# AllInOne.net
KiCad netlist of a schematic drawn in EAGLE
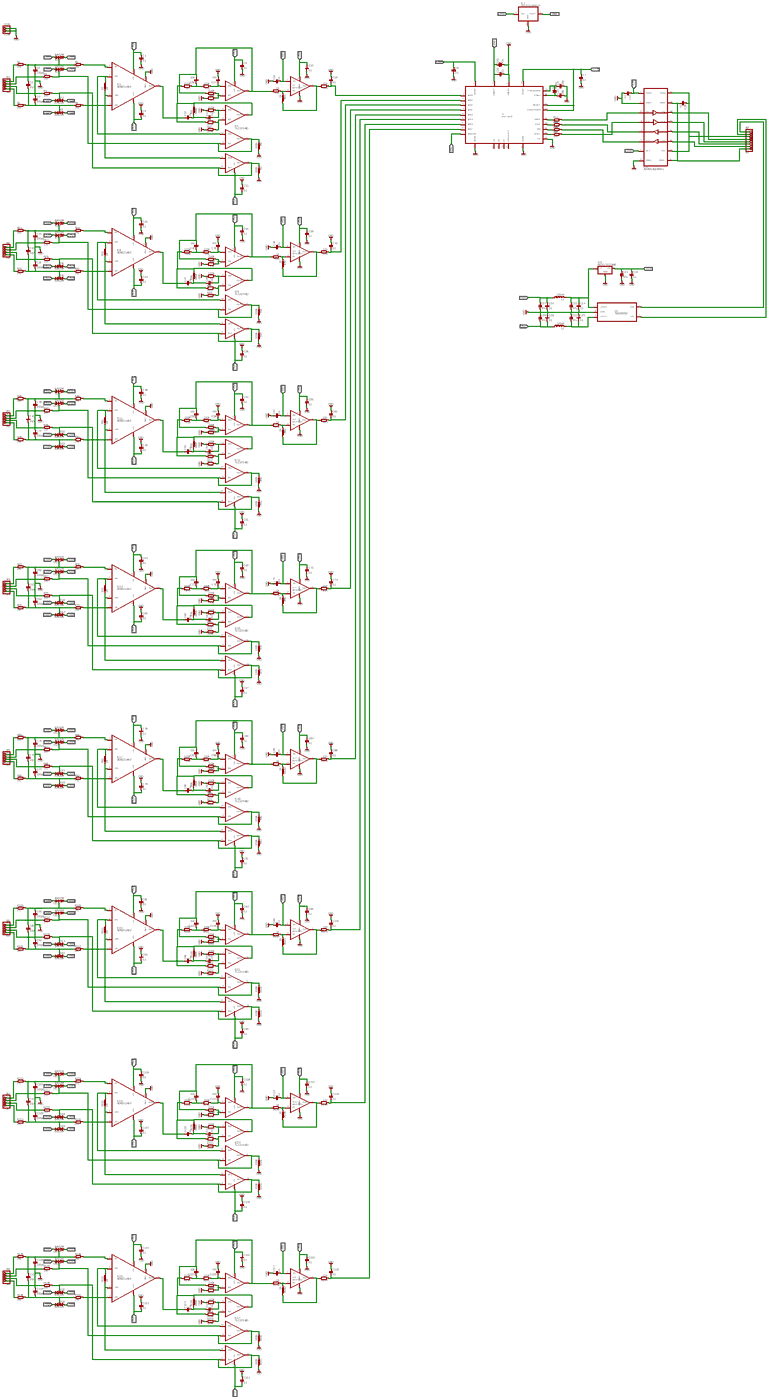
[diagram p0: schematic, sheet 1, overview]
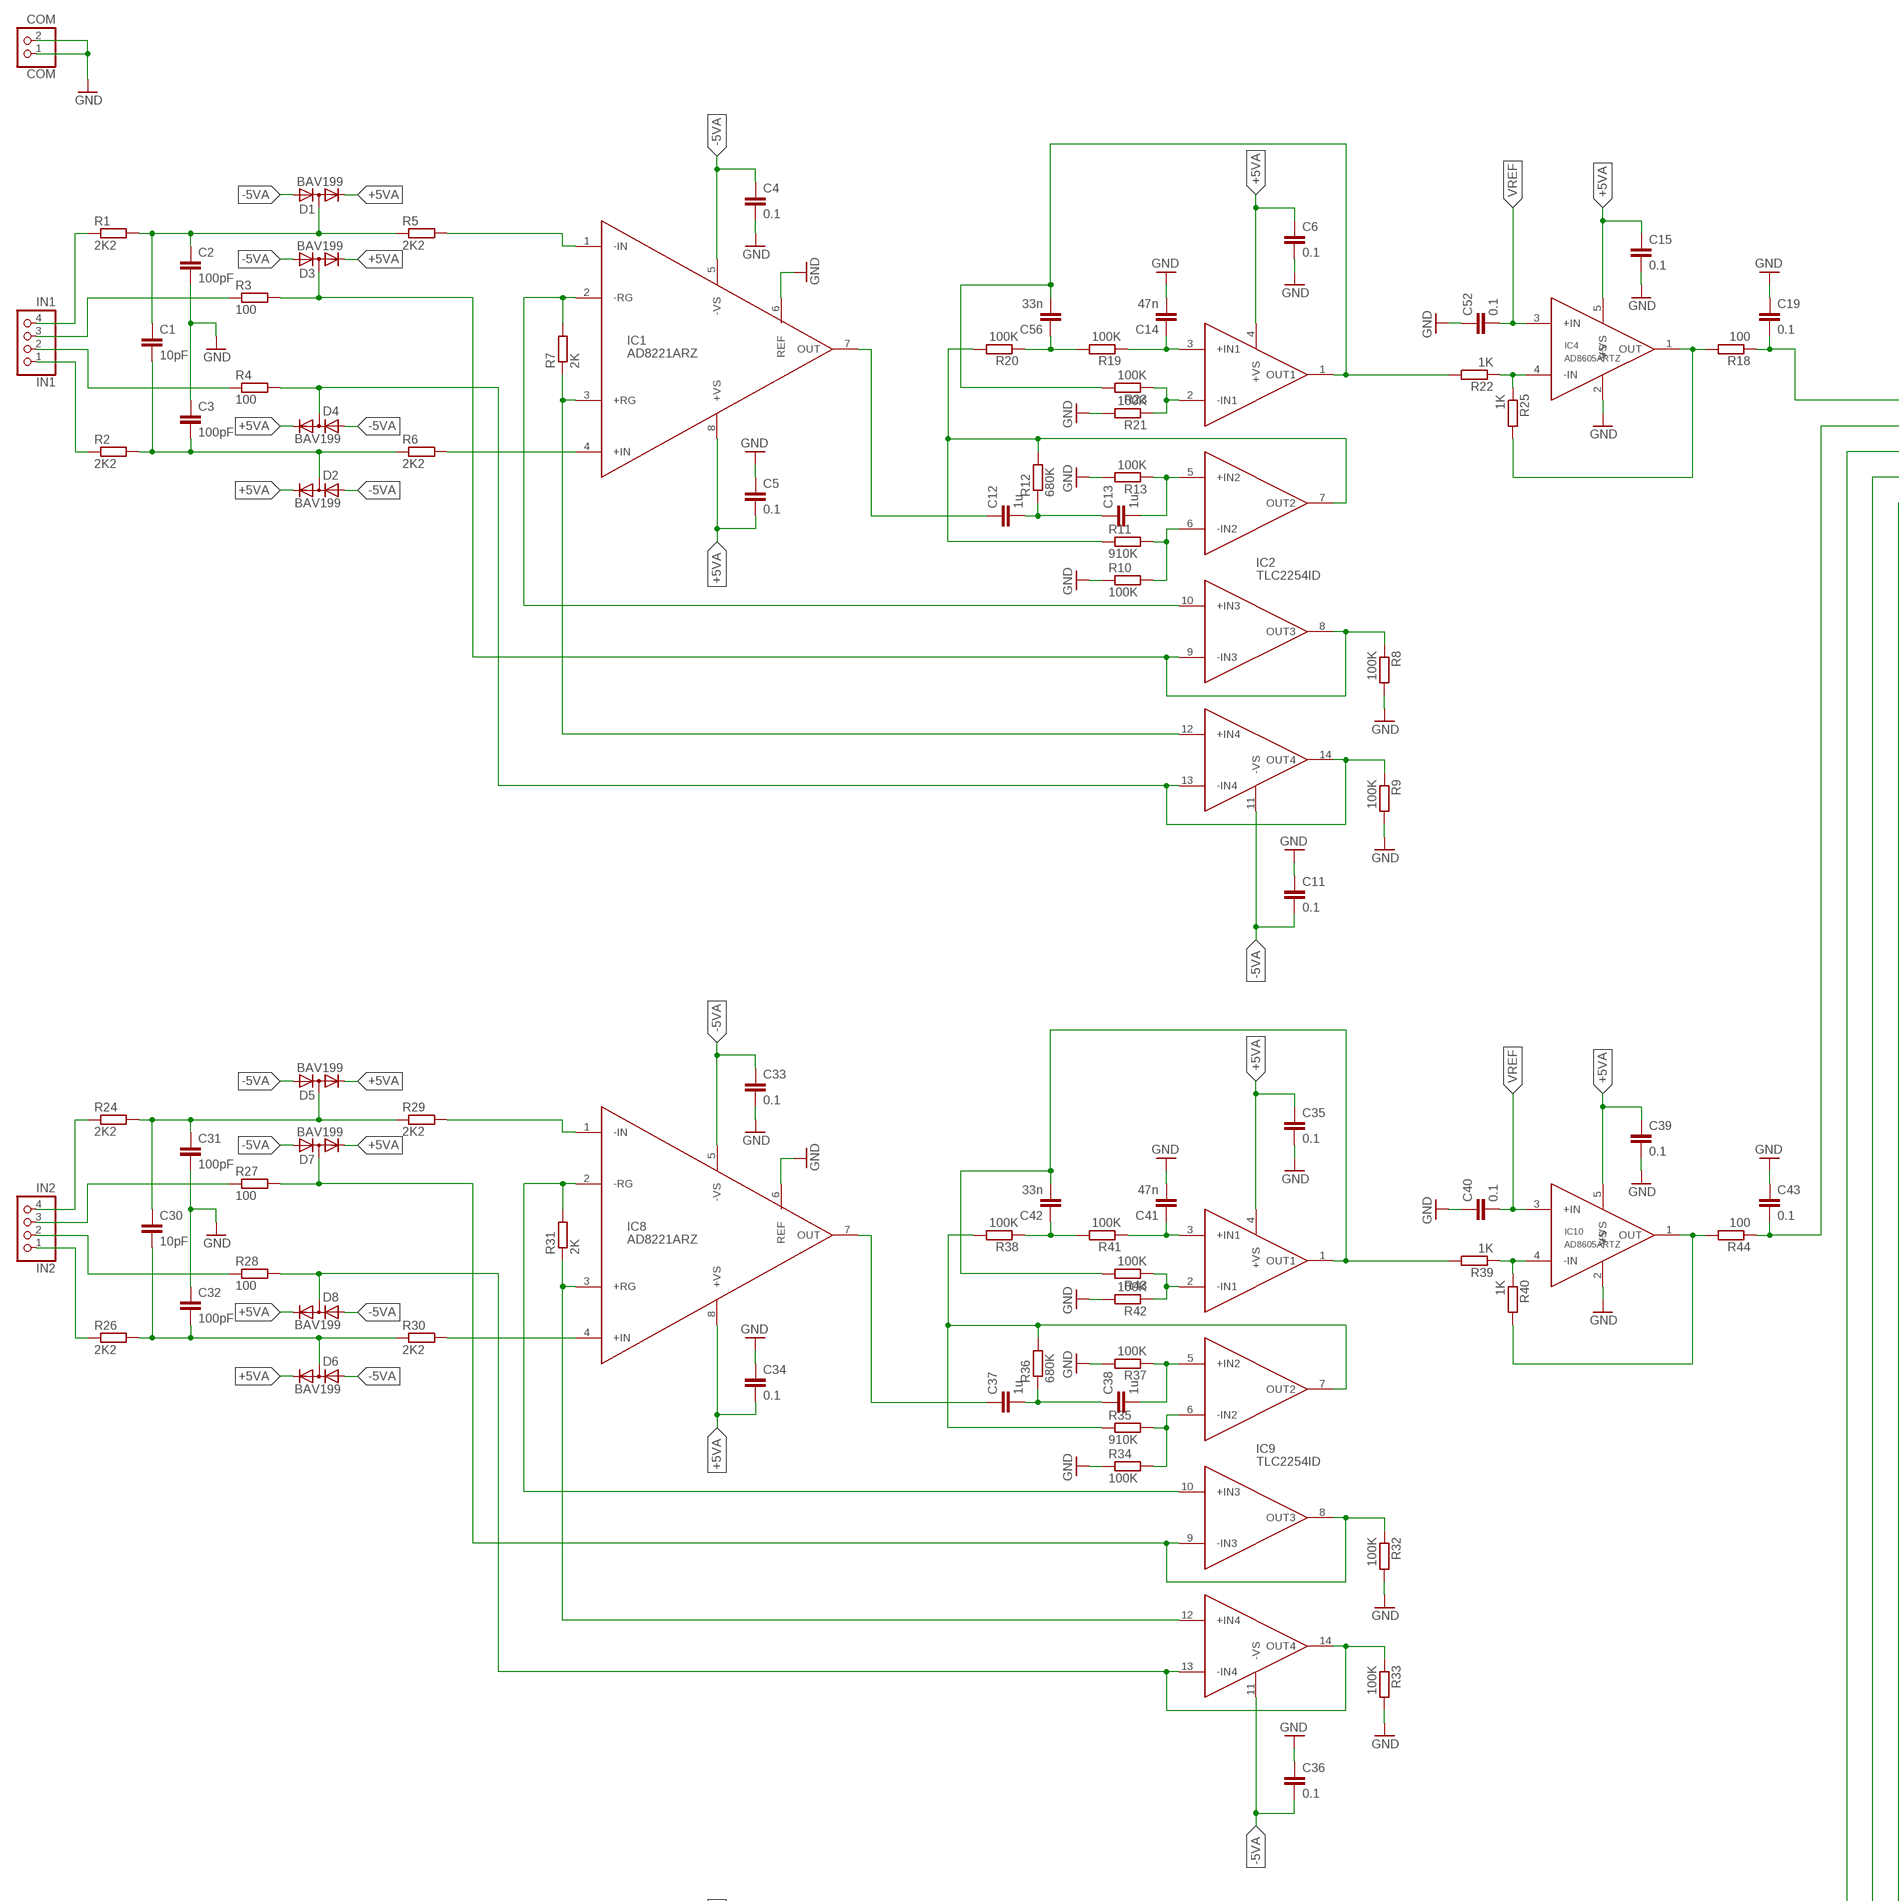
[diagram p1: schematic, sheet 1, part 1 of 5]
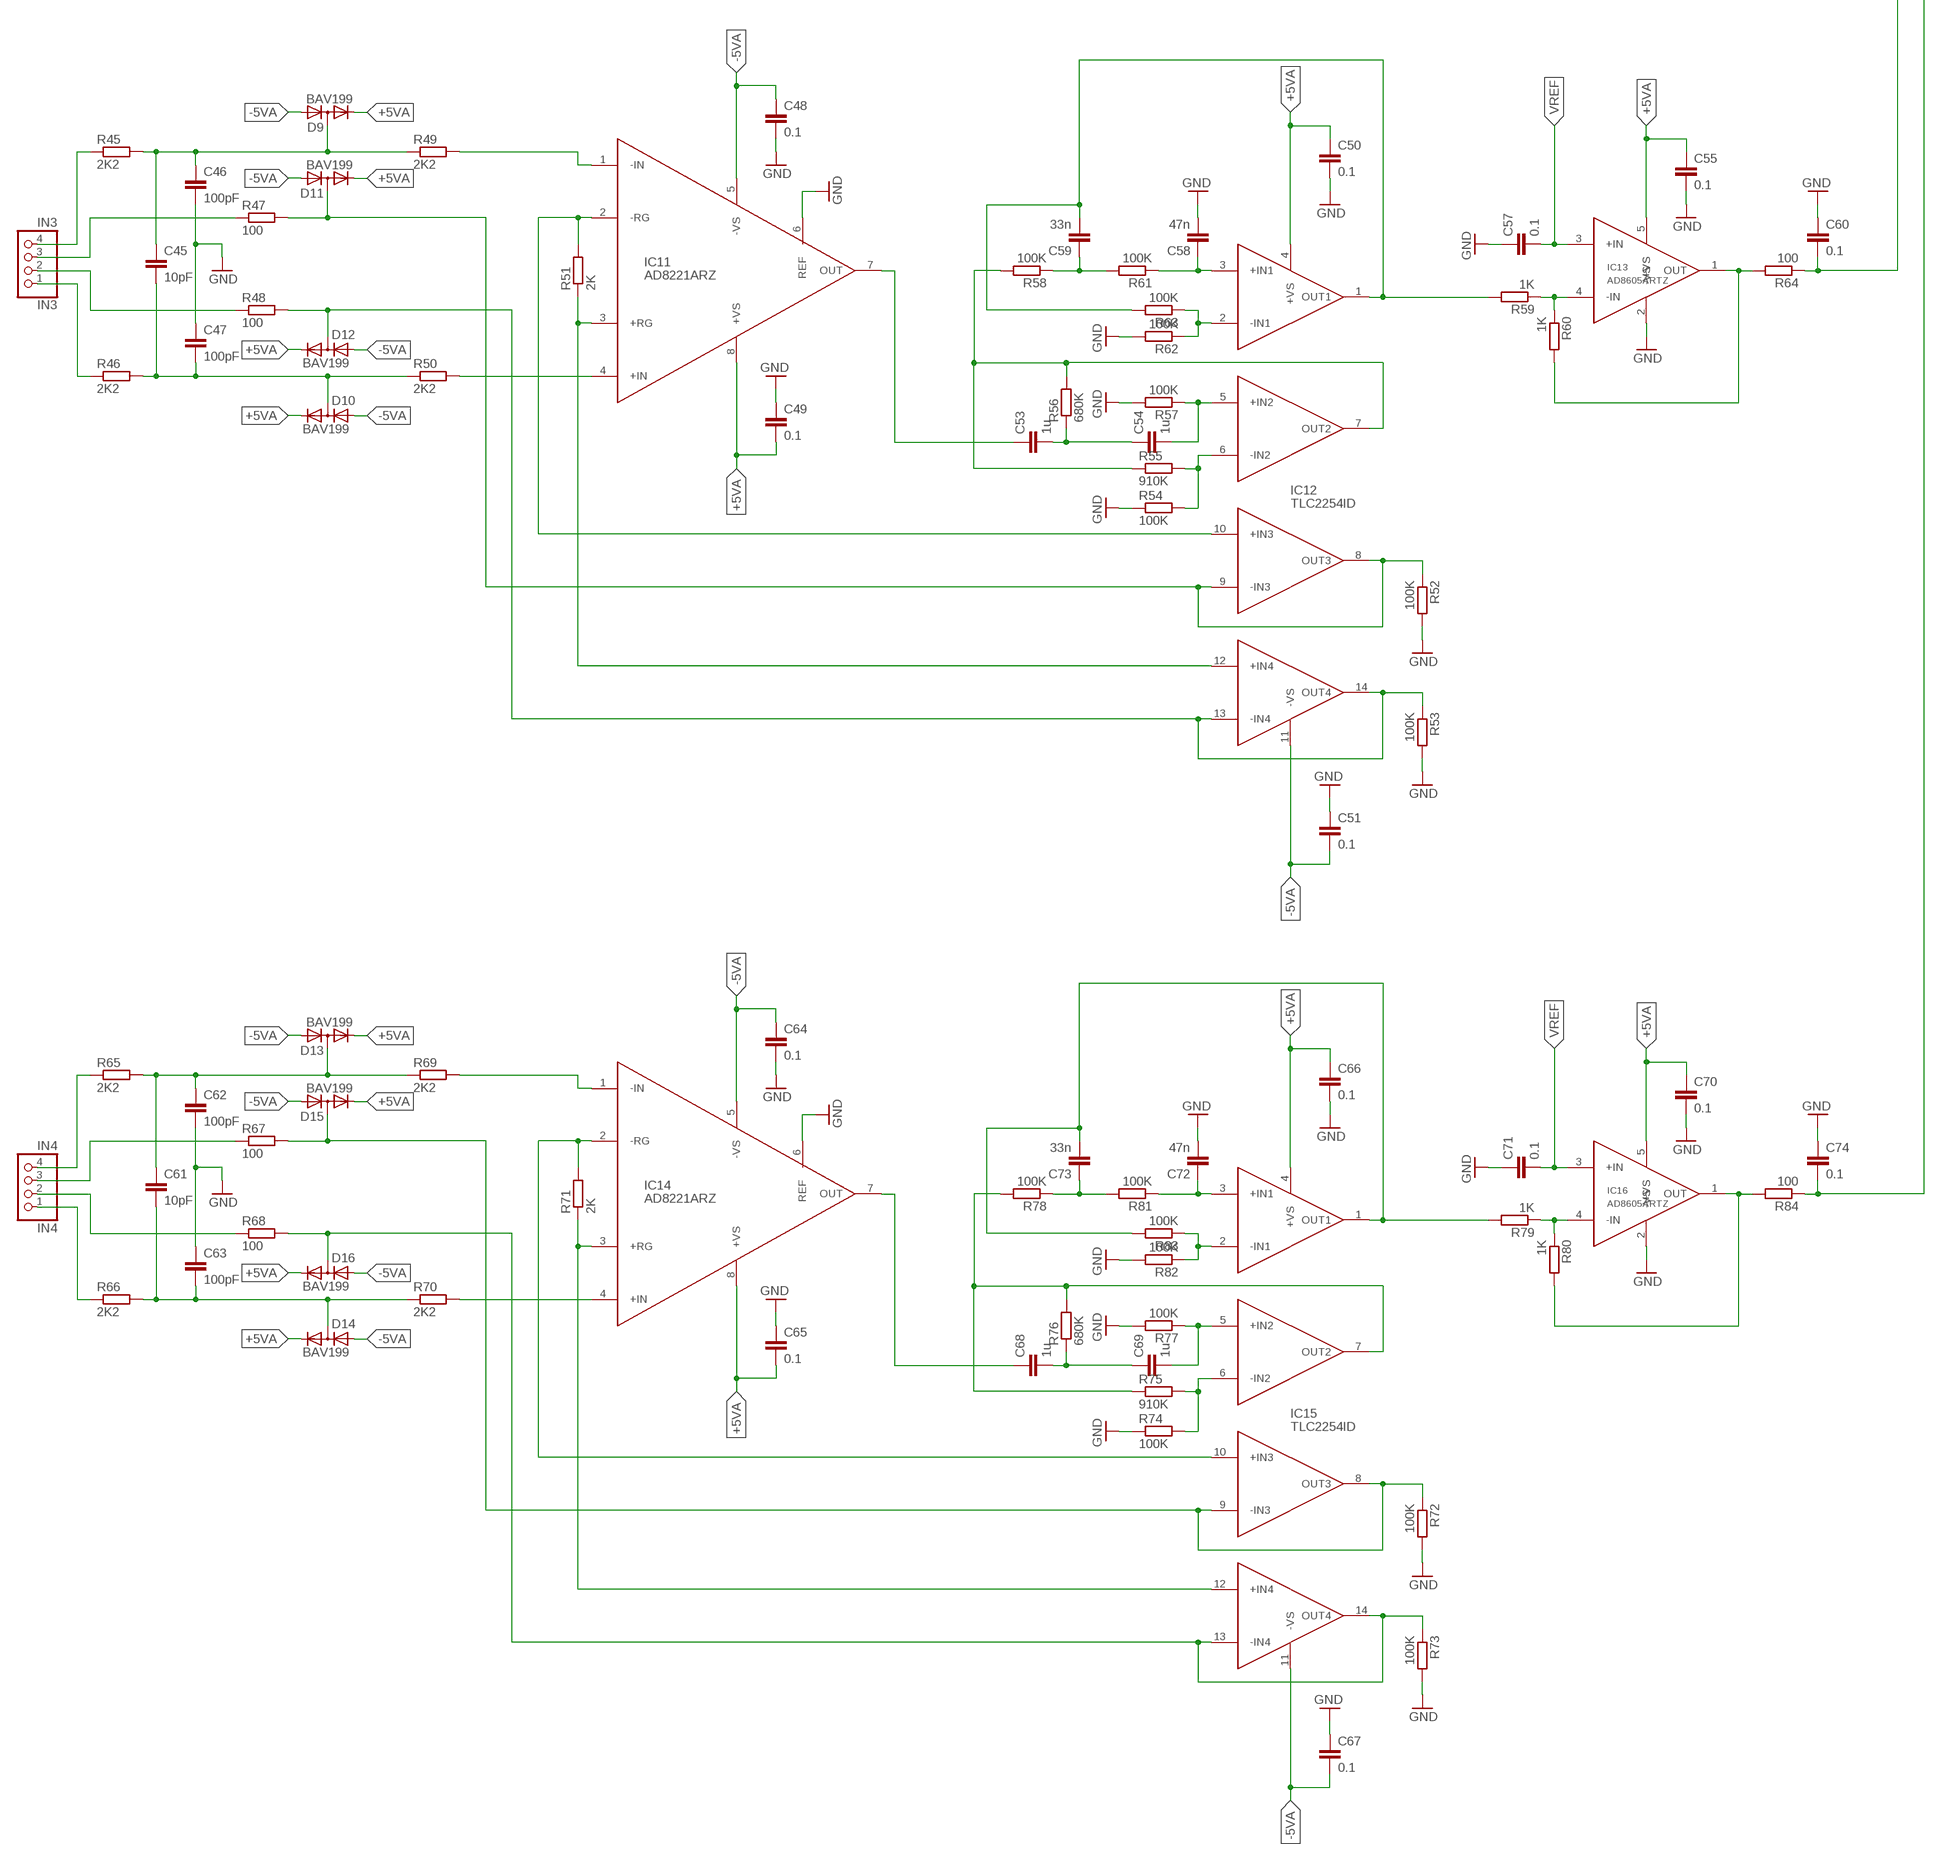
[diagram p2: schematic, sheet 1, part 2 of 5]
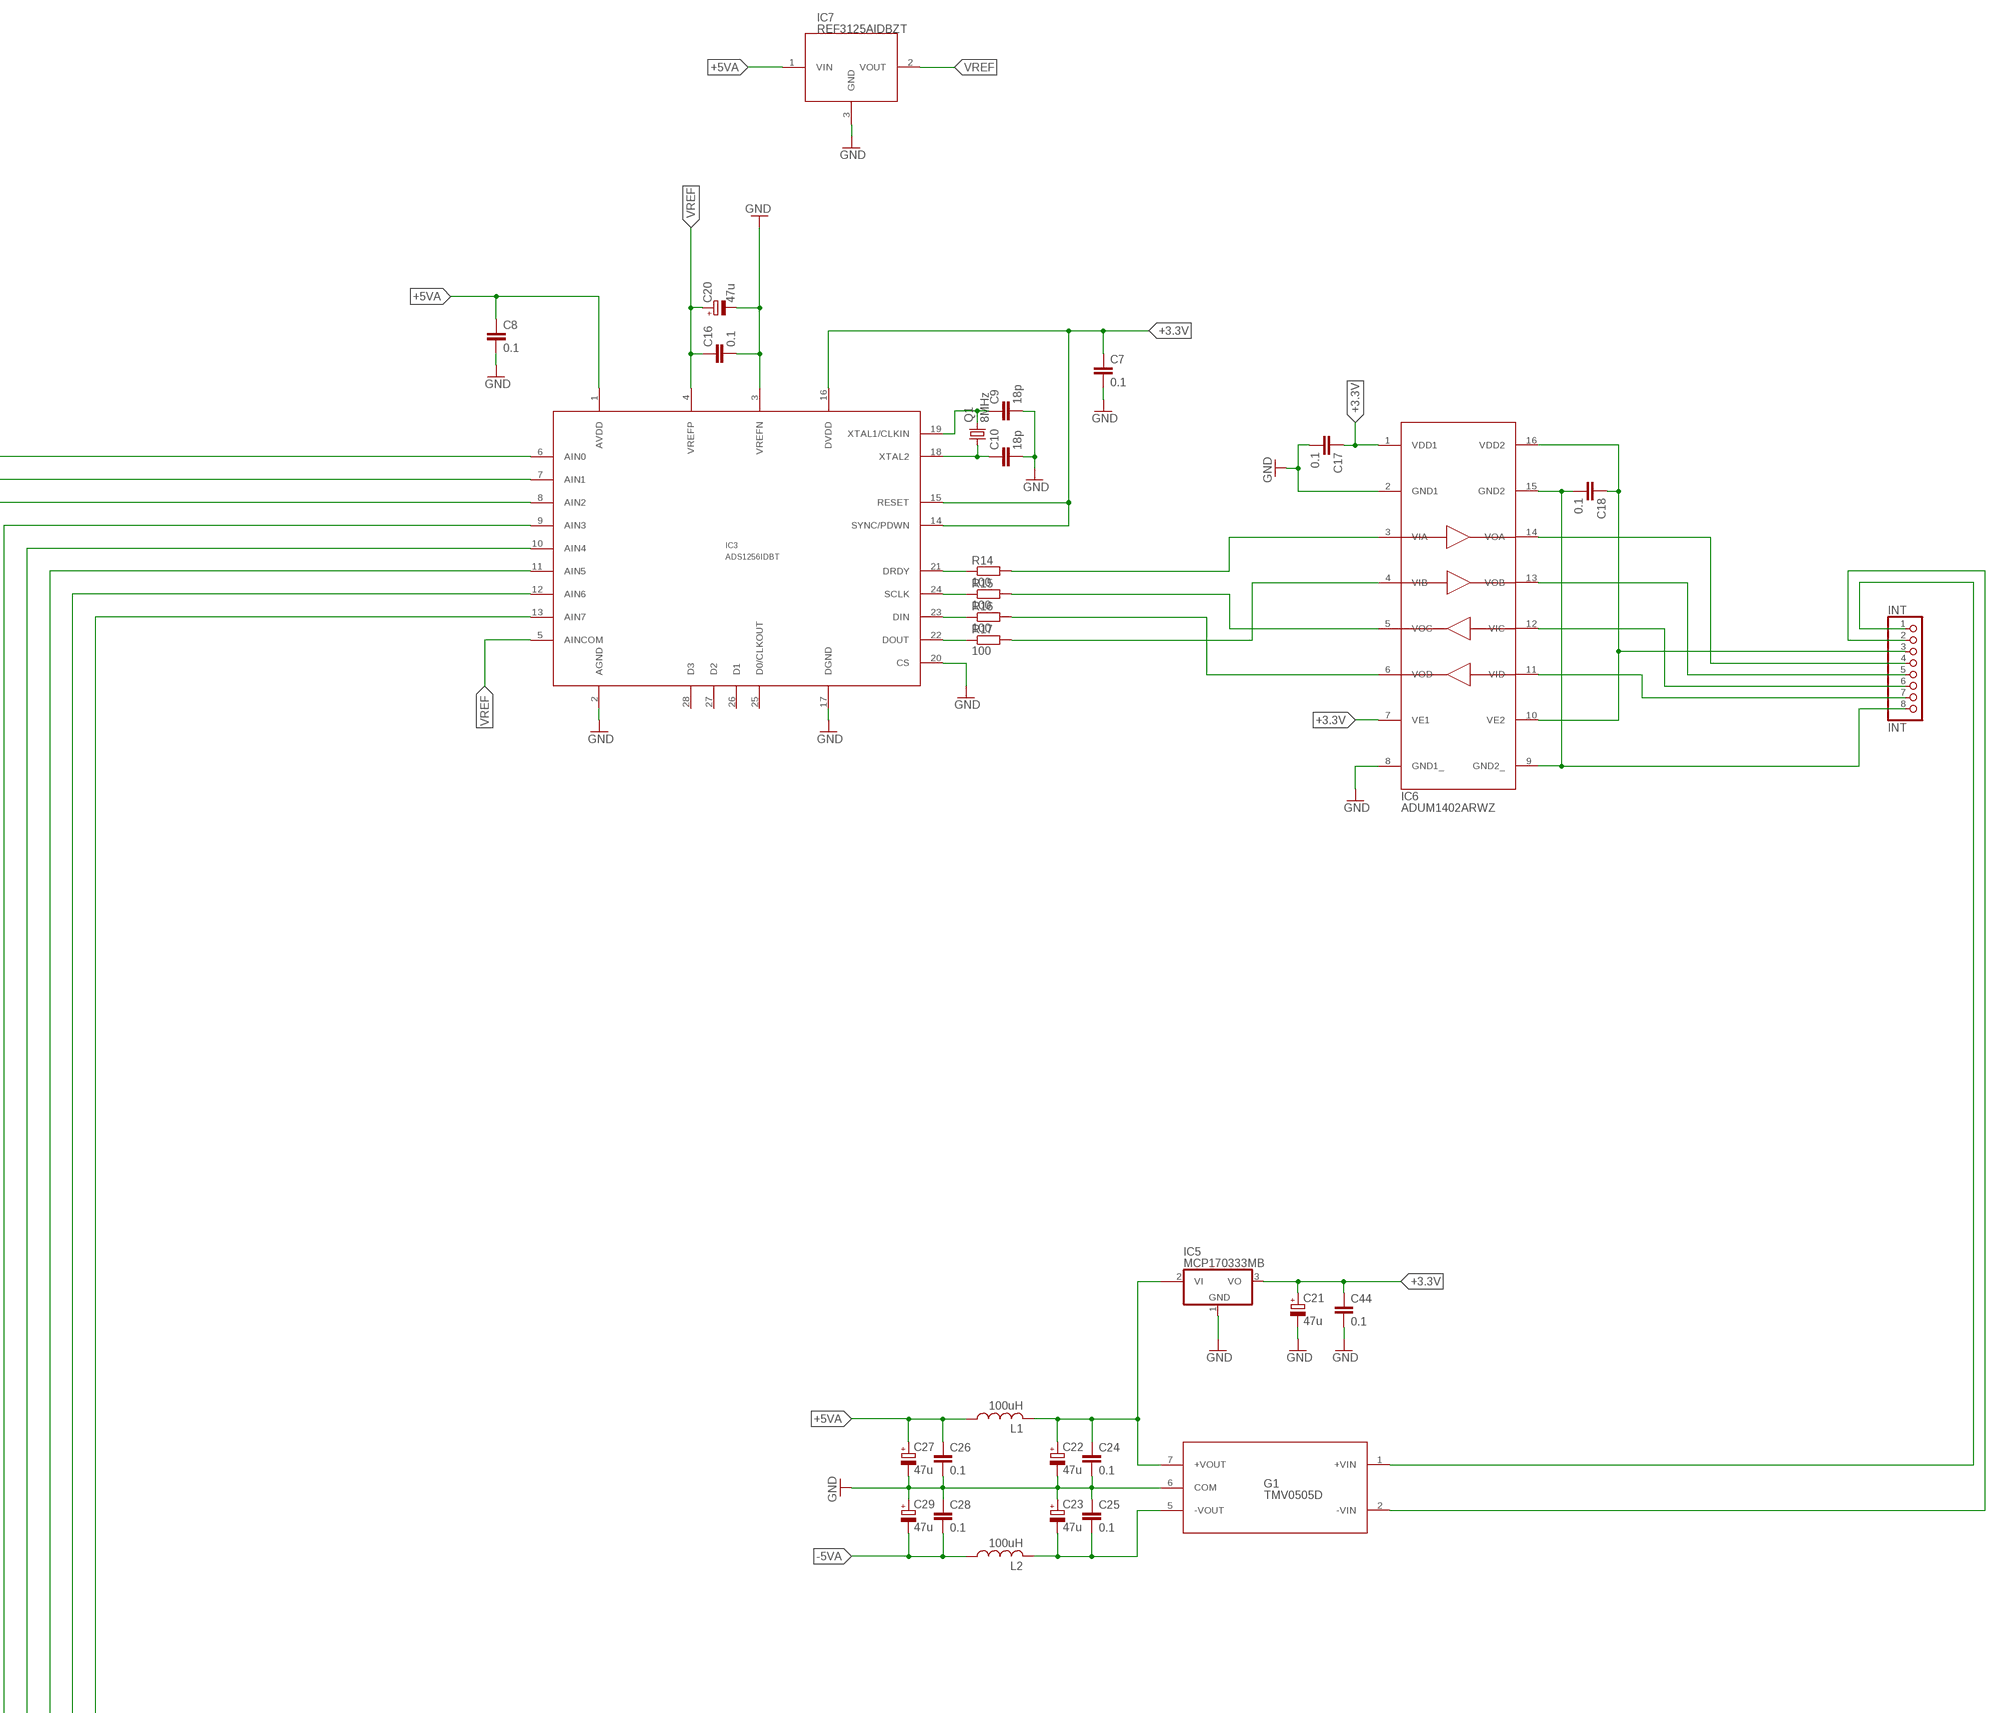
[diagram p3: schematic, sheet 1, part 3 of 5]
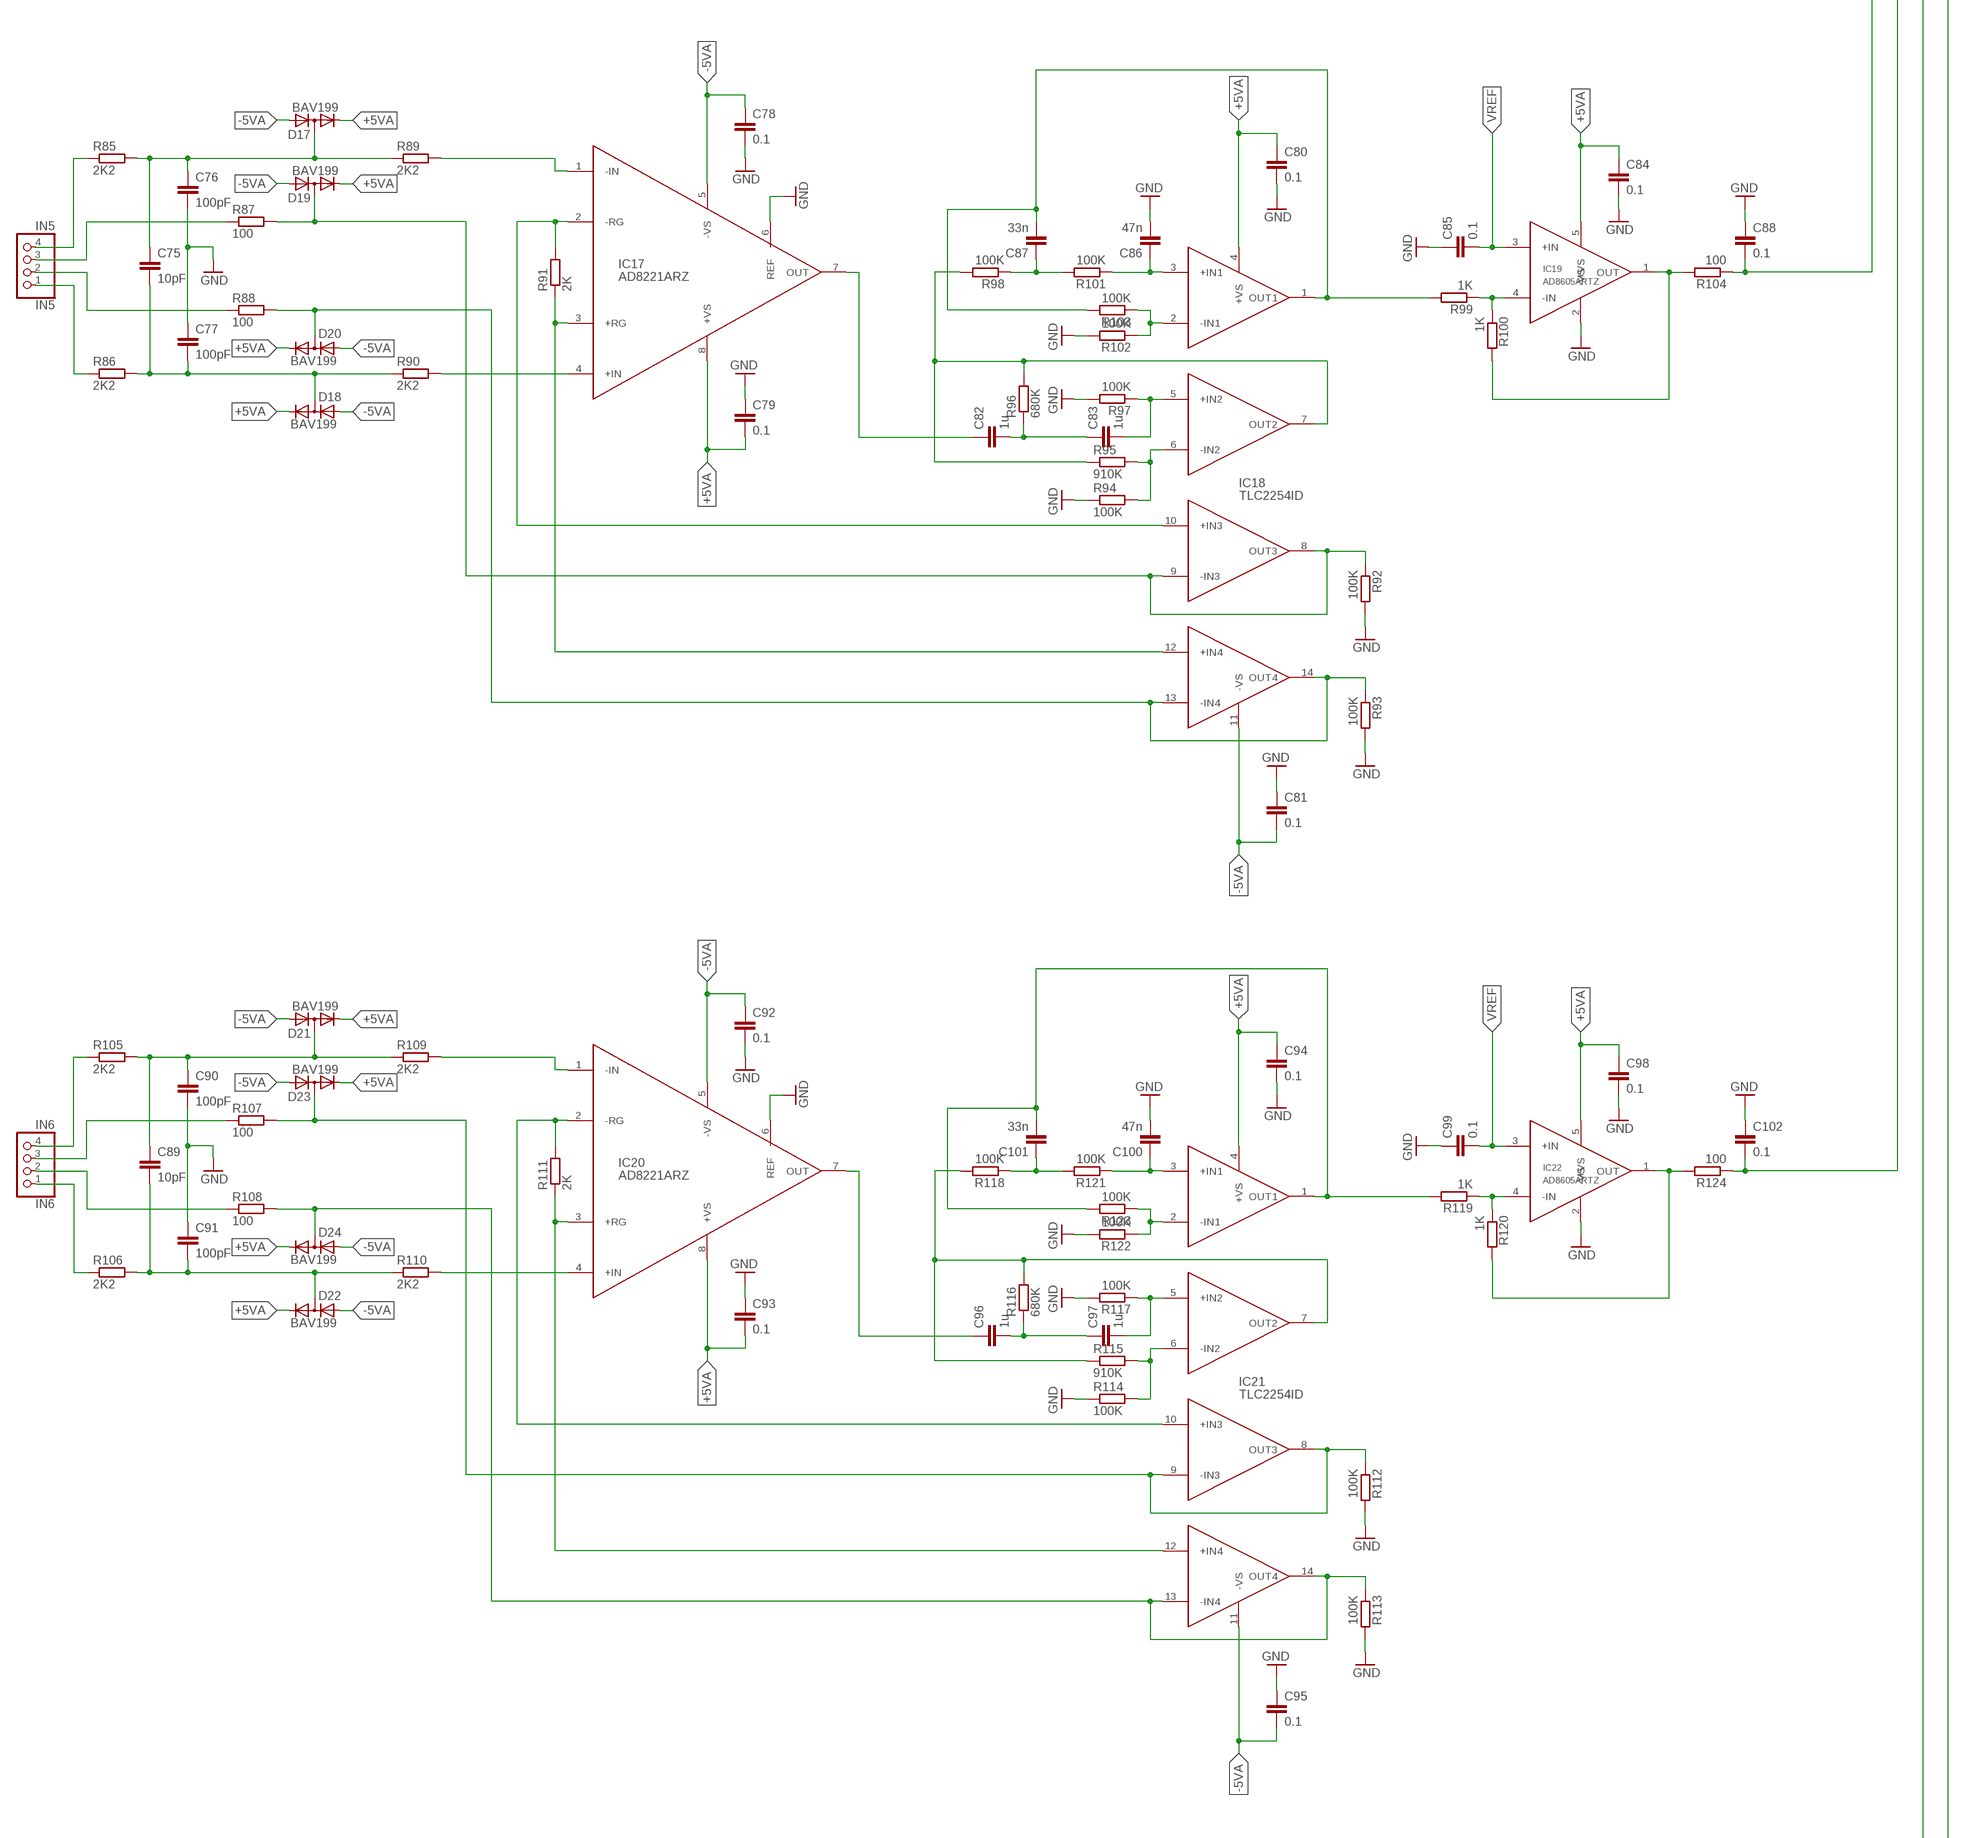
[diagram p4: schematic, sheet 1, part 4 of 5]
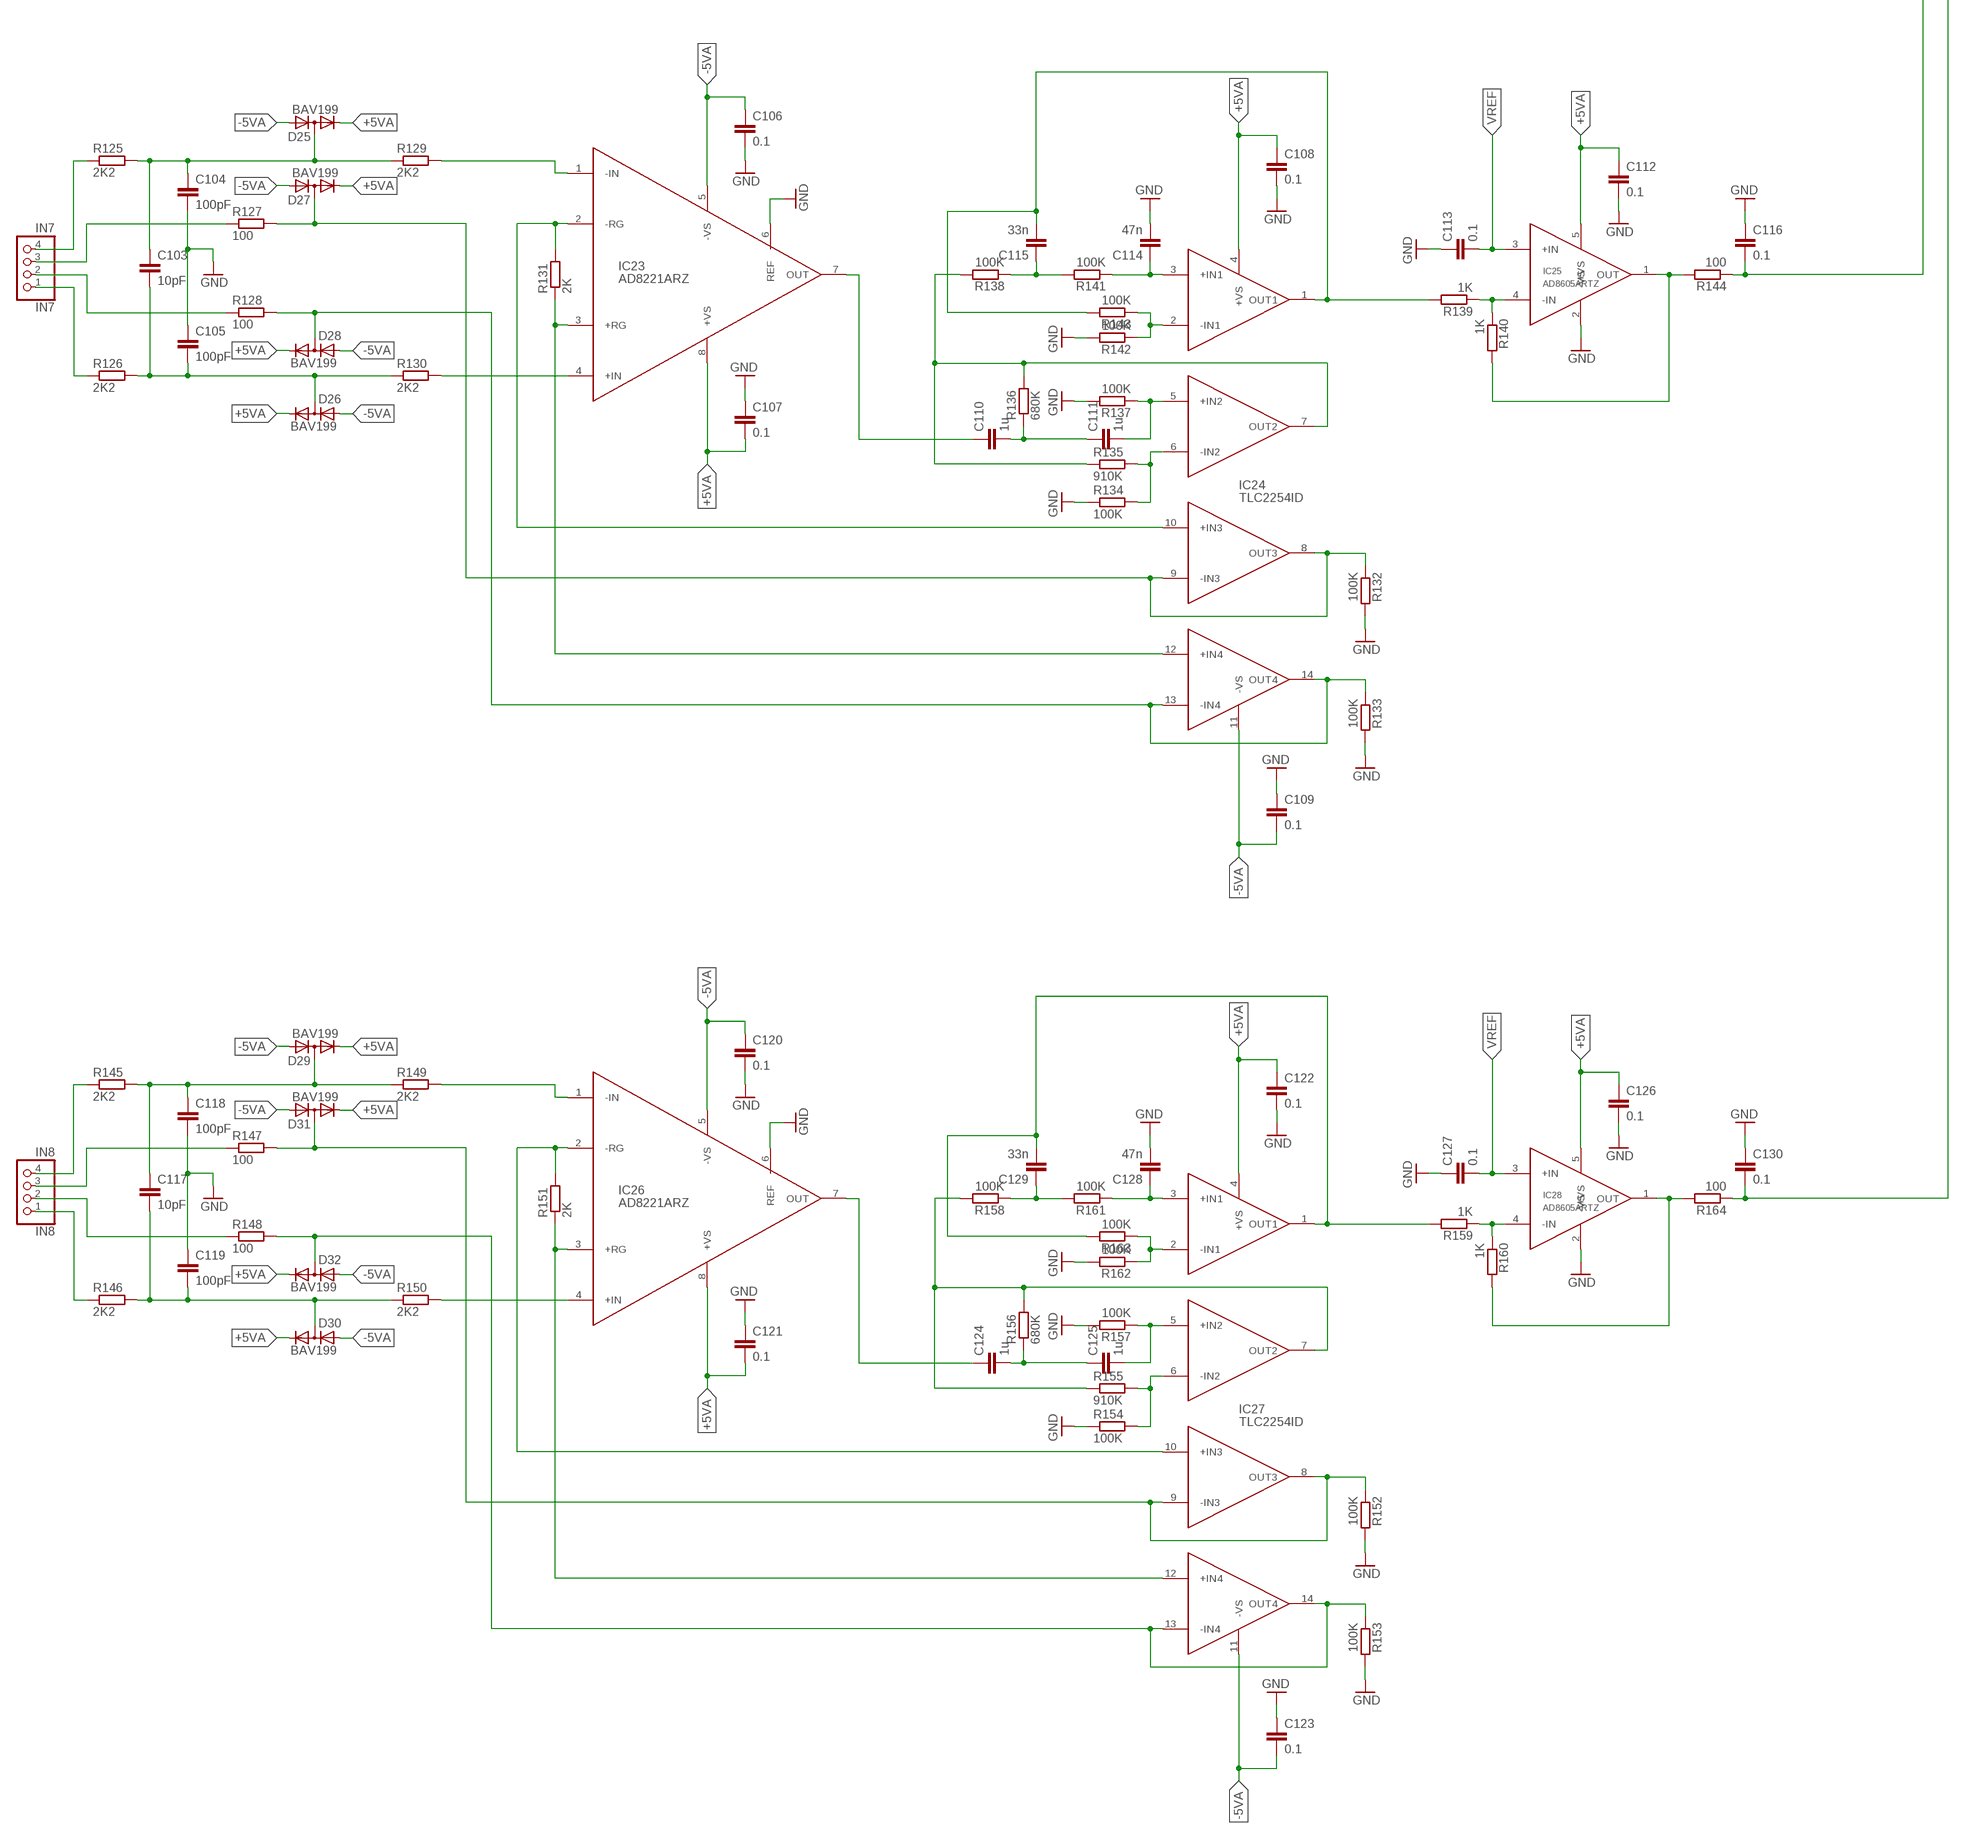
[diagram p5: schematic, sheet 1, part 5 of 5]

(export (version "E")
  (design (tool "Eeschema 10.0.6"))
  (components
    (comp (ref "C1")
      (value "10pF")
      (footprint "eagle-import:C0805")
      (libsource (lib "eagle-import") (part "C-EUC0805"))
    )
    (comp (ref "C2")
      (value "100pF")
      (footprint "eagle-import:C0805")
      (libsource (lib "eagle-import") (part "C-EUC0805"))
    )
    (comp (ref "C3")
      (value "100pF")
      (footprint "eagle-import:C0805")
      (libsource (lib "eagle-import") (part "C-EUC0805"))
    )
    (comp (ref "C4")
      (value "0.1")
      (footprint "eagle-import:C0805")
      (libsource (lib "eagle-import") (part "C-EUC0805"))
    )
    (comp (ref "C5")
      (value "0.1")
      (footprint "eagle-import:C0805")
      (libsource (lib "eagle-import") (part "C-EUC0805"))
    )
    (comp (ref "C6")
      (value "0.1")
      (footprint "eagle-import:C0805")
      (libsource (lib "eagle-import") (part "C-EUC0805"))
    )
    (comp (ref "C7")
      (value "0.1")
      (footprint "eagle-import:C0805")
      (libsource (lib "eagle-import") (part "C-EUC0805"))
    )
    (comp (ref "C8")
      (value "0.1")
      (footprint "eagle-import:C0805")
      (libsource (lib "eagle-import") (part "C-EUC0805"))
    )
    (comp (ref "C9")
      (value "18p")
      (footprint "eagle-import:C0805")
      (libsource (lib "eagle-import") (part "C-EUC0805"))
    )
    (comp (ref "C10")
      (value "18p")
      (footprint "eagle-import:C0805")
      (libsource (lib "eagle-import") (part "C-EUC0805"))
    )
    (comp (ref "C11")
      (value "0.1")
      (footprint "eagle-import:C0805")
      (libsource (lib "eagle-import") (part "C-EUC0805"))
    )
    (comp (ref "C12")
      (value "1u")
      (footprint "eagle-import:C0805")
      (libsource (lib "eagle-import") (part "C-EUC0805"))
    )
    (comp (ref "C13")
      (value "1u")
      (footprint "eagle-import:C0805")
      (libsource (lib "eagle-import") (part "C-EUC0805"))
    )
    (comp (ref "C14")
      (value "47n")
      (footprint "eagle-import:C0805")
      (libsource (lib "eagle-import") (part "C-EUC0805"))
    )
    (comp (ref "C15")
      (value "0.1")
      (footprint "eagle-import:C0805")
      (libsource (lib "eagle-import") (part "C-EUC0805"))
    )
    (comp (ref "C16")
      (value "0.1")
      (footprint "eagle-import:C0805")
      (libsource (lib "eagle-import") (part "C-EUC0805"))
    )
    (comp (ref "C17")
      (value "0.1")
      (footprint "eagle-import:C0805")
      (libsource (lib "eagle-import") (part "C-EUC0805"))
    )
    (comp (ref "C18")
      (value "0.1")
      (footprint "eagle-import:C0805")
      (libsource (lib "eagle-import") (part "C-EUC0805"))
    )
    (comp (ref "C19")
      (value "0.1")
      (footprint "eagle-import:C0805")
      (libsource (lib "eagle-import") (part "C-EUC0805"))
    )
    (comp (ref "C20")
      (value "47u")
      (footprint "eagle-import:E2-4")
      (libsource (lib "eagle-import") (part "CPOL-EUE2-4"))
    )
    (comp (ref "C21")
      (value "47u")
      (footprint "eagle-import:E2-4")
      (libsource (lib "eagle-import") (part "CPOL-EUE2-4"))
    )
    (comp (ref "C22")
      (value "47u")
      (footprint "eagle-import:E2-4")
      (libsource (lib "eagle-import") (part "CPOL-EUE2-4"))
    )
    (comp (ref "C23")
      (value "47u")
      (footprint "eagle-import:E2-4")
      (libsource (lib "eagle-import") (part "CPOL-EUE2-4"))
    )
    (comp (ref "C24")
      (value "0.1")
      (footprint "eagle-import:C0805")
      (libsource (lib "eagle-import") (part "C-EUC0805"))
    )
    (comp (ref "C25")
      (value "0.1")
      (footprint "eagle-import:C0805")
      (libsource (lib "eagle-import") (part "C-EUC0805"))
    )
    (comp (ref "C26")
      (value "0.1")
      (footprint "eagle-import:C0805")
      (libsource (lib "eagle-import") (part "C-EUC0805"))
    )
    (comp (ref "C27")
      (value "47u")
      (footprint "eagle-import:E2-4")
      (libsource (lib "eagle-import") (part "CPOL-EUE2-4"))
    )
    (comp (ref "C28")
      (value "0.1")
      (footprint "eagle-import:C0805")
      (libsource (lib "eagle-import") (part "C-EUC0805"))
    )
    (comp (ref "C29")
      (value "47u")
      (footprint "eagle-import:E2-4")
      (libsource (lib "eagle-import") (part "CPOL-EUE2-4"))
    )
    (comp (ref "C30")
      (value "10pF")
      (footprint "eagle-import:C0805")
      (libsource (lib "eagle-import") (part "C-EUC0805"))
    )
    (comp (ref "C31")
      (value "100pF")
      (footprint "eagle-import:C0805")
      (libsource (lib "eagle-import") (part "C-EUC0805"))
    )
    (comp (ref "C32")
      (value "100pF")
      (footprint "eagle-import:C0805")
      (libsource (lib "eagle-import") (part "C-EUC0805"))
    )
    (comp (ref "C33")
      (value "0.1")
      (footprint "eagle-import:C0805")
      (libsource (lib "eagle-import") (part "C-EUC0805"))
    )
    (comp (ref "C34")
      (value "0.1")
      (footprint "eagle-import:C0805")
      (libsource (lib "eagle-import") (part "C-EUC0805"))
    )
    (comp (ref "C35")
      (value "0.1")
      (footprint "eagle-import:C0805")
      (libsource (lib "eagle-import") (part "C-EUC0805"))
    )
    (comp (ref "C36")
      (value "0.1")
      (footprint "eagle-import:C0805")
      (libsource (lib "eagle-import") (part "C-EUC0805"))
    )
    (comp (ref "C37")
      (value "1u")
      (footprint "eagle-import:C0805")
      (libsource (lib "eagle-import") (part "C-EUC0805"))
    )
    (comp (ref "C38")
      (value "1u")
      (footprint "eagle-import:C0805")
      (libsource (lib "eagle-import") (part "C-EUC0805"))
    )
    (comp (ref "C39")
      (value "0.1")
      (footprint "eagle-import:C0805")
      (libsource (lib "eagle-import") (part "C-EUC0805"))
    )
    (comp (ref "C40")
      (value "0.1")
      (footprint "eagle-import:C0805")
      (libsource (lib "eagle-import") (part "C-EUC0805"))
    )
    (comp (ref "C41")
      (value "47n")
      (footprint "eagle-import:C0805")
      (libsource (lib "eagle-import") (part "C-EUC0805"))
    )
    (comp (ref "C42")
      (value "33n")
      (footprint "eagle-import:C0805")
      (libsource (lib "eagle-import") (part "C-EUC0805"))
    )
    (comp (ref "C43")
      (value "0.1")
      (footprint "eagle-import:C0805")
      (libsource (lib "eagle-import") (part "C-EUC0805"))
    )
    (comp (ref "C44")
      (value "0.1")
      (footprint "eagle-import:C0805")
      (libsource (lib "eagle-import") (part "C-EUC0805"))
    )
    (comp (ref "C45")
      (value "10pF")
      (footprint "eagle-import:C0805")
      (libsource (lib "eagle-import") (part "C-EUC0805"))
    )
    (comp (ref "C46")
      (value "100pF")
      (footprint "eagle-import:C0805")
      (libsource (lib "eagle-import") (part "C-EUC0805"))
    )
    (comp (ref "C47")
      (value "100pF")
      (footprint "eagle-import:C0805")
      (libsource (lib "eagle-import") (part "C-EUC0805"))
    )
    (comp (ref "C48")
      (value "0.1")
      (footprint "eagle-import:C0805")
      (libsource (lib "eagle-import") (part "C-EUC0805"))
    )
    (comp (ref "C49")
      (value "0.1")
      (footprint "eagle-import:C0805")
      (libsource (lib "eagle-import") (part "C-EUC0805"))
    )
    (comp (ref "C50")
      (value "0.1")
      (footprint "eagle-import:C0805")
      (libsource (lib "eagle-import") (part "C-EUC0805"))
    )
    (comp (ref "C51")
      (value "0.1")
      (footprint "eagle-import:C0805")
      (libsource (lib "eagle-import") (part "C-EUC0805"))
    )
    (comp (ref "C52")
      (value "0.1")
      (footprint "eagle-import:C0805")
      (libsource (lib "eagle-import") (part "C-EUC0805"))
    )
    (comp (ref "C53")
      (value "1u")
      (footprint "eagle-import:C0805")
      (libsource (lib "eagle-import") (part "C-EUC0805"))
    )
    (comp (ref "C54")
      (value "1u")
      (footprint "eagle-import:C0805")
      (libsource (lib "eagle-import") (part "C-EUC0805"))
    )
    (comp (ref "C55")
      (value "0.1")
      (footprint "eagle-import:C0805")
      (libsource (lib "eagle-import") (part "C-EUC0805"))
    )
    (comp (ref "C56")
      (value "33n")
      (footprint "eagle-import:C0805")
      (libsource (lib "eagle-import") (part "C-EUC0805"))
    )
    (comp (ref "C57")
      (value "0.1")
      (footprint "eagle-import:C0805")
      (libsource (lib "eagle-import") (part "C-EUC0805"))
    )
    (comp (ref "C58")
      (value "47n")
      (footprint "eagle-import:C0805")
      (libsource (lib "eagle-import") (part "C-EUC0805"))
    )
    (comp (ref "C59")
      (value "33n")
      (footprint "eagle-import:C0805")
      (libsource (lib "eagle-import") (part "C-EUC0805"))
    )
    (comp (ref "C60")
      (value "0.1")
      (footprint "eagle-import:C0805")
      (libsource (lib "eagle-import") (part "C-EUC0805"))
    )
    (comp (ref "C61")
      (value "10pF")
      (footprint "eagle-import:C0805")
      (libsource (lib "eagle-import") (part "C-EUC0805"))
    )
    (comp (ref "C62")
      (value "100pF")
      (footprint "eagle-import:C0805")
      (libsource (lib "eagle-import") (part "C-EUC0805"))
    )
    (comp (ref "C63")
      (value "100pF")
      (footprint "eagle-import:C0805")
      (libsource (lib "eagle-import") (part "C-EUC0805"))
    )
    (comp (ref "C64")
      (value "0.1")
      (footprint "eagle-import:C0805")
      (libsource (lib "eagle-import") (part "C-EUC0805"))
    )
    (comp (ref "C65")
      (value "0.1")
      (footprint "eagle-import:C0805")
      (libsource (lib "eagle-import") (part "C-EUC0805"))
    )
    (comp (ref "C66")
      (value "0.1")
      (footprint "eagle-import:C0805")
      (libsource (lib "eagle-import") (part "C-EUC0805"))
    )
    (comp (ref "C67")
      (value "0.1")
      (footprint "eagle-import:C0805")
      (libsource (lib "eagle-import") (part "C-EUC0805"))
    )
    (comp (ref "C68")
      (value "1u")
      (footprint "eagle-import:C0805")
      (libsource (lib "eagle-import") (part "C-EUC0805"))
    )
    (comp (ref "C69")
      (value "1u")
      (footprint "eagle-import:C0805")
      (libsource (lib "eagle-import") (part "C-EUC0805"))
    )
    (comp (ref "C70")
      (value "0.1")
      (footprint "eagle-import:C0805")
      (libsource (lib "eagle-import") (part "C-EUC0805"))
    )
    (comp (ref "C71")
      (value "0.1")
      (footprint "eagle-import:C0805")
      (libsource (lib "eagle-import") (part "C-EUC0805"))
    )
    (comp (ref "C72")
      (value "47n")
      (footprint "eagle-import:C0805")
      (libsource (lib "eagle-import") (part "C-EUC0805"))
    )
    (comp (ref "C73")
      (value "33n")
      (footprint "eagle-import:C0805")
      (libsource (lib "eagle-import") (part "C-EUC0805"))
    )
    (comp (ref "C74")
      (value "0.1")
      (footprint "eagle-import:C0805")
      (libsource (lib "eagle-import") (part "C-EUC0805"))
    )
    (comp (ref "C75")
      (value "10pF")
      (footprint "eagle-import:C0805")
      (libsource (lib "eagle-import") (part "C-EUC0805"))
    )
    (comp (ref "C76")
      (value "100pF")
      (footprint "eagle-import:C0805")
      (libsource (lib "eagle-import") (part "C-EUC0805"))
    )
    (comp (ref "C77")
      (value "100pF")
      (footprint "eagle-import:C0805")
      (libsource (lib "eagle-import") (part "C-EUC0805"))
    )
    (comp (ref "C78")
      (value "0.1")
      (footprint "eagle-import:C0805")
      (libsource (lib "eagle-import") (part "C-EUC0805"))
    )
    (comp (ref "C79")
      (value "0.1")
      (footprint "eagle-import:C0805")
      (libsource (lib "eagle-import") (part "C-EUC0805"))
    )
    (comp (ref "C80")
      (value "0.1")
      (footprint "eagle-import:C0805")
      (libsource (lib "eagle-import") (part "C-EUC0805"))
    )
    (comp (ref "C81")
      (value "0.1")
      (footprint "eagle-import:C0805")
      (libsource (lib "eagle-import") (part "C-EUC0805"))
    )
    (comp (ref "C82")
      (value "1u")
      (footprint "eagle-import:C0805")
      (libsource (lib "eagle-import") (part "C-EUC0805"))
    )
    (comp (ref "C83")
      (value "1u")
      (footprint "eagle-import:C0805")
      (libsource (lib "eagle-import") (part "C-EUC0805"))
    )
    (comp (ref "C84")
      (value "0.1")
      (footprint "eagle-import:C0805")
      (libsource (lib "eagle-import") (part "C-EUC0805"))
    )
    (comp (ref "C85")
      (value "0.1")
      (footprint "eagle-import:C0805")
      (libsource (lib "eagle-import") (part "C-EUC0805"))
    )
    (comp (ref "C86")
      (value "47n")
      (footprint "eagle-import:C0805")
      (libsource (lib "eagle-import") (part "C-EUC0805"))
    )
    (comp (ref "C87")
      (value "33n")
      (footprint "eagle-import:C0805")
      (libsource (lib "eagle-import") (part "C-EUC0805"))
    )
    (comp (ref "C88")
      (value "0.1")
      (footprint "eagle-import:C0805")
      (libsource (lib "eagle-import") (part "C-EUC0805"))
    )
    (comp (ref "C89")
      (value "10pF")
      (footprint "eagle-import:C0805")
      (libsource (lib "eagle-import") (part "C-EUC0805"))
    )
    (comp (ref "C90")
      (value "100pF")
      (footprint "eagle-import:C0805")
      (libsource (lib "eagle-import") (part "C-EUC0805"))
    )
    (comp (ref "C91")
      (value "100pF")
      (footprint "eagle-import:C0805")
      (libsource (lib "eagle-import") (part "C-EUC0805"))
    )
    (comp (ref "C92")
      (value "0.1")
      (footprint "eagle-import:C0805")
      (libsource (lib "eagle-import") (part "C-EUC0805"))
    )
    (comp (ref "C93")
      (value "0.1")
      (footprint "eagle-import:C0805")
      (libsource (lib "eagle-import") (part "C-EUC0805"))
    )
    (comp (ref "C94")
      (value "0.1")
      (footprint "eagle-import:C0805")
      (libsource (lib "eagle-import") (part "C-EUC0805"))
    )
    (comp (ref "C95")
      (value "0.1")
      (footprint "eagle-import:C0805")
      (libsource (lib "eagle-import") (part "C-EUC0805"))
    )
    (comp (ref "C96")
      (value "1u")
      (footprint "eagle-import:C0805")
      (libsource (lib "eagle-import") (part "C-EUC0805"))
    )
    (comp (ref "C97")
      (value "1u")
      (footprint "eagle-import:C0805")
      (libsource (lib "eagle-import") (part "C-EUC0805"))
    )
    (comp (ref "C98")
      (value "0.1")
      (footprint "eagle-import:C0805")
      (libsource (lib "eagle-import") (part "C-EUC0805"))
    )
    (comp (ref "C99")
      (value "0.1")
      (footprint "eagle-import:C0805")
      (libsource (lib "eagle-import") (part "C-EUC0805"))
    )
    (comp (ref "C100")
      (value "47n")
      (footprint "eagle-import:C0805")
      (libsource (lib "eagle-import") (part "C-EUC0805"))
    )
    (comp (ref "C101")
      (value "33n")
      (footprint "eagle-import:C0805")
      (libsource (lib "eagle-import") (part "C-EUC0805"))
    )
    (comp (ref "C102")
      (value "0.1")
      (footprint "eagle-import:C0805")
      (libsource (lib "eagle-import") (part "C-EUC0805"))
    )
    (comp (ref "C103")
      (value "10pF")
      (footprint "eagle-import:C0805")
      (libsource (lib "eagle-import") (part "C-EUC0805"))
    )
    (comp (ref "C104")
      (value "100pF")
      (footprint "eagle-import:C0805")
      (libsource (lib "eagle-import") (part "C-EUC0805"))
    )
    (comp (ref "C105")
      (value "100pF")
      (footprint "eagle-import:C0805")
      (libsource (lib "eagle-import") (part "C-EUC0805"))
    )
    (comp (ref "C106")
      (value "0.1")
      (footprint "eagle-import:C0805")
      (libsource (lib "eagle-import") (part "C-EUC0805"))
    )
    (comp (ref "C107")
      (value "0.1")
      (footprint "eagle-import:C0805")
      (libsource (lib "eagle-import") (part "C-EUC0805"))
    )
    (comp (ref "C108")
      (value "0.1")
      (footprint "eagle-import:C0805")
      (libsource (lib "eagle-import") (part "C-EUC0805"))
    )
    (comp (ref "C109")
      (value "0.1")
      (footprint "eagle-import:C0805")
      (libsource (lib "eagle-import") (part "C-EUC0805"))
    )
    (comp (ref "C110")
      (value "1u")
      (footprint "eagle-import:C0805")
      (libsource (lib "eagle-import") (part "C-EUC0805"))
    )
    (comp (ref "C111")
      (value "1u")
      (footprint "eagle-import:C0805")
      (libsource (lib "eagle-import") (part "C-EUC0805"))
    )
    (comp (ref "C112")
      (value "0.1")
      (footprint "eagle-import:C0805")
      (libsource (lib "eagle-import") (part "C-EUC0805"))
    )
    (comp (ref "C113")
      (value "0.1")
      (footprint "eagle-import:C0805")
      (libsource (lib "eagle-import") (part "C-EUC0805"))
    )
    (comp (ref "C114")
      (value "47n")
      (footprint "eagle-import:C0805")
      (libsource (lib "eagle-import") (part "C-EUC0805"))
    )
    (comp (ref "C115")
      (value "33n")
      (footprint "eagle-import:C0805")
      (libsource (lib "eagle-import") (part "C-EUC0805"))
    )
    (comp (ref "C116")
      (value "0.1")
      (footprint "eagle-import:C0805")
      (libsource (lib "eagle-import") (part "C-EUC0805"))
    )
    (comp (ref "C117")
      (value "10pF")
      (footprint "eagle-import:C0805")
      (libsource (lib "eagle-import") (part "C-EUC0805"))
    )
    (comp (ref "C118")
      (value "100pF")
      (footprint "eagle-import:C0805")
      (libsource (lib "eagle-import") (part "C-EUC0805"))
    )
    (comp (ref "C119")
      (value "100pF")
      (footprint "eagle-import:C0805")
      (libsource (lib "eagle-import") (part "C-EUC0805"))
    )
    (comp (ref "C120")
      (value "0.1")
      (footprint "eagle-import:C0805")
      (libsource (lib "eagle-import") (part "C-EUC0805"))
    )
    (comp (ref "C121")
      (value "0.1")
      (footprint "eagle-import:C0805")
      (libsource (lib "eagle-import") (part "C-EUC0805"))
    )
    (comp (ref "C122")
      (value "0.1")
      (footprint "eagle-import:C0805")
      (libsource (lib "eagle-import") (part "C-EUC0805"))
    )
    (comp (ref "C123")
      (value "0.1")
      (footprint "eagle-import:C0805")
      (libsource (lib "eagle-import") (part "C-EUC0805"))
    )
    (comp (ref "C124")
      (value "1u")
      (footprint "eagle-import:C0805")
      (libsource (lib "eagle-import") (part "C-EUC0805"))
    )
    (comp (ref "C125")
      (value "1u")
      (footprint "eagle-import:C0805")
      (libsource (lib "eagle-import") (part "C-EUC0805"))
    )
    (comp (ref "C126")
      (value "0.1")
      (footprint "eagle-import:C0805")
      (libsource (lib "eagle-import") (part "C-EUC0805"))
    )
    (comp (ref "C127")
      (value "0.1")
      (footprint "eagle-import:C0805")
      (libsource (lib "eagle-import") (part "C-EUC0805"))
    )
    (comp (ref "C128")
      (value "47n")
      (footprint "eagle-import:C0805")
      (libsource (lib "eagle-import") (part "C-EUC0805"))
    )
    (comp (ref "C129")
      (value "33n")
      (footprint "eagle-import:C0805")
      (libsource (lib "eagle-import") (part "C-EUC0805"))
    )
    (comp (ref "C130")
      (value "0.1")
      (footprint "eagle-import:C0805")
      (libsource (lib "eagle-import") (part "C-EUC0805"))
    )
    (comp (ref "COM")
      (value "COM")
      (footprint "eagle-import:1X02")
      (libsource (lib "eagle-import") (part "PINHD-1X2"))
    )
    (comp (ref "D1")
      (value "BAV199")
      (footprint "eagle-import:SOT23")
      (libsource (lib "eagle-import") (part "BAV199"))
    )
    (comp (ref "D2")
      (value "BAV199")
      (footprint "eagle-import:SOT23")
      (libsource (lib "eagle-import") (part "BAV199"))
    )
    (comp (ref "D3")
      (value "BAV199")
      (footprint "eagle-import:SOT23")
      (libsource (lib "eagle-import") (part "BAV199"))
    )
    (comp (ref "D4")
      (value "BAV199")
      (footprint "eagle-import:SOT23")
      (libsource (lib "eagle-import") (part "BAV199"))
    )
    (comp (ref "D5")
      (value "BAV199")
      (footprint "eagle-import:SOT23")
      (libsource (lib "eagle-import") (part "BAV199"))
    )
    (comp (ref "D6")
      (value "BAV199")
      (footprint "eagle-import:SOT23")
      (libsource (lib "eagle-import") (part "BAV199"))
    )
    (comp (ref "D7")
      (value "BAV199")
      (footprint "eagle-import:SOT23")
      (libsource (lib "eagle-import") (part "BAV199"))
    )
    (comp (ref "D8")
      (value "BAV199")
      (footprint "eagle-import:SOT23")
      (libsource (lib "eagle-import") (part "BAV199"))
    )
    (comp (ref "D9")
      (value "BAV199")
      (footprint "eagle-import:SOT23")
      (libsource (lib "eagle-import") (part "BAV199"))
    )
    (comp (ref "D10")
      (value "BAV199")
      (footprint "eagle-import:SOT23")
      (libsource (lib "eagle-import") (part "BAV199"))
    )
    (comp (ref "D11")
      (value "BAV199")
      (footprint "eagle-import:SOT23")
      (libsource (lib "eagle-import") (part "BAV199"))
    )
    (comp (ref "D12")
      (value "BAV199")
      (footprint "eagle-import:SOT23")
      (libsource (lib "eagle-import") (part "BAV199"))
    )
    (comp (ref "D13")
      (value "BAV199")
      (footprint "eagle-import:SOT23")
      (libsource (lib "eagle-import") (part "BAV199"))
    )
    (comp (ref "D14")
      (value "BAV199")
      (footprint "eagle-import:SOT23")
      (libsource (lib "eagle-import") (part "BAV199"))
    )
    (comp (ref "D15")
      (value "BAV199")
      (footprint "eagle-import:SOT23")
      (libsource (lib "eagle-import") (part "BAV199"))
    )
    (comp (ref "D16")
      (value "BAV199")
      (footprint "eagle-import:SOT23")
      (libsource (lib "eagle-import") (part "BAV199"))
    )
    (comp (ref "D17")
      (value "BAV199")
      (footprint "eagle-import:SOT23")
      (libsource (lib "eagle-import") (part "BAV199"))
    )
    (comp (ref "D18")
      (value "BAV199")
      (footprint "eagle-import:SOT23")
      (libsource (lib "eagle-import") (part "BAV199"))
    )
    (comp (ref "D19")
      (value "BAV199")
      (footprint "eagle-import:SOT23")
      (libsource (lib "eagle-import") (part "BAV199"))
    )
    (comp (ref "D20")
      (value "BAV199")
      (footprint "eagle-import:SOT23")
      (libsource (lib "eagle-import") (part "BAV199"))
    )
    (comp (ref "D21")
      (value "BAV199")
      (footprint "eagle-import:SOT23")
      (libsource (lib "eagle-import") (part "BAV199"))
    )
    (comp (ref "D22")
      (value "BAV199")
      (footprint "eagle-import:SOT23")
      (libsource (lib "eagle-import") (part "BAV199"))
    )
    (comp (ref "D23")
      (value "BAV199")
      (footprint "eagle-import:SOT23")
      (libsource (lib "eagle-import") (part "BAV199"))
    )
    (comp (ref "D24")
      (value "BAV199")
      (footprint "eagle-import:SOT23")
      (libsource (lib "eagle-import") (part "BAV199"))
    )
    (comp (ref "D25")
      (value "BAV199")
      (footprint "eagle-import:SOT23")
      (libsource (lib "eagle-import") (part "BAV199"))
    )
    (comp (ref "D26")
      (value "BAV199")
      (footprint "eagle-import:SOT23")
      (libsource (lib "eagle-import") (part "BAV199"))
    )
    (comp (ref "D27")
      (value "BAV199")
      (footprint "eagle-import:SOT23")
      (libsource (lib "eagle-import") (part "BAV199"))
    )
    (comp (ref "D28")
      (value "BAV199")
      (footprint "eagle-import:SOT23")
      (libsource (lib "eagle-import") (part "BAV199"))
    )
    (comp (ref "D29")
      (value "BAV199")
      (footprint "eagle-import:SOT23")
      (libsource (lib "eagle-import") (part "BAV199"))
    )
    (comp (ref "D30")
      (value "BAV199")
      (footprint "eagle-import:SOT23")
      (libsource (lib "eagle-import") (part "BAV199"))
    )
    (comp (ref "D31")
      (value "BAV199")
      (footprint "eagle-import:SOT23")
      (libsource (lib "eagle-import") (part "BAV199"))
    )
    (comp (ref "D32")
      (value "BAV199")
      (footprint "eagle-import:SOT23")
      (libsource (lib "eagle-import") (part "BAV199"))
    )
    (comp (ref "G1")
      (value "TMV0505D")
      (footprint "eagle-import:TMV0505D")
      (libsource (lib "eagle-import") (part "TMV0505D"))
    )
    (comp (ref "IC1")
      (value "AD8221ARZ")
      (footprint "eagle-import:SO-08")
      (libsource (lib "eagle-import") (part "AD8221ARZ"))
    )
    (comp (ref "IC2")
      (value "TLC2254ID")
      (footprint "eagle-import:TLC2254ID")
      (libsource (lib "eagle-import") (part "TLC2254ID"))
    )
    (comp (ref "IC3")
      (value "ADS1256IDBT")
      (footprint "eagle-import:ADS1256IDBT")
      (libsource (lib "eagle-import") (part "ADS1256IDBT"))
    )
    (comp (ref "IC4")
      (value "AD8605ARTZ")
      (footprint "eagle-import:AD8605ARTZ")
      (libsource (lib "eagle-import") (part "AD8605ARTZ"))
    )
    (comp (ref "IC5")
      (value "MCP170333MB")
      (footprint "eagle-import:SOT89")
      (libsource (lib "eagle-import") (part "MCP1703MB33"))
    )
    (comp (ref "IC6")
      (value "ADUM1402ARWZ")
      (footprint "eagle-import:ADUM1402ARWZ")
      (libsource (lib "eagle-import") (part "ADUM1402ARWZ"))
    )
    (comp (ref "IC7")
      (value "REF3125AIDBZT")
      (footprint "eagle-import:REF3125AIDBZT")
      (libsource (lib "eagle-import") (part "REF3125AIDBZT"))
    )
    (comp (ref "IC8")
      (value "AD8221ARZ")
      (footprint "eagle-import:SO-08")
      (libsource (lib "eagle-import") (part "AD8221ARZ"))
    )
    (comp (ref "IC9")
      (value "TLC2254ID")
      (footprint "eagle-import:TLC2254ID")
      (libsource (lib "eagle-import") (part "TLC2254ID"))
    )
    (comp (ref "IC10")
      (value "AD8605ARTZ")
      (footprint "eagle-import:AD8605ARTZ")
      (libsource (lib "eagle-import") (part "AD8605ARTZ"))
    )
    (comp (ref "IC11")
      (value "AD8221ARZ")
      (footprint "eagle-import:SO-08")
      (libsource (lib "eagle-import") (part "AD8221ARZ"))
    )
    (comp (ref "IC12")
      (value "TLC2254ID")
      (footprint "eagle-import:TLC2254ID")
      (libsource (lib "eagle-import") (part "TLC2254ID"))
    )
    (comp (ref "IC13")
      (value "AD8605ARTZ")
      (footprint "eagle-import:AD8605ARTZ")
      (libsource (lib "eagle-import") (part "AD8605ARTZ"))
    )
    (comp (ref "IC14")
      (value "AD8221ARZ")
      (footprint "eagle-import:SO-08")
      (libsource (lib "eagle-import") (part "AD8221ARZ"))
    )
    (comp (ref "IC15")
      (value "TLC2254ID")
      (footprint "eagle-import:TLC2254ID")
      (libsource (lib "eagle-import") (part "TLC2254ID"))
    )
    (comp (ref "IC16")
      (value "AD8605ARTZ")
      (footprint "eagle-import:AD8605ARTZ")
      (libsource (lib "eagle-import") (part "AD8605ARTZ"))
    )
    (comp (ref "IC17")
      (value "AD8221ARZ")
      (footprint "eagle-import:SO-08")
      (libsource (lib "eagle-import") (part "AD8221ARZ"))
    )
    (comp (ref "IC18")
      (value "TLC2254ID")
      (footprint "eagle-import:TLC2254ID")
      (libsource (lib "eagle-import") (part "TLC2254ID"))
    )
    (comp (ref "IC19")
      (value "AD8605ARTZ")
      (footprint "eagle-import:AD8605ARTZ")
      (libsource (lib "eagle-import") (part "AD8605ARTZ"))
    )
    (comp (ref "IC20")
      (value "AD8221ARZ")
      (footprint "eagle-import:SO-08")
      (libsource (lib "eagle-import") (part "AD8221ARZ"))
    )
    (comp (ref "IC21")
      (value "TLC2254ID")
      (footprint "eagle-import:TLC2254ID")
      (libsource (lib "eagle-import") (part "TLC2254ID"))
    )
    (comp (ref "IC22")
      (value "AD8605ARTZ")
      (footprint "eagle-import:AD8605ARTZ")
      (libsource (lib "eagle-import") (part "AD8605ARTZ"))
    )
    (comp (ref "IC23")
      (value "AD8221ARZ")
      (footprint "eagle-import:SO-08")
      (libsource (lib "eagle-import") (part "AD8221ARZ"))
    )
    (comp (ref "IC24")
      (value "TLC2254ID")
      (footprint "eagle-import:TLC2254ID")
      (libsource (lib "eagle-import") (part "TLC2254ID"))
    )
    (comp (ref "IC25")
      (value "AD8605ARTZ")
      (footprint "eagle-import:AD8605ARTZ")
      (libsource (lib "eagle-import") (part "AD8605ARTZ"))
    )
    (comp (ref "IC26")
      (value "AD8221ARZ")
      (footprint "eagle-import:SO-08")
      (libsource (lib "eagle-import") (part "AD8221ARZ"))
    )
    (comp (ref "IC27")
      (value "TLC2254ID")
      (footprint "eagle-import:TLC2254ID")
      (libsource (lib "eagle-import") (part "TLC2254ID"))
    )
    (comp (ref "IC28")
      (value "AD8605ARTZ")
      (footprint "eagle-import:AD8605ARTZ")
      (libsource (lib "eagle-import") (part "AD8605ARTZ"))
    )
    (comp (ref "IN1")
      (value "IN1")
      (footprint "eagle-import:1X04")
      (libsource (lib "eagle-import") (part "PINHD-1X4"))
    )
    (comp (ref "IN2")
      (value "IN2")
      (footprint "eagle-import:1X04")
      (libsource (lib "eagle-import") (part "PINHD-1X4"))
    )
    (comp (ref "IN3")
      (value "IN3")
      (footprint "eagle-import:1X04")
      (libsource (lib "eagle-import") (part "PINHD-1X4"))
    )
    (comp (ref "IN4")
      (value "IN4")
      (footprint "eagle-import:1X04")
      (libsource (lib "eagle-import") (part "PINHD-1X4"))
    )
    (comp (ref "IN5")
      (value "IN5")
      (footprint "eagle-import:1X04")
      (libsource (lib "eagle-import") (part "PINHD-1X4"))
    )
    (comp (ref "IN6")
      (value "IN6")
      (footprint "eagle-import:1X04")
      (libsource (lib "eagle-import") (part "PINHD-1X4"))
    )
    (comp (ref "IN7")
      (value "IN7")
      (footprint "eagle-import:1X04")
      (libsource (lib "eagle-import") (part "PINHD-1X4"))
    )
    (comp (ref "IN8")
      (value "IN8")
      (footprint "eagle-import:1X04")
      (libsource (lib "eagle-import") (part "PINHD-1X4"))
    )
    (comp (ref "INT")
      (value "INT")
      (footprint "eagle-import:1X08")
      (libsource (lib "eagle-import") (part "PINHD-1X8"))
    )
    (comp (ref "L1")
      (value "100uH")
      (footprint "eagle-import:L4532P")
      (libsource (lib "eagle-import") (part "L-USL4532P"))
    )
    (comp (ref "L2")
      (value "100uH")
      (footprint "eagle-import:L4532P")
      (libsource (lib "eagle-import") (part "L-USL4532P"))
    )
    (comp (ref "Q1")
      (value "8MHz")
      (footprint "eagle-import:HC49U-V")
      (libsource (lib "eagle-import") (part "CRYSTALHC49U-V"))
    )
    (comp (ref "R1")
      (value "2K2")
      (footprint "eagle-import:R0805")
      (libsource (lib "eagle-import") (part "R-EU_R0805"))
    )
    (comp (ref "R2")
      (value "2K2")
      (footprint "eagle-import:R0805")
      (libsource (lib "eagle-import") (part "R-EU_R0805"))
    )
    (comp (ref "R3")
      (value "100")
      (footprint "eagle-import:R0805")
      (libsource (lib "eagle-import") (part "R-EU_R0805"))
    )
    (comp (ref "R4")
      (value "100")
      (footprint "eagle-import:R0805")
      (libsource (lib "eagle-import") (part "R-EU_R0805"))
    )
    (comp (ref "R5")
      (value "2K2")
      (footprint "eagle-import:R0805")
      (libsource (lib "eagle-import") (part "R-EU_R0805"))
    )
    (comp (ref "R6")
      (value "2K2")
      (footprint "eagle-import:R0805")
      (libsource (lib "eagle-import") (part "R-EU_R0805"))
    )
    (comp (ref "R7")
      (value "2K")
      (footprint "eagle-import:R0805")
      (libsource (lib "eagle-import") (part "R-EU_R0805"))
    )
    (comp (ref "R8")
      (value "100K")
      (footprint "eagle-import:R0805")
      (libsource (lib "eagle-import") (part "R-EU_R0805"))
    )
    (comp (ref "R9")
      (value "100K")
      (footprint "eagle-import:R0805")
      (libsource (lib "eagle-import") (part "R-EU_R0805"))
    )
    (comp (ref "R10")
      (value "100K")
      (footprint "eagle-import:R0805")
      (libsource (lib "eagle-import") (part "R-EU_R0805"))
    )
    (comp (ref "R11")
      (value "910K")
      (footprint "eagle-import:R0805")
      (libsource (lib "eagle-import") (part "R-EU_R0805"))
    )
    (comp (ref "R12")
      (value "680K")
      (footprint "eagle-import:R0805")
      (libsource (lib "eagle-import") (part "R-EU_R0805"))
    )
    (comp (ref "R13")
      (value "100K")
      (footprint "eagle-import:R0805")
      (libsource (lib "eagle-import") (part "R-EU_R0805"))
    )
    (comp (ref "R14")
      (value "100")
      (footprint "eagle-import:R0805")
      (libsource (lib "eagle-import") (part "R-EU_R0805"))
    )
    (comp (ref "R15")
      (value "100")
      (footprint "eagle-import:R0805")
      (libsource (lib "eagle-import") (part "R-EU_R0805"))
    )
    (comp (ref "R16")
      (value "100")
      (footprint "eagle-import:R0805")
      (libsource (lib "eagle-import") (part "R-EU_R0805"))
    )
    (comp (ref "R17")
      (value "100")
      (footprint "eagle-import:R0805")
      (libsource (lib "eagle-import") (part "R-EU_R0805"))
    )
    (comp (ref "R18")
      (value "100")
      (footprint "eagle-import:R0805")
      (libsource (lib "eagle-import") (part "R-EU_R0805"))
    )
    (comp (ref "R19")
      (value "100K")
      (footprint "eagle-import:R0805")
      (libsource (lib "eagle-import") (part "R-EU_R0805"))
    )
    (comp (ref "R20")
      (value "100K")
      (footprint "eagle-import:R0805")
      (libsource (lib "eagle-import") (part "R-EU_R0805"))
    )
    (comp (ref "R21")
      (value "100K")
      (footprint "eagle-import:R0805")
      (libsource (lib "eagle-import") (part "R-EU_R0805"))
    )
    (comp (ref "R22")
      (value "1K")
      (footprint "eagle-import:R0805")
      (libsource (lib "eagle-import") (part "R-EU_R0805"))
    )
    (comp (ref "R23")
      (value "100K")
      (footprint "eagle-import:R0805")
      (libsource (lib "eagle-import") (part "R-EU_R0805"))
    )
    (comp (ref "R24")
      (value "2K2")
      (footprint "eagle-import:R0805")
      (libsource (lib "eagle-import") (part "R-EU_R0805"))
    )
    (comp (ref "R25")
      (value "1K")
      (footprint "eagle-import:R0805")
      (libsource (lib "eagle-import") (part "R-EU_R0805"))
    )
    (comp (ref "R26")
      (value "2K2")
      (footprint "eagle-import:R0805")
      (libsource (lib "eagle-import") (part "R-EU_R0805"))
    )
    (comp (ref "R27")
      (value "100")
      (footprint "eagle-import:R0805")
      (libsource (lib "eagle-import") (part "R-EU_R0805"))
    )
    (comp (ref "R28")
      (value "100")
      (footprint "eagle-import:R0805")
      (libsource (lib "eagle-import") (part "R-EU_R0805"))
    )
    (comp (ref "R29")
      (value "2K2")
      (footprint "eagle-import:R0805")
      (libsource (lib "eagle-import") (part "R-EU_R0805"))
    )
    (comp (ref "R30")
      (value "2K2")
      (footprint "eagle-import:R0805")
      (libsource (lib "eagle-import") (part "R-EU_R0805"))
    )
    (comp (ref "R31")
      (value "2K")
      (footprint "eagle-import:R0805")
      (libsource (lib "eagle-import") (part "R-EU_R0805"))
    )
    (comp (ref "R32")
      (value "100K")
      (footprint "eagle-import:R0805")
      (libsource (lib "eagle-import") (part "R-EU_R0805"))
    )
    (comp (ref "R33")
      (value "100K")
      (footprint "eagle-import:R0805")
      (libsource (lib "eagle-import") (part "R-EU_R0805"))
    )
    (comp (ref "R34")
      (value "100K")
      (footprint "eagle-import:R0805")
      (libsource (lib "eagle-import") (part "R-EU_R0805"))
    )
    (comp (ref "R35")
      (value "910K")
      (footprint "eagle-import:R0805")
      (libsource (lib "eagle-import") (part "R-EU_R0805"))
    )
    (comp (ref "R36")
      (value "680K")
      (footprint "eagle-import:R0805")
      (libsource (lib "eagle-import") (part "R-EU_R0805"))
    )
    (comp (ref "R37")
      (value "100K")
      (footprint "eagle-import:R0805")
      (libsource (lib "eagle-import") (part "R-EU_R0805"))
    )
    (comp (ref "R38")
      (value "100K")
      (footprint "eagle-import:R0805")
      (libsource (lib "eagle-import") (part "R-EU_R0805"))
    )
    (comp (ref "R39")
      (value "1K")
      (footprint "eagle-import:R0805")
      (libsource (lib "eagle-import") (part "R-EU_R0805"))
    )
    (comp (ref "R40")
      (value "1K")
      (footprint "eagle-import:R0805")
      (libsource (lib "eagle-import") (part "R-EU_R0805"))
    )
    (comp (ref "R41")
      (value "100K")
      (footprint "eagle-import:R0805")
      (libsource (lib "eagle-import") (part "R-EU_R0805"))
    )
    (comp (ref "R42")
      (value "100K")
      (footprint "eagle-import:R0805")
      (libsource (lib "eagle-import") (part "R-EU_R0805"))
    )
    (comp (ref "R43")
      (value "100K")
      (footprint "eagle-import:R0805")
      (libsource (lib "eagle-import") (part "R-EU_R0805"))
    )
    (comp (ref "R44")
      (value "100")
      (footprint "eagle-import:R0805")
      (libsource (lib "eagle-import") (part "R-EU_R0805"))
    )
    (comp (ref "R45")
      (value "2K2")
      (footprint "eagle-import:R0805")
      (libsource (lib "eagle-import") (part "R-EU_R0805"))
    )
    (comp (ref "R46")
      (value "2K2")
      (footprint "eagle-import:R0805")
      (libsource (lib "eagle-import") (part "R-EU_R0805"))
    )
    (comp (ref "R47")
      (value "100")
      (footprint "eagle-import:R0805")
      (libsource (lib "eagle-import") (part "R-EU_R0805"))
    )
    (comp (ref "R48")
      (value "100")
      (footprint "eagle-import:R0805")
      (libsource (lib "eagle-import") (part "R-EU_R0805"))
    )
    (comp (ref "R49")
      (value "2K2")
      (footprint "eagle-import:R0805")
      (libsource (lib "eagle-import") (part "R-EU_R0805"))
    )
    (comp (ref "R50")
      (value "2K2")
      (footprint "eagle-import:R0805")
      (libsource (lib "eagle-import") (part "R-EU_R0805"))
    )
    (comp (ref "R51")
      (value "2K")
      (footprint "eagle-import:R0805")
      (libsource (lib "eagle-import") (part "R-EU_R0805"))
    )
    (comp (ref "R52")
      (value "100K")
      (footprint "eagle-import:R0805")
      (libsource (lib "eagle-import") (part "R-EU_R0805"))
    )
    (comp (ref "R53")
      (value "100K")
      (footprint "eagle-import:R0805")
      (libsource (lib "eagle-import") (part "R-EU_R0805"))
    )
    (comp (ref "R54")
      (value "100K")
      (footprint "eagle-import:R0805")
      (libsource (lib "eagle-import") (part "R-EU_R0805"))
    )
    (comp (ref "R55")
      (value "910K")
      (footprint "eagle-import:R0805")
      (libsource (lib "eagle-import") (part "R-EU_R0805"))
    )
    (comp (ref "R56")
      (value "680K")
      (footprint "eagle-import:R0805")
      (libsource (lib "eagle-import") (part "R-EU_R0805"))
    )
    (comp (ref "R57")
      (value "100K")
      (footprint "eagle-import:R0805")
      (libsource (lib "eagle-import") (part "R-EU_R0805"))
    )
    (comp (ref "R58")
      (value "100K")
      (footprint "eagle-import:R0805")
      (libsource (lib "eagle-import") (part "R-EU_R0805"))
    )
    (comp (ref "R59")
      (value "1K")
      (footprint "eagle-import:R0805")
      (libsource (lib "eagle-import") (part "R-EU_R0805"))
    )
    (comp (ref "R60")
      (value "1K")
      (footprint "eagle-import:R0805")
      (libsource (lib "eagle-import") (part "R-EU_R0805"))
    )
    (comp (ref "R61")
      (value "100K")
      (footprint "eagle-import:R0805")
      (libsource (lib "eagle-import") (part "R-EU_R0805"))
    )
    (comp (ref "R62")
      (value "100K")
      (footprint "eagle-import:R0805")
      (libsource (lib "eagle-import") (part "R-EU_R0805"))
    )
    (comp (ref "R63")
      (value "100K")
      (footprint "eagle-import:R0805")
      (libsource (lib "eagle-import") (part "R-EU_R0805"))
    )
    (comp (ref "R64")
      (value "100")
      (footprint "eagle-import:R0805")
      (libsource (lib "eagle-import") (part "R-EU_R0805"))
    )
    (comp (ref "R65")
      (value "2K2")
      (footprint "eagle-import:R0805")
      (libsource (lib "eagle-import") (part "R-EU_R0805"))
    )
    (comp (ref "R66")
      (value "2K2")
      (footprint "eagle-import:R0805")
      (libsource (lib "eagle-import") (part "R-EU_R0805"))
    )
    (comp (ref "R67")
      (value "100")
      (footprint "eagle-import:R0805")
      (libsource (lib "eagle-import") (part "R-EU_R0805"))
    )
    (comp (ref "R68")
      (value "100")
      (footprint "eagle-import:R0805")
      (libsource (lib "eagle-import") (part "R-EU_R0805"))
    )
    (comp (ref "R69")
      (value "2K2")
      (footprint "eagle-import:R0805")
      (libsource (lib "eagle-import") (part "R-EU_R0805"))
    )
    (comp (ref "R70")
      (value "2K2")
      (footprint "eagle-import:R0805")
      (libsource (lib "eagle-import") (part "R-EU_R0805"))
    )
    (comp (ref "R71")
      (value "2K")
      (footprint "eagle-import:R0805")
      (libsource (lib "eagle-import") (part "R-EU_R0805"))
    )
    (comp (ref "R72")
      (value "100K")
      (footprint "eagle-import:R0805")
      (libsource (lib "eagle-import") (part "R-EU_R0805"))
    )
    (comp (ref "R73")
      (value "100K")
      (footprint "eagle-import:R0805")
      (libsource (lib "eagle-import") (part "R-EU_R0805"))
    )
    (comp (ref "R74")
      (value "100K")
      (footprint "eagle-import:R0805")
      (libsource (lib "eagle-import") (part "R-EU_R0805"))
    )
    (comp (ref "R75")
      (value "910K")
      (footprint "eagle-import:R0805")
      (libsource (lib "eagle-import") (part "R-EU_R0805"))
    )
    (comp (ref "R76")
      (value "680K")
      (footprint "eagle-import:R0805")
      (libsource (lib "eagle-import") (part "R-EU_R0805"))
    )
    (comp (ref "R77")
      (value "100K")
      (footprint "eagle-import:R0805")
      (libsource (lib "eagle-import") (part "R-EU_R0805"))
    )
    (comp (ref "R78")
      (value "100K")
      (footprint "eagle-import:R0805")
      (libsource (lib "eagle-import") (part "R-EU_R0805"))
    )
    (comp (ref "R79")
      (value "1K")
      (footprint "eagle-import:R0805")
      (libsource (lib "eagle-import") (part "R-EU_R0805"))
    )
    (comp (ref "R80")
      (value "1K")
      (footprint "eagle-import:R0805")
      (libsource (lib "eagle-import") (part "R-EU_R0805"))
    )
    (comp (ref "R81")
      (value "100K")
      (footprint "eagle-import:R0805")
      (libsource (lib "eagle-import") (part "R-EU_R0805"))
    )
    (comp (ref "R82")
      (value "100K")
      (footprint "eagle-import:R0805")
      (libsource (lib "eagle-import") (part "R-EU_R0805"))
    )
    (comp (ref "R83")
      (value "100K")
      (footprint "eagle-import:R0805")
      (libsource (lib "eagle-import") (part "R-EU_R0805"))
    )
    (comp (ref "R84")
      (value "100")
      (footprint "eagle-import:R0805")
      (libsource (lib "eagle-import") (part "R-EU_R0805"))
    )
    (comp (ref "R85")
      (value "2K2")
      (footprint "eagle-import:R0805")
      (libsource (lib "eagle-import") (part "R-EU_R0805"))
    )
    (comp (ref "R86")
      (value "2K2")
      (footprint "eagle-import:R0805")
      (libsource (lib "eagle-import") (part "R-EU_R0805"))
    )
    (comp (ref "R87")
      (value "100")
      (footprint "eagle-import:R0805")
      (libsource (lib "eagle-import") (part "R-EU_R0805"))
    )
    (comp (ref "R88")
      (value "100")
      (footprint "eagle-import:R0805")
      (libsource (lib "eagle-import") (part "R-EU_R0805"))
    )
    (comp (ref "R89")
      (value "2K2")
      (footprint "eagle-import:R0805")
      (libsource (lib "eagle-import") (part "R-EU_R0805"))
    )
    (comp (ref "R90")
      (value "2K2")
      (footprint "eagle-import:R0805")
      (libsource (lib "eagle-import") (part "R-EU_R0805"))
    )
    (comp (ref "R91")
      (value "2K")
      (footprint "eagle-import:R0805")
      (libsource (lib "eagle-import") (part "R-EU_R0805"))
    )
    (comp (ref "R92")
      (value "100K")
      (footprint "eagle-import:R0805")
      (libsource (lib "eagle-import") (part "R-EU_R0805"))
    )
    (comp (ref "R93")
      (value "100K")
      (footprint "eagle-import:R0805")
      (libsource (lib "eagle-import") (part "R-EU_R0805"))
    )
    (comp (ref "R94")
      (value "100K")
      (footprint "eagle-import:R0805")
      (libsource (lib "eagle-import") (part "R-EU_R0805"))
    )
    (comp (ref "R95")
      (value "910K")
      (footprint "eagle-import:R0805")
      (libsource (lib "eagle-import") (part "R-EU_R0805"))
    )
    (comp (ref "R96")
      (value "680K")
      (footprint "eagle-import:R0805")
      (libsource (lib "eagle-import") (part "R-EU_R0805"))
    )
    (comp (ref "R97")
      (value "100K")
      (footprint "eagle-import:R0805")
      (libsource (lib "eagle-import") (part "R-EU_R0805"))
    )
    (comp (ref "R98")
      (value "100K")
      (footprint "eagle-import:R0805")
      (libsource (lib "eagle-import") (part "R-EU_R0805"))
    )
    (comp (ref "R99")
      (value "1K")
      (footprint "eagle-import:R0805")
      (libsource (lib "eagle-import") (part "R-EU_R0805"))
    )
    (comp (ref "R100")
      (value "1K")
      (footprint "eagle-import:R0805")
      (libsource (lib "eagle-import") (part "R-EU_R0805"))
    )
    (comp (ref "R101")
      (value "100K")
      (footprint "eagle-import:R0805")
      (libsource (lib "eagle-import") (part "R-EU_R0805"))
    )
    (comp (ref "R102")
      (value "100K")
      (footprint "eagle-import:R0805")
      (libsource (lib "eagle-import") (part "R-EU_R0805"))
    )
    (comp (ref "R103")
      (value "100K")
      (footprint "eagle-import:R0805")
      (libsource (lib "eagle-import") (part "R-EU_R0805"))
    )
    (comp (ref "R104")
      (value "100")
      (footprint "eagle-import:R0805")
      (libsource (lib "eagle-import") (part "R-EU_R0805"))
    )
    (comp (ref "R105")
      (value "2K2")
      (footprint "eagle-import:R0805")
      (libsource (lib "eagle-import") (part "R-EU_R0805"))
    )
    (comp (ref "R106")
      (value "2K2")
      (footprint "eagle-import:R0805")
      (libsource (lib "eagle-import") (part "R-EU_R0805"))
    )
    (comp (ref "R107")
      (value "100")
      (footprint "eagle-import:R0805")
      (libsource (lib "eagle-import") (part "R-EU_R0805"))
    )
    (comp (ref "R108")
      (value "100")
      (footprint "eagle-import:R0805")
      (libsource (lib "eagle-import") (part "R-EU_R0805"))
    )
    (comp (ref "R109")
      (value "2K2")
      (footprint "eagle-import:R0805")
      (libsource (lib "eagle-import") (part "R-EU_R0805"))
    )
    (comp (ref "R110")
      (value "2K2")
      (footprint "eagle-import:R0805")
      (libsource (lib "eagle-import") (part "R-EU_R0805"))
    )
    (comp (ref "R111")
      (value "2K")
      (footprint "eagle-import:R0805")
      (libsource (lib "eagle-import") (part "R-EU_R0805"))
    )
    (comp (ref "R112")
      (value "100K")
      (footprint "eagle-import:R0805")
      (libsource (lib "eagle-import") (part "R-EU_R0805"))
    )
    (comp (ref "R113")
      (value "100K")
      (footprint "eagle-import:R0805")
      (libsource (lib "eagle-import") (part "R-EU_R0805"))
    )
    (comp (ref "R114")
      (value "100K")
      (footprint "eagle-import:R0805")
      (libsource (lib "eagle-import") (part "R-EU_R0805"))
    )
    (comp (ref "R115")
      (value "910K")
      (footprint "eagle-import:R0805")
      (libsource (lib "eagle-import") (part "R-EU_R0805"))
    )
    (comp (ref "R116")
      (value "680K")
      (footprint "eagle-import:R0805")
      (libsource (lib "eagle-import") (part "R-EU_R0805"))
    )
    (comp (ref "R117")
      (value "100K")
      (footprint "eagle-import:R0805")
      (libsource (lib "eagle-import") (part "R-EU_R0805"))
    )
    (comp (ref "R118")
      (value "100K")
      (footprint "eagle-import:R0805")
      (libsource (lib "eagle-import") (part "R-EU_R0805"))
    )
    (comp (ref "R119")
      (value "1K")
      (footprint "eagle-import:R0805")
      (libsource (lib "eagle-import") (part "R-EU_R0805"))
    )
    (comp (ref "R120")
      (value "1K")
      (footprint "eagle-import:R0805")
      (libsource (lib "eagle-import") (part "R-EU_R0805"))
    )
    (comp (ref "R121")
      (value "100K")
      (footprint "eagle-import:R0805")
      (libsource (lib "eagle-import") (part "R-EU_R0805"))
    )
    (comp (ref "R122")
      (value "100K")
      (footprint "eagle-import:R0805")
      (libsource (lib "eagle-import") (part "R-EU_R0805"))
    )
    (comp (ref "R123")
      (value "100K")
      (footprint "eagle-import:R0805")
      (libsource (lib "eagle-import") (part "R-EU_R0805"))
    )
    (comp (ref "R124")
      (value "100")
      (footprint "eagle-import:R0805")
      (libsource (lib "eagle-import") (part "R-EU_R0805"))
    )
    (comp (ref "R125")
      (value "2K2")
      (footprint "eagle-import:R0805")
      (libsource (lib "eagle-import") (part "R-EU_R0805"))
    )
    (comp (ref "R126")
      (value "2K2")
      (footprint "eagle-import:R0805")
      (libsource (lib "eagle-import") (part "R-EU_R0805"))
    )
    (comp (ref "R127")
      (value "100")
      (footprint "eagle-import:R0805")
      (libsource (lib "eagle-import") (part "R-EU_R0805"))
    )
    (comp (ref "R128")
      (value "100")
      (footprint "eagle-import:R0805")
      (libsource (lib "eagle-import") (part "R-EU_R0805"))
    )
    (comp (ref "R129")
      (value "2K2")
      (footprint "eagle-import:R0805")
      (libsource (lib "eagle-import") (part "R-EU_R0805"))
    )
    (comp (ref "R130")
      (value "2K2")
      (footprint "eagle-import:R0805")
      (libsource (lib "eagle-import") (part "R-EU_R0805"))
    )
    (comp (ref "R131")
      (value "2K")
      (footprint "eagle-import:R0805")
      (libsource (lib "eagle-import") (part "R-EU_R0805"))
    )
    (comp (ref "R132")
      (value "100K")
      (footprint "eagle-import:R0805")
      (libsource (lib "eagle-import") (part "R-EU_R0805"))
    )
    (comp (ref "R133")
      (value "100K")
      (footprint "eagle-import:R0805")
      (libsource (lib "eagle-import") (part "R-EU_R0805"))
    )
    (comp (ref "R134")
      (value "100K")
      (footprint "eagle-import:R0805")
      (libsource (lib "eagle-import") (part "R-EU_R0805"))
    )
    (comp (ref "R135")
      (value "910K")
      (footprint "eagle-import:R0805")
      (libsource (lib "eagle-import") (part "R-EU_R0805"))
    )
    (comp (ref "R136")
      (value "680K")
      (footprint "eagle-import:R0805")
      (libsource (lib "eagle-import") (part "R-EU_R0805"))
    )
    (comp (ref "R137")
      (value "100K")
      (footprint "eagle-import:R0805")
      (libsource (lib "eagle-import") (part "R-EU_R0805"))
    )
    (comp (ref "R138")
      (value "100K")
      (footprint "eagle-import:R0805")
      (libsource (lib "eagle-import") (part "R-EU_R0805"))
    )
    (comp (ref "R139")
      (value "1K")
      (footprint "eagle-import:R0805")
      (libsource (lib "eagle-import") (part "R-EU_R0805"))
    )
    (comp (ref "R140")
      (value "1K")
      (footprint "eagle-import:R0805")
      (libsource (lib "eagle-import") (part "R-EU_R0805"))
    )
    (comp (ref "R141")
      (value "100K")
      (footprint "eagle-import:R0805")
      (libsource (lib "eagle-import") (part "R-EU_R0805"))
    )
    (comp (ref "R142")
      (value "100K")
      (footprint "eagle-import:R0805")
      (libsource (lib "eagle-import") (part "R-EU_R0805"))
    )
    (comp (ref "R143")
      (value "100K")
      (footprint "eagle-import:R0805")
      (libsource (lib "eagle-import") (part "R-EU_R0805"))
    )
    (comp (ref "R144")
      (value "100")
      (footprint "eagle-import:R0805")
      (libsource (lib "eagle-import") (part "R-EU_R0805"))
    )
    (comp (ref "R145")
      (value "2K2")
      (footprint "eagle-import:R0805")
      (libsource (lib "eagle-import") (part "R-EU_R0805"))
    )
    (comp (ref "R146")
      (value "2K2")
      (footprint "eagle-import:R0805")
      (libsource (lib "eagle-import") (part "R-EU_R0805"))
    )
    (comp (ref "R147")
      (value "100")
      (footprint "eagle-import:R0805")
      (libsource (lib "eagle-import") (part "R-EU_R0805"))
    )
    (comp (ref "R148")
      (value "100")
      (footprint "eagle-import:R0805")
      (libsource (lib "eagle-import") (part "R-EU_R0805"))
    )
    (comp (ref "R149")
      (value "2K2")
      (footprint "eagle-import:R0805")
      (libsource (lib "eagle-import") (part "R-EU_R0805"))
    )
    (comp (ref "R150")
      (value "2K2")
      (footprint "eagle-import:R0805")
      (libsource (lib "eagle-import") (part "R-EU_R0805"))
    )
    (comp (ref "R151")
      (value "2K")
      (footprint "eagle-import:R0805")
      (libsource (lib "eagle-import") (part "R-EU_R0805"))
    )
    (comp (ref "R152")
      (value "100K")
      (footprint "eagle-import:R0805")
      (libsource (lib "eagle-import") (part "R-EU_R0805"))
    )
    (comp (ref "R153")
      (value "100K")
      (footprint "eagle-import:R0805")
      (libsource (lib "eagle-import") (part "R-EU_R0805"))
    )
    (comp (ref "R154")
      (value "100K")
      (footprint "eagle-import:R0805")
      (libsource (lib "eagle-import") (part "R-EU_R0805"))
    )
    (comp (ref "R155")
      (value "910K")
      (footprint "eagle-import:R0805")
      (libsource (lib "eagle-import") (part "R-EU_R0805"))
    )
    (comp (ref "R156")
      (value "680K")
      (footprint "eagle-import:R0805")
      (libsource (lib "eagle-import") (part "R-EU_R0805"))
    )
    (comp (ref "R157")
      (value "100K")
      (footprint "eagle-import:R0805")
      (libsource (lib "eagle-import") (part "R-EU_R0805"))
    )
    (comp (ref "R158")
      (value "100K")
      (footprint "eagle-import:R0805")
      (libsource (lib "eagle-import") (part "R-EU_R0805"))
    )
    (comp (ref "R159")
      (value "1K")
      (footprint "eagle-import:R0805")
      (libsource (lib "eagle-import") (part "R-EU_R0805"))
    )
    (comp (ref "R160")
      (value "1K")
      (footprint "eagle-import:R0805")
      (libsource (lib "eagle-import") (part "R-EU_R0805"))
    )
    (comp (ref "R161")
      (value "100K")
      (footprint "eagle-import:R0805")
      (libsource (lib "eagle-import") (part "R-EU_R0805"))
    )
    (comp (ref "R162")
      (value "100K")
      (footprint "eagle-import:R0805")
      (libsource (lib "eagle-import") (part "R-EU_R0805"))
    )
    (comp (ref "R163")
      (value "100K")
      (footprint "eagle-import:R0805")
      (libsource (lib "eagle-import") (part "R-EU_R0805"))
    )
    (comp (ref "R164")
      (value "100")
      (footprint "eagle-import:R0805")
      (libsource (lib "eagle-import") (part "R-EU_R0805"))
    )
  )
  (nets
    (net (code "1") (name "+3.3V") (class "Default")
      (node (ref "C17") (pin "1") (pinfunction "1_1") (pintype "passive"))
      (node (ref "C21") (pin "+") (pinfunction "+_+") (pintype "passive"))
      (node (ref "C44") (pin "1") (pinfunction "1_1") (pintype "passive"))
      (node (ref "C7") (pin "1") (pinfunction "1_1") (pintype "passive"))
      (node (ref "IC3") (pin "14") (pinfunction "SYNC/PDWN_14") (pintype "bidirectional"))
      (node (ref "IC3") (pin "15") (pinfunction "RESET_15") (pintype "bidirectional"))
      (node (ref "IC3") (pin "16") (pinfunction "DVDD_16") (pintype "bidirectional"))
      (node (ref "IC5") (pin "3") (pinfunction "VO_3") (pintype "passive"))
      (node (ref "IC6") (pin "1") (pinfunction "VDD1_1") (pintype "bidirectional"))
      (node (ref "IC6") (pin "7") (pinfunction "VE1_7") (pintype "bidirectional"))
    )
    (net (code "2") (name "+5VA") (class "Default")
      (node (ref "C107") (pin "2") (pinfunction "2_2") (pintype "passive"))
      (node (ref "C108") (pin "1") (pinfunction "1_1") (pintype "passive"))
      (node (ref "C112") (pin "1") (pinfunction "1_1") (pintype "passive"))
      (node (ref "C121") (pin "2") (pinfunction "2_2") (pintype "passive"))
      (node (ref "C122") (pin "1") (pinfunction "1_1") (pintype "passive"))
      (node (ref "C126") (pin "1") (pinfunction "1_1") (pintype "passive"))
      (node (ref "C15") (pin "1") (pinfunction "1_1") (pintype "passive"))
      (node (ref "C26") (pin "1") (pinfunction "1_1") (pintype "passive"))
      (node (ref "C27") (pin "+") (pinfunction "+_+") (pintype "passive"))
      (node (ref "C34") (pin "2") (pinfunction "2_2") (pintype "passive"))
      (node (ref "C35") (pin "1") (pinfunction "1_1") (pintype "passive"))
      (node (ref "C39") (pin "1") (pinfunction "1_1") (pintype "passive"))
      (node (ref "C49") (pin "2") (pinfunction "2_2") (pintype "passive"))
      (node (ref "C5") (pin "2") (pinfunction "2_2") (pintype "passive"))
      (node (ref "C50") (pin "1") (pinfunction "1_1") (pintype "passive"))
      (node (ref "C55") (pin "1") (pinfunction "1_1") (pintype "passive"))
      (node (ref "C6") (pin "1") (pinfunction "1_1") (pintype "passive"))
      (node (ref "C65") (pin "2") (pinfunction "2_2") (pintype "passive"))
      (node (ref "C66") (pin "1") (pinfunction "1_1") (pintype "passive"))
      (node (ref "C70") (pin "1") (pinfunction "1_1") (pintype "passive"))
      (node (ref "C79") (pin "2") (pinfunction "2_2") (pintype "passive"))
      (node (ref "C8") (pin "1") (pinfunction "1_1") (pintype "passive"))
      (node (ref "C80") (pin "1") (pinfunction "1_1") (pintype "passive"))
      (node (ref "C84") (pin "1") (pinfunction "1_1") (pintype "passive"))
      (node (ref "C93") (pin "2") (pinfunction "2_2") (pintype "passive"))
      (node (ref "C94") (pin "1") (pinfunction "1_1") (pintype "passive"))
      (node (ref "C98") (pin "1") (pinfunction "1_1") (pintype "passive"))
      (node (ref "D1") (pin "2") (pinfunction "C_2") (pintype "passive"))
      (node (ref "D10") (pin "2") (pinfunction "C_2") (pintype "passive"))
      (node (ref "D11") (pin "2") (pinfunction "C_2") (pintype "passive"))
      (node (ref "D12") (pin "2") (pinfunction "C_2") (pintype "passive"))
      (node (ref "D13") (pin "2") (pinfunction "C_2") (pintype "passive"))
      (node (ref "D14") (pin "2") (pinfunction "C_2") (pintype "passive"))
      (node (ref "D15") (pin "2") (pinfunction "C_2") (pintype "passive"))
      (node (ref "D16") (pin "2") (pinfunction "C_2") (pintype "passive"))
      (node (ref "D17") (pin "2") (pinfunction "C_2") (pintype "passive"))
      (node (ref "D18") (pin "2") (pinfunction "C_2") (pintype "passive"))
      (node (ref "D19") (pin "2") (pinfunction "C_2") (pintype "passive"))
      (node (ref "D2") (pin "2") (pinfunction "C_2") (pintype "passive"))
      (node (ref "D20") (pin "2") (pinfunction "C_2") (pintype "passive"))
      (node (ref "D21") (pin "2") (pinfunction "C_2") (pintype "passive"))
      (node (ref "D22") (pin "2") (pinfunction "C_2") (pintype "passive"))
      (node (ref "D23") (pin "2") (pinfunction "C_2") (pintype "passive"))
      (node (ref "D24") (pin "2") (pinfunction "C_2") (pintype "passive"))
      (node (ref "D25") (pin "2") (pinfunction "C_2") (pintype "passive"))
      (node (ref "D26") (pin "2") (pinfunction "C_2") (pintype "passive"))
      (node (ref "D27") (pin "2") (pinfunction "C_2") (pintype "passive"))
      (node (ref "D28") (pin "2") (pinfunction "C_2") (pintype "passive"))
      (node (ref "D29") (pin "2") (pinfunction "C_2") (pintype "passive"))
      (node (ref "D3") (pin "2") (pinfunction "C_2") (pintype "passive"))
      (node (ref "D30") (pin "2") (pinfunction "C_2") (pintype "passive"))
      (node (ref "D31") (pin "2") (pinfunction "C_2") (pintype "passive"))
      (node (ref "D32") (pin "2") (pinfunction "C_2") (pintype "passive"))
      (node (ref "D4") (pin "2") (pinfunction "C_2") (pintype "passive"))
      (node (ref "D5") (pin "2") (pinfunction "C_2") (pintype "passive"))
      (node (ref "D6") (pin "2") (pinfunction "C_2") (pintype "passive"))
      (node (ref "D7") (pin "2") (pinfunction "C_2") (pintype "passive"))
      (node (ref "D8") (pin "2") (pinfunction "C_2") (pintype "passive"))
      (node (ref "D9") (pin "2") (pinfunction "C_2") (pintype "passive"))
      (node (ref "IC1") (pin "8") (pinfunction "+VS_8") (pintype "power_in"))
      (node (ref "IC10") (pin "5") (pinfunction "+VS_5") (pintype "power_in"))
      (node (ref "IC11") (pin "8") (pinfunction "+VS_8") (pintype "power_in"))
      (node (ref "IC12") (pin "4") (pinfunction "+VS_4") (pintype "power_in"))
      (node (ref "IC13") (pin "5") (pinfunction "+VS_5") (pintype "power_in"))
      (node (ref "IC14") (pin "8") (pinfunction "+VS_8") (pintype "power_in"))
      (node (ref "IC15") (pin "4") (pinfunction "+VS_4") (pintype "power_in"))
      (node (ref "IC16") (pin "5") (pinfunction "+VS_5") (pintype "power_in"))
      (node (ref "IC17") (pin "8") (pinfunction "+VS_8") (pintype "power_in"))
      (node (ref "IC18") (pin "4") (pinfunction "+VS_4") (pintype "power_in"))
      (node (ref "IC19") (pin "5") (pinfunction "+VS_5") (pintype "power_in"))
      (node (ref "IC2") (pin "4") (pinfunction "+VS_4") (pintype "power_in"))
      (node (ref "IC20") (pin "8") (pinfunction "+VS_8") (pintype "power_in"))
      (node (ref "IC21") (pin "4") (pinfunction "+VS_4") (pintype "power_in"))
      (node (ref "IC22") (pin "5") (pinfunction "+VS_5") (pintype "power_in"))
      (node (ref "IC23") (pin "8") (pinfunction "+VS_8") (pintype "power_in"))
      (node (ref "IC24") (pin "4") (pinfunction "+VS_4") (pintype "power_in"))
      (node (ref "IC25") (pin "5") (pinfunction "+VS_5") (pintype "power_in"))
      (node (ref "IC26") (pin "8") (pinfunction "+VS_8") (pintype "power_in"))
      (node (ref "IC27") (pin "4") (pinfunction "+VS_4") (pintype "power_in"))
      (node (ref "IC28") (pin "5") (pinfunction "+VS_5") (pintype "power_in"))
      (node (ref "IC3") (pin "1") (pinfunction "AVDD_1") (pintype "bidirectional"))
      (node (ref "IC4") (pin "5") (pinfunction "+VS_5") (pintype "power_in"))
      (node (ref "IC7") (pin "1") (pinfunction "VIN_1") (pintype "bidirectional"))
      (node (ref "IC8") (pin "8") (pinfunction "+VS_8") (pintype "power_in"))
      (node (ref "IC9") (pin "4") (pinfunction "+VS_4") (pintype "power_in"))
      (node (ref "L1") (pin "1") (pinfunction "1_1") (pintype "passive"))
    )
    (net (code "3") (name "-5VA") (class "Default")
      (node (ref "C106") (pin "1") (pinfunction "1_1") (pintype "passive"))
      (node (ref "C109") (pin "2") (pinfunction "2_2") (pintype "passive"))
      (node (ref "C11") (pin "2") (pinfunction "2_2") (pintype "passive"))
      (node (ref "C120") (pin "1") (pinfunction "1_1") (pintype "passive"))
      (node (ref "C123") (pin "2") (pinfunction "2_2") (pintype "passive"))
      (node (ref "C28") (pin "2") (pinfunction "2_2") (pintype "passive"))
      (node (ref "C29") (pin "-") (pinfunction "-_-") (pintype "passive"))
      (node (ref "C33") (pin "1") (pinfunction "1_1") (pintype "passive"))
      (node (ref "C36") (pin "2") (pinfunction "2_2") (pintype "passive"))
      (node (ref "C4") (pin "1") (pinfunction "1_1") (pintype "passive"))
      (node (ref "C48") (pin "1") (pinfunction "1_1") (pintype "passive"))
      (node (ref "C51") (pin "2") (pinfunction "2_2") (pintype "passive"))
      (node (ref "C64") (pin "1") (pinfunction "1_1") (pintype "passive"))
      (node (ref "C67") (pin "2") (pinfunction "2_2") (pintype "passive"))
      (node (ref "C78") (pin "1") (pinfunction "1_1") (pintype "passive"))
      (node (ref "C81") (pin "2") (pinfunction "2_2") (pintype "passive"))
      (node (ref "C92") (pin "1") (pinfunction "1_1") (pintype "passive"))
      (node (ref "C95") (pin "2") (pinfunction "2_2") (pintype "passive"))
      (node (ref "D1") (pin "1") (pinfunction "A_1") (pintype "passive"))
      (node (ref "D10") (pin "1") (pinfunction "A_1") (pintype "passive"))
      (node (ref "D11") (pin "1") (pinfunction "A_1") (pintype "passive"))
      (node (ref "D12") (pin "1") (pinfunction "A_1") (pintype "passive"))
      (node (ref "D13") (pin "1") (pinfunction "A_1") (pintype "passive"))
      (node (ref "D14") (pin "1") (pinfunction "A_1") (pintype "passive"))
      (node (ref "D15") (pin "1") (pinfunction "A_1") (pintype "passive"))
      (node (ref "D16") (pin "1") (pinfunction "A_1") (pintype "passive"))
      (node (ref "D17") (pin "1") (pinfunction "A_1") (pintype "passive"))
      (node (ref "D18") (pin "1") (pinfunction "A_1") (pintype "passive"))
      (node (ref "D19") (pin "1") (pinfunction "A_1") (pintype "passive"))
      (node (ref "D2") (pin "1") (pinfunction "A_1") (pintype "passive"))
      (node (ref "D20") (pin "1") (pinfunction "A_1") (pintype "passive"))
      (node (ref "D21") (pin "1") (pinfunction "A_1") (pintype "passive"))
      (node (ref "D22") (pin "1") (pinfunction "A_1") (pintype "passive"))
      (node (ref "D23") (pin "1") (pinfunction "A_1") (pintype "passive"))
      (node (ref "D24") (pin "1") (pinfunction "A_1") (pintype "passive"))
      (node (ref "D25") (pin "1") (pinfunction "A_1") (pintype "passive"))
      (node (ref "D26") (pin "1") (pinfunction "A_1") (pintype "passive"))
      (node (ref "D27") (pin "1") (pinfunction "A_1") (pintype "passive"))
      (node (ref "D28") (pin "1") (pinfunction "A_1") (pintype "passive"))
      (node (ref "D29") (pin "1") (pinfunction "A_1") (pintype "passive"))
      (node (ref "D3") (pin "1") (pinfunction "A_1") (pintype "passive"))
      (node (ref "D30") (pin "1") (pinfunction "A_1") (pintype "passive"))
      (node (ref "D31") (pin "1") (pinfunction "A_1") (pintype "passive"))
      (node (ref "D32") (pin "1") (pinfunction "A_1") (pintype "passive"))
      (node (ref "D4") (pin "1") (pinfunction "A_1") (pintype "passive"))
      (node (ref "D5") (pin "1") (pinfunction "A_1") (pintype "passive"))
      (node (ref "D6") (pin "1") (pinfunction "A_1") (pintype "passive"))
      (node (ref "D7") (pin "1") (pinfunction "A_1") (pintype "passive"))
      (node (ref "D8") (pin "1") (pinfunction "A_1") (pintype "passive"))
      (node (ref "D9") (pin "1") (pinfunction "A_1") (pintype "passive"))
      (node (ref "IC1") (pin "5") (pinfunction "-VS_5") (pintype "power_in"))
      (node (ref "IC11") (pin "5") (pinfunction "-VS_5") (pintype "power_in"))
      (node (ref "IC12") (pin "11") (pinfunction "-VS_11") (pintype "power_in"))
      (node (ref "IC14") (pin "5") (pinfunction "-VS_5") (pintype "power_in"))
      (node (ref "IC15") (pin "11") (pinfunction "-VS_11") (pintype "power_in"))
      (node (ref "IC17") (pin "5") (pinfunction "-VS_5") (pintype "power_in"))
      (node (ref "IC18") (pin "11") (pinfunction "-VS_11") (pintype "power_in"))
      (node (ref "IC2") (pin "11") (pinfunction "-VS_11") (pintype "power_in"))
      (node (ref "IC20") (pin "5") (pinfunction "-VS_5") (pintype "power_in"))
      (node (ref "IC21") (pin "11") (pinfunction "-VS_11") (pintype "power_in"))
      (node (ref "IC23") (pin "5") (pinfunction "-VS_5") (pintype "power_in"))
      (node (ref "IC24") (pin "11") (pinfunction "-VS_11") (pintype "power_in"))
      (node (ref "IC26") (pin "5") (pinfunction "-VS_5") (pintype "power_in"))
      (node (ref "IC27") (pin "11") (pinfunction "-VS_11") (pintype "power_in"))
      (node (ref "IC8") (pin "5") (pinfunction "-VS_5") (pintype "power_in"))
      (node (ref "IC9") (pin "11") (pinfunction "-VS_11") (pintype "power_in"))
      (node (ref "L2") (pin "1") (pinfunction "1_1") (pintype "passive"))
    )
    (net (code "4") (name "GND") (class "Default")
      (node (ref "C10") (pin "2") (pinfunction "2_2") (pintype "passive"))
      (node (ref "C100") (pin "2") (pinfunction "2_2") (pintype "passive"))
      (node (ref "C102") (pin "1") (pinfunction "1_1") (pintype "passive"))
      (node (ref "C104") (pin "2") (pinfunction "2_2") (pintype "passive"))
      (node (ref "C105") (pin "1") (pinfunction "1_1") (pintype "passive"))
      (node (ref "C106") (pin "2") (pinfunction "2_2") (pintype "passive"))
      (node (ref "C107") (pin "1") (pinfunction "1_1") (pintype "passive"))
      (node (ref "C108") (pin "2") (pinfunction "2_2") (pintype "passive"))
      (node (ref "C109") (pin "1") (pinfunction "1_1") (pintype "passive"))
      (node (ref "C11") (pin "1") (pinfunction "1_1") (pintype "passive"))
      (node (ref "C112") (pin "2") (pinfunction "2_2") (pintype "passive"))
      (node (ref "C113") (pin "1") (pinfunction "1_1") (pintype "passive"))
      (node (ref "C114") (pin "2") (pinfunction "2_2") (pintype "passive"))
      (node (ref "C116") (pin "1") (pinfunction "1_1") (pintype "passive"))
      (node (ref "C118") (pin "2") (pinfunction "2_2") (pintype "passive"))
      (node (ref "C119") (pin "1") (pinfunction "1_1") (pintype "passive"))
      (node (ref "C120") (pin "2") (pinfunction "2_2") (pintype "passive"))
      (node (ref "C121") (pin "1") (pinfunction "1_1") (pintype "passive"))
      (node (ref "C122") (pin "2") (pinfunction "2_2") (pintype "passive"))
      (node (ref "C123") (pin "1") (pinfunction "1_1") (pintype "passive"))
      (node (ref "C126") (pin "2") (pinfunction "2_2") (pintype "passive"))
      (node (ref "C127") (pin "1") (pinfunction "1_1") (pintype "passive"))
      (node (ref "C128") (pin "2") (pinfunction "2_2") (pintype "passive"))
      (node (ref "C130") (pin "1") (pinfunction "1_1") (pintype "passive"))
      (node (ref "C14") (pin "2") (pinfunction "2_2") (pintype "passive"))
      (node (ref "C15") (pin "2") (pinfunction "2_2") (pintype "passive"))
      (node (ref "C16") (pin "2") (pinfunction "2_2") (pintype "passive"))
      (node (ref "C17") (pin "2") (pinfunction "2_2") (pintype "passive"))
      (node (ref "C19") (pin "1") (pinfunction "1_1") (pintype "passive"))
      (node (ref "C2") (pin "2") (pinfunction "2_2") (pintype "passive"))
      (node (ref "C20") (pin "-") (pinfunction "-_-") (pintype "passive"))
      (node (ref "C21") (pin "-") (pinfunction "-_-") (pintype "passive"))
      (node (ref "C22") (pin "-") (pinfunction "-_-") (pintype "passive"))
      (node (ref "C23") (pin "+") (pinfunction "+_+") (pintype "passive"))
      (node (ref "C24") (pin "2") (pinfunction "2_2") (pintype "passive"))
      (node (ref "C25") (pin "1") (pinfunction "1_1") (pintype "passive"))
      (node (ref "C26") (pin "2") (pinfunction "2_2") (pintype "passive"))
      (node (ref "C27") (pin "-") (pinfunction "-_-") (pintype "passive"))
      (node (ref "C28") (pin "1") (pinfunction "1_1") (pintype "passive"))
      (node (ref "C29") (pin "+") (pinfunction "+_+") (pintype "passive"))
      (node (ref "C3") (pin "1") (pinfunction "1_1") (pintype "passive"))
      (node (ref "C31") (pin "2") (pinfunction "2_2") (pintype "passive"))
      (node (ref "C32") (pin "1") (pinfunction "1_1") (pintype "passive"))
      (node (ref "C33") (pin "2") (pinfunction "2_2") (pintype "passive"))
      (node (ref "C34") (pin "1") (pinfunction "1_1") (pintype "passive"))
      (node (ref "C35") (pin "2") (pinfunction "2_2") (pintype "passive"))
      (node (ref "C36") (pin "1") (pinfunction "1_1") (pintype "passive"))
      (node (ref "C39") (pin "2") (pinfunction "2_2") (pintype "passive"))
      (node (ref "C4") (pin "2") (pinfunction "2_2") (pintype "passive"))
      (node (ref "C40") (pin "1") (pinfunction "1_1") (pintype "passive"))
      (node (ref "C41") (pin "2") (pinfunction "2_2") (pintype "passive"))
      (node (ref "C43") (pin "1") (pinfunction "1_1") (pintype "passive"))
      (node (ref "C44") (pin "2") (pinfunction "2_2") (pintype "passive"))
      (node (ref "C46") (pin "2") (pinfunction "2_2") (pintype "passive"))
      (node (ref "C47") (pin "1") (pinfunction "1_1") (pintype "passive"))
      (node (ref "C48") (pin "2") (pinfunction "2_2") (pintype "passive"))
      (node (ref "C49") (pin "1") (pinfunction "1_1") (pintype "passive"))
      (node (ref "C5") (pin "1") (pinfunction "1_1") (pintype "passive"))
      (node (ref "C50") (pin "2") (pinfunction "2_2") (pintype "passive"))
      (node (ref "C51") (pin "1") (pinfunction "1_1") (pintype "passive"))
      (node (ref "C52") (pin "1") (pinfunction "1_1") (pintype "passive"))
      (node (ref "C55") (pin "2") (pinfunction "2_2") (pintype "passive"))
      (node (ref "C57") (pin "1") (pinfunction "1_1") (pintype "passive"))
      (node (ref "C58") (pin "2") (pinfunction "2_2") (pintype "passive"))
      (node (ref "C6") (pin "2") (pinfunction "2_2") (pintype "passive"))
      (node (ref "C60") (pin "1") (pinfunction "1_1") (pintype "passive"))
      (node (ref "C62") (pin "2") (pinfunction "2_2") (pintype "passive"))
      (node (ref "C63") (pin "1") (pinfunction "1_1") (pintype "passive"))
      (node (ref "C64") (pin "2") (pinfunction "2_2") (pintype "passive"))
      (node (ref "C65") (pin "1") (pinfunction "1_1") (pintype "passive"))
      (node (ref "C66") (pin "2") (pinfunction "2_2") (pintype "passive"))
      (node (ref "C67") (pin "1") (pinfunction "1_1") (pintype "passive"))
      (node (ref "C7") (pin "2") (pinfunction "2_2") (pintype "passive"))
      (node (ref "C70") (pin "2") (pinfunction "2_2") (pintype "passive"))
      (node (ref "C71") (pin "1") (pinfunction "1_1") (pintype "passive"))
      (node (ref "C72") (pin "2") (pinfunction "2_2") (pintype "passive"))
      (node (ref "C74") (pin "1") (pinfunction "1_1") (pintype "passive"))
      (node (ref "C76") (pin "2") (pinfunction "2_2") (pintype "passive"))
      (node (ref "C77") (pin "1") (pinfunction "1_1") (pintype "passive"))
      (node (ref "C78") (pin "2") (pinfunction "2_2") (pintype "passive"))
      (node (ref "C79") (pin "1") (pinfunction "1_1") (pintype "passive"))
      (node (ref "C8") (pin "2") (pinfunction "2_2") (pintype "passive"))
      (node (ref "C80") (pin "2") (pinfunction "2_2") (pintype "passive"))
      (node (ref "C81") (pin "1") (pinfunction "1_1") (pintype "passive"))
      (node (ref "C84") (pin "2") (pinfunction "2_2") (pintype "passive"))
      (node (ref "C85") (pin "1") (pinfunction "1_1") (pintype "passive"))
      (node (ref "C86") (pin "2") (pinfunction "2_2") (pintype "passive"))
      (node (ref "C88") (pin "1") (pinfunction "1_1") (pintype "passive"))
      (node (ref "C9") (pin "2") (pinfunction "2_2") (pintype "passive"))
      (node (ref "C90") (pin "2") (pinfunction "2_2") (pintype "passive"))
      (node (ref "C91") (pin "1") (pinfunction "1_1") (pintype "passive"))
      (node (ref "C92") (pin "2") (pinfunction "2_2") (pintype "passive"))
      (node (ref "C93") (pin "1") (pinfunction "1_1") (pintype "passive"))
      (node (ref "C94") (pin "2") (pinfunction "2_2") (pintype "passive"))
      (node (ref "C95") (pin "1") (pinfunction "1_1") (pintype "passive"))
      (node (ref "C98") (pin "2") (pinfunction "2_2") (pintype "passive"))
      (node (ref "C99") (pin "1") (pinfunction "1_1") (pintype "passive"))
      (node (ref "COM") (pin "1") (pinfunction "1_1") (pintype "passive"))
      (node (ref "COM") (pin "2") (pinfunction "2_2") (pintype "passive"))
      (node (ref "G1") (pin "6") (pinfunction "COM_6") (pintype "bidirectional"))
      (node (ref "IC1") (pin "6") (pinfunction "REF_6") (pintype "bidirectional"))
      (node (ref "IC10") (pin "2") (pinfunction "-VS_2") (pintype "power_in"))
      (node (ref "IC11") (pin "6") (pinfunction "REF_6") (pintype "bidirectional"))
      (node (ref "IC13") (pin "2") (pinfunction "-VS_2") (pintype "power_in"))
      (node (ref "IC14") (pin "6") (pinfunction "REF_6") (pintype "bidirectional"))
      (node (ref "IC16") (pin "2") (pinfunction "-VS_2") (pintype "power_in"))
      (node (ref "IC17") (pin "6") (pinfunction "REF_6") (pintype "bidirectional"))
      (node (ref "IC19") (pin "2") (pinfunction "-VS_2") (pintype "power_in"))
      (node (ref "IC20") (pin "6") (pinfunction "REF_6") (pintype "bidirectional"))
      (node (ref "IC22") (pin "2") (pinfunction "-VS_2") (pintype "power_in"))
      (node (ref "IC23") (pin "6") (pinfunction "REF_6") (pintype "bidirectional"))
      (node (ref "IC25") (pin "2") (pinfunction "-VS_2") (pintype "power_in"))
      (node (ref "IC26") (pin "6") (pinfunction "REF_6") (pintype "bidirectional"))
      (node (ref "IC28") (pin "2") (pinfunction "-VS_2") (pintype "power_in"))
      (node (ref "IC3") (pin "17") (pinfunction "DGND_17") (pintype "bidirectional"))
      (node (ref "IC3") (pin "2") (pinfunction "AGND_2") (pintype "bidirectional"))
      (node (ref "IC3") (pin "20") (pinfunction "CS_20") (pintype "bidirectional"))
      (node (ref "IC3") (pin "3") (pinfunction "VREFN_3") (pintype "bidirectional"))
      (node (ref "IC4") (pin "2") (pinfunction "-VS_2") (pintype "power_in"))
      (node (ref "IC5") (pin "1") (pinfunction "GND_1") (pintype "passive"))
      (node (ref "IC6") (pin "2") (pinfunction "GND1_2") (pintype "bidirectional"))
      (node (ref "IC6") (pin "8") (pinfunction "GND1__8") (pintype "bidirectional"))
      (node (ref "IC7") (pin "3") (pinfunction "GND_3") (pintype "bidirectional"))
      (node (ref "IC8") (pin "6") (pinfunction "REF_6") (pintype "bidirectional"))
      (node (ref "R10") (pin "1") (pinfunction "1_1") (pintype "passive"))
      (node (ref "R102") (pin "2") (pinfunction "2_2") (pintype "passive"))
      (node (ref "R112") (pin "2") (pinfunction "2_2") (pintype "passive"))
      (node (ref "R113") (pin "2") (pinfunction "2_2") (pintype "passive"))
      (node (ref "R114") (pin "1") (pinfunction "1_1") (pintype "passive"))
      (node (ref "R117") (pin "2") (pinfunction "2_2") (pintype "passive"))
      (node (ref "R122") (pin "2") (pinfunction "2_2") (pintype "passive"))
      (node (ref "R13") (pin "2") (pinfunction "2_2") (pintype "passive"))
      (node (ref "R132") (pin "2") (pinfunction "2_2") (pintype "passive"))
      (node (ref "R133") (pin "2") (pinfunction "2_2") (pintype "passive"))
      (node (ref "R134") (pin "1") (pinfunction "1_1") (pintype "passive"))
      (node (ref "R137") (pin "2") (pinfunction "2_2") (pintype "passive"))
      (node (ref "R142") (pin "2") (pinfunction "2_2") (pintype "passive"))
      (node (ref "R152") (pin "2") (pinfunction "2_2") (pintype "passive"))
      (node (ref "R153") (pin "2") (pinfunction "2_2") (pintype "passive"))
      (node (ref "R154") (pin "1") (pinfunction "1_1") (pintype "passive"))
      (node (ref "R157") (pin "2") (pinfunction "2_2") (pintype "passive"))
      (node (ref "R162") (pin "2") (pinfunction "2_2") (pintype "passive"))
      (node (ref "R21") (pin "2") (pinfunction "2_2") (pintype "passive"))
      (node (ref "R32") (pin "2") (pinfunction "2_2") (pintype "passive"))
      (node (ref "R33") (pin "2") (pinfunction "2_2") (pintype "passive"))
      (node (ref "R34") (pin "1") (pinfunction "1_1") (pintype "passive"))
      (node (ref "R37") (pin "2") (pinfunction "2_2") (pintype "passive"))
      (node (ref "R42") (pin "2") (pinfunction "2_2") (pintype "passive"))
      (node (ref "R52") (pin "2") (pinfunction "2_2") (pintype "passive"))
      (node (ref "R53") (pin "2") (pinfunction "2_2") (pintype "passive"))
      (node (ref "R54") (pin "1") (pinfunction "1_1") (pintype "passive"))
      (node (ref "R57") (pin "2") (pinfunction "2_2") (pintype "passive"))
      (node (ref "R62") (pin "2") (pinfunction "2_2") (pintype "passive"))
      (node (ref "R72") (pin "2") (pinfunction "2_2") (pintype "passive"))
      (node (ref "R73") (pin "2") (pinfunction "2_2") (pintype "passive"))
      (node (ref "R74") (pin "1") (pinfunction "1_1") (pintype "passive"))
      (node (ref "R77") (pin "2") (pinfunction "2_2") (pintype "passive"))
      (node (ref "R8") (pin "2") (pinfunction "2_2") (pintype "passive"))
      (node (ref "R82") (pin "2") (pinfunction "2_2") (pintype "passive"))
      (node (ref "R9") (pin "2") (pinfunction "2_2") (pintype "passive"))
      (node (ref "R92") (pin "2") (pinfunction "2_2") (pintype "passive"))
      (node (ref "R93") (pin "2") (pinfunction "2_2") (pintype "passive"))
      (node (ref "R94") (pin "1") (pinfunction "1_1") (pintype "passive"))
      (node (ref "R97") (pin "2") (pinfunction "2_2") (pintype "passive"))
    )
    (net (code "5") (name "Net-(C12-Pad2)") (class "Default")
      (node (ref "C12") (pin "2") (pinfunction "2_2") (pintype "passive"))
      (node (ref "C13") (pin "1") (pinfunction "1_1") (pintype "passive"))
      (node (ref "R12") (pin "1") (pinfunction "1_1") (pintype "passive"))
    )
    (net (code "6") (name "Net-(C37-Pad2)") (class "Default")
      (node (ref "C37") (pin "2") (pinfunction "2_2") (pintype "passive"))
      (node (ref "C38") (pin "1") (pinfunction "1_1") (pintype "passive"))
      (node (ref "R36") (pin "1") (pinfunction "1_1") (pintype "passive"))
    )
    (net (code "7") (name "Net-(C42-Pad1)") (class "Default")
      (node (ref "C42") (pin "1") (pinfunction "1_1") (pintype "passive"))
      (node (ref "R38") (pin "1") (pinfunction "1_1") (pintype "passive"))
      (node (ref "R41") (pin "2") (pinfunction "2_2") (pintype "passive"))
    )
    (net (code "8") (name "Net-(C53-Pad2)") (class "Default")
      (node (ref "C53") (pin "2") (pinfunction "2_2") (pintype "passive"))
      (node (ref "C54") (pin "1") (pinfunction "1_1") (pintype "passive"))
      (node (ref "R56") (pin "1") (pinfunction "1_1") (pintype "passive"))
    )
    (net (code "9") (name "Net-(C56-Pad1)") (class "Default")
      (node (ref "C56") (pin "1") (pinfunction "1_1") (pintype "passive"))
      (node (ref "R19") (pin "2") (pinfunction "2_2") (pintype "passive"))
      (node (ref "R20") (pin "1") (pinfunction "1_1") (pintype "passive"))
    )
    (net (code "10") (name "Net-(C59-Pad1)") (class "Default")
      (node (ref "C59") (pin "1") (pinfunction "1_1") (pintype "passive"))
      (node (ref "R58") (pin "1") (pinfunction "1_1") (pintype "passive"))
      (node (ref "R61") (pin "2") (pinfunction "2_2") (pintype "passive"))
    )
    (net (code "11") (name "Net-(C68-Pad2)") (class "Default")
      (node (ref "C68") (pin "2") (pinfunction "2_2") (pintype "passive"))
      (node (ref "C69") (pin "1") (pinfunction "1_1") (pintype "passive"))
      (node (ref "R76") (pin "1") (pinfunction "1_1") (pintype "passive"))
    )
    (net (code "12") (name "Net-(C73-Pad1)") (class "Default")
      (node (ref "C73") (pin "1") (pinfunction "1_1") (pintype "passive"))
      (node (ref "R78") (pin "1") (pinfunction "1_1") (pintype "passive"))
      (node (ref "R81") (pin "2") (pinfunction "2_2") (pintype "passive"))
    )
    (net (code "13") (name "Net-(C82-Pad2)") (class "Default")
      (node (ref "C82") (pin "2") (pinfunction "2_2") (pintype "passive"))
      (node (ref "C83") (pin "1") (pinfunction "1_1") (pintype "passive"))
      (node (ref "R96") (pin "1") (pinfunction "1_1") (pintype "passive"))
    )
    (net (code "14") (name "Net-(C87-Pad1)") (class "Default")
      (node (ref "C87") (pin "1") (pinfunction "1_1") (pintype "passive"))
      (node (ref "R101") (pin "2") (pinfunction "2_2") (pintype "passive"))
      (node (ref "R98") (pin "1") (pinfunction "1_1") (pintype "passive"))
    )
    (net (code "15") (name "Net-(C96-Pad2)") (class "Default")
      (node (ref "C96") (pin "2") (pinfunction "2_2") (pintype "passive"))
      (node (ref "C97") (pin "1") (pinfunction "1_1") (pintype "passive"))
      (node (ref "R116") (pin "1") (pinfunction "1_1") (pintype "passive"))
    )
    (net (code "16") (name "Net-(C101-Pad1)") (class "Default")
      (node (ref "C101") (pin "1") (pinfunction "1_1") (pintype "passive"))
      (node (ref "R118") (pin "1") (pinfunction "1_1") (pintype "passive"))
      (node (ref "R121") (pin "2") (pinfunction "2_2") (pintype "passive"))
    )
    (net (code "17") (name "Net-(C110-Pad2)") (class "Default")
      (node (ref "C110") (pin "2") (pinfunction "2_2") (pintype "passive"))
      (node (ref "C111") (pin "1") (pinfunction "1_1") (pintype "passive"))
      (node (ref "R136") (pin "1") (pinfunction "1_1") (pintype "passive"))
    )
    (net (code "18") (name "Net-(C115-Pad1)") (class "Default")
      (node (ref "C115") (pin "1") (pinfunction "1_1") (pintype "passive"))
      (node (ref "R138") (pin "1") (pinfunction "1_1") (pintype "passive"))
      (node (ref "R141") (pin "2") (pinfunction "2_2") (pintype "passive"))
    )
    (net (code "19") (name "Net-(C124-Pad2)") (class "Default")
      (node (ref "C124") (pin "2") (pinfunction "2_2") (pintype "passive"))
      (node (ref "C125") (pin "1") (pinfunction "1_1") (pintype "passive"))
      (node (ref "R156") (pin "1") (pinfunction "1_1") (pintype "passive"))
    )
    (net (code "20") (name "Net-(C129-Pad1)") (class "Default")
      (node (ref "C129") (pin "1") (pinfunction "1_1") (pintype "passive"))
      (node (ref "R158") (pin "1") (pinfunction "1_1") (pintype "passive"))
      (node (ref "R161") (pin "2") (pinfunction "2_2") (pintype "passive"))
    )
    (net (code "21") (name "Net-(D1-AC)") (class "Default")
      (node (ref "C1") (pin "1") (pinfunction "1_1") (pintype "passive"))
      (node (ref "C2") (pin "1") (pinfunction "1_1") (pintype "passive"))
      (node (ref "D1") (pin "3") (pinfunction "AC_3") (pintype "passive"))
      (node (ref "R1") (pin "2") (pinfunction "2_2") (pintype "passive"))
      (node (ref "R5") (pin "1") (pinfunction "1_1") (pintype "passive"))
    )
    (net (code "22") (name "Net-(D2-AC)") (class "Default")
      (node (ref "C1") (pin "2") (pinfunction "2_2") (pintype "passive"))
      (node (ref "C3") (pin "2") (pinfunction "2_2") (pintype "passive"))
      (node (ref "D2") (pin "3") (pinfunction "AC_3") (pintype "passive"))
      (node (ref "R2") (pin "2") (pinfunction "2_2") (pintype "passive"))
      (node (ref "R6") (pin "1") (pinfunction "1_1") (pintype "passive"))
    )
    (net (code "23") (name "Net-(D3-AC)") (class "Default")
      (node (ref "D3") (pin "3") (pinfunction "AC_3") (pintype "passive"))
      (node (ref "IC2") (pin "8") (pinfunction "OUT3_8") (pintype "bidirectional"))
      (node (ref "IC2") (pin "9") (pinfunction "-IN3_9") (pintype "bidirectional"))
      (node (ref "R3") (pin "2") (pinfunction "2_2") (pintype "passive"))
      (node (ref "R8") (pin "1") (pinfunction "1_1") (pintype "passive"))
    )
    (net (code "24") (name "Net-(D4-AC)") (class "Default")
      (node (ref "D4") (pin "3") (pinfunction "AC_3") (pintype "passive"))
      (node (ref "IC2") (pin "13") (pinfunction "-IN4_13") (pintype "bidirectional"))
      (node (ref "IC2") (pin "14") (pinfunction "OUT4_14") (pintype "bidirectional"))
      (node (ref "R4") (pin "2") (pinfunction "2_2") (pintype "passive"))
      (node (ref "R9") (pin "1") (pinfunction "1_1") (pintype "passive"))
    )
    (net (code "25") (name "Net-(D5-AC)") (class "Default")
      (node (ref "C30") (pin "1") (pinfunction "1_1") (pintype "passive"))
      (node (ref "C31") (pin "1") (pinfunction "1_1") (pintype "passive"))
      (node (ref "D5") (pin "3") (pinfunction "AC_3") (pintype "passive"))
      (node (ref "R24") (pin "2") (pinfunction "2_2") (pintype "passive"))
      (node (ref "R29") (pin "1") (pinfunction "1_1") (pintype "passive"))
    )
    (net (code "26") (name "Net-(D6-AC)") (class "Default")
      (node (ref "C30") (pin "2") (pinfunction "2_2") (pintype "passive"))
      (node (ref "C32") (pin "2") (pinfunction "2_2") (pintype "passive"))
      (node (ref "D6") (pin "3") (pinfunction "AC_3") (pintype "passive"))
      (node (ref "R26") (pin "2") (pinfunction "2_2") (pintype "passive"))
      (node (ref "R30") (pin "1") (pinfunction "1_1") (pintype "passive"))
    )
    (net (code "27") (name "Net-(D7-AC)") (class "Default")
      (node (ref "D7") (pin "3") (pinfunction "AC_3") (pintype "passive"))
      (node (ref "IC9") (pin "8") (pinfunction "OUT3_8") (pintype "bidirectional"))
      (node (ref "IC9") (pin "9") (pinfunction "-IN3_9") (pintype "bidirectional"))
      (node (ref "R27") (pin "2") (pinfunction "2_2") (pintype "passive"))
      (node (ref "R32") (pin "1") (pinfunction "1_1") (pintype "passive"))
    )
    (net (code "28") (name "Net-(D8-AC)") (class "Default")
      (node (ref "D8") (pin "3") (pinfunction "AC_3") (pintype "passive"))
      (node (ref "IC9") (pin "13") (pinfunction "-IN4_13") (pintype "bidirectional"))
      (node (ref "IC9") (pin "14") (pinfunction "OUT4_14") (pintype "bidirectional"))
      (node (ref "R28") (pin "2") (pinfunction "2_2") (pintype "passive"))
      (node (ref "R33") (pin "1") (pinfunction "1_1") (pintype "passive"))
    )
    (net (code "29") (name "Net-(D9-AC)") (class "Default")
      (node (ref "C45") (pin "1") (pinfunction "1_1") (pintype "passive"))
      (node (ref "C46") (pin "1") (pinfunction "1_1") (pintype "passive"))
      (node (ref "D9") (pin "3") (pinfunction "AC_3") (pintype "passive"))
      (node (ref "R45") (pin "2") (pinfunction "2_2") (pintype "passive"))
      (node (ref "R49") (pin "1") (pinfunction "1_1") (pintype "passive"))
    )
    (net (code "30") (name "Net-(D10-AC)") (class "Default")
      (node (ref "C45") (pin "2") (pinfunction "2_2") (pintype "passive"))
      (node (ref "C47") (pin "2") (pinfunction "2_2") (pintype "passive"))
      (node (ref "D10") (pin "3") (pinfunction "AC_3") (pintype "passive"))
      (node (ref "R46") (pin "2") (pinfunction "2_2") (pintype "passive"))
      (node (ref "R50") (pin "1") (pinfunction "1_1") (pintype "passive"))
    )
    (net (code "31") (name "Net-(D11-AC)") (class "Default")
      (node (ref "D11") (pin "3") (pinfunction "AC_3") (pintype "passive"))
      (node (ref "IC12") (pin "8") (pinfunction "OUT3_8") (pintype "bidirectional"))
      (node (ref "IC12") (pin "9") (pinfunction "-IN3_9") (pintype "bidirectional"))
      (node (ref "R47") (pin "2") (pinfunction "2_2") (pintype "passive"))
      (node (ref "R52") (pin "1") (pinfunction "1_1") (pintype "passive"))
    )
    (net (code "32") (name "Net-(D12-AC)") (class "Default")
      (node (ref "D12") (pin "3") (pinfunction "AC_3") (pintype "passive"))
      (node (ref "IC12") (pin "13") (pinfunction "-IN4_13") (pintype "bidirectional"))
      (node (ref "IC12") (pin "14") (pinfunction "OUT4_14") (pintype "bidirectional"))
      (node (ref "R48") (pin "2") (pinfunction "2_2") (pintype "passive"))
      (node (ref "R53") (pin "1") (pinfunction "1_1") (pintype "passive"))
    )
    (net (code "33") (name "Net-(D13-AC)") (class "Default")
      (node (ref "C61") (pin "1") (pinfunction "1_1") (pintype "passive"))
      (node (ref "C62") (pin "1") (pinfunction "1_1") (pintype "passive"))
      (node (ref "D13") (pin "3") (pinfunction "AC_3") (pintype "passive"))
      (node (ref "R65") (pin "2") (pinfunction "2_2") (pintype "passive"))
      (node (ref "R69") (pin "1") (pinfunction "1_1") (pintype "passive"))
    )
    (net (code "34") (name "Net-(D14-AC)") (class "Default")
      (node (ref "C61") (pin "2") (pinfunction "2_2") (pintype "passive"))
      (node (ref "C63") (pin "2") (pinfunction "2_2") (pintype "passive"))
      (node (ref "D14") (pin "3") (pinfunction "AC_3") (pintype "passive"))
      (node (ref "R66") (pin "2") (pinfunction "2_2") (pintype "passive"))
      (node (ref "R70") (pin "1") (pinfunction "1_1") (pintype "passive"))
    )
    (net (code "35") (name "Net-(D15-AC)") (class "Default")
      (node (ref "D15") (pin "3") (pinfunction "AC_3") (pintype "passive"))
      (node (ref "IC15") (pin "8") (pinfunction "OUT3_8") (pintype "bidirectional"))
      (node (ref "IC15") (pin "9") (pinfunction "-IN3_9") (pintype "bidirectional"))
      (node (ref "R67") (pin "2") (pinfunction "2_2") (pintype "passive"))
      (node (ref "R72") (pin "1") (pinfunction "1_1") (pintype "passive"))
    )
    (net (code "36") (name "Net-(D16-AC)") (class "Default")
      (node (ref "D16") (pin "3") (pinfunction "AC_3") (pintype "passive"))
      (node (ref "IC15") (pin "13") (pinfunction "-IN4_13") (pintype "bidirectional"))
      (node (ref "IC15") (pin "14") (pinfunction "OUT4_14") (pintype "bidirectional"))
      (node (ref "R68") (pin "2") (pinfunction "2_2") (pintype "passive"))
      (node (ref "R73") (pin "1") (pinfunction "1_1") (pintype "passive"))
    )
    (net (code "37") (name "Net-(D17-AC)") (class "Default")
      (node (ref "C75") (pin "1") (pinfunction "1_1") (pintype "passive"))
      (node (ref "C76") (pin "1") (pinfunction "1_1") (pintype "passive"))
      (node (ref "D17") (pin "3") (pinfunction "AC_3") (pintype "passive"))
      (node (ref "R85") (pin "2") (pinfunction "2_2") (pintype "passive"))
      (node (ref "R89") (pin "1") (pinfunction "1_1") (pintype "passive"))
    )
    (net (code "38") (name "Net-(D18-AC)") (class "Default")
      (node (ref "C75") (pin "2") (pinfunction "2_2") (pintype "passive"))
      (node (ref "C77") (pin "2") (pinfunction "2_2") (pintype "passive"))
      (node (ref "D18") (pin "3") (pinfunction "AC_3") (pintype "passive"))
      (node (ref "R86") (pin "2") (pinfunction "2_2") (pintype "passive"))
      (node (ref "R90") (pin "1") (pinfunction "1_1") (pintype "passive"))
    )
    (net (code "39") (name "Net-(D19-AC)") (class "Default")
      (node (ref "D19") (pin "3") (pinfunction "AC_3") (pintype "passive"))
      (node (ref "IC18") (pin "8") (pinfunction "OUT3_8") (pintype "bidirectional"))
      (node (ref "IC18") (pin "9") (pinfunction "-IN3_9") (pintype "bidirectional"))
      (node (ref "R87") (pin "2") (pinfunction "2_2") (pintype "passive"))
      (node (ref "R92") (pin "1") (pinfunction "1_1") (pintype "passive"))
    )
    (net (code "40") (name "Net-(D20-AC)") (class "Default")
      (node (ref "D20") (pin "3") (pinfunction "AC_3") (pintype "passive"))
      (node (ref "IC18") (pin "13") (pinfunction "-IN4_13") (pintype "bidirectional"))
      (node (ref "IC18") (pin "14") (pinfunction "OUT4_14") (pintype "bidirectional"))
      (node (ref "R88") (pin "2") (pinfunction "2_2") (pintype "passive"))
      (node (ref "R93") (pin "1") (pinfunction "1_1") (pintype "passive"))
    )
    (net (code "41") (name "Net-(D21-AC)") (class "Default")
      (node (ref "C89") (pin "1") (pinfunction "1_1") (pintype "passive"))
      (node (ref "C90") (pin "1") (pinfunction "1_1") (pintype "passive"))
      (node (ref "D21") (pin "3") (pinfunction "AC_3") (pintype "passive"))
      (node (ref "R105") (pin "2") (pinfunction "2_2") (pintype "passive"))
      (node (ref "R109") (pin "1") (pinfunction "1_1") (pintype "passive"))
    )
    (net (code "42") (name "Net-(D22-AC)") (class "Default")
      (node (ref "C89") (pin "2") (pinfunction "2_2") (pintype "passive"))
      (node (ref "C91") (pin "2") (pinfunction "2_2") (pintype "passive"))
      (node (ref "D22") (pin "3") (pinfunction "AC_3") (pintype "passive"))
      (node (ref "R106") (pin "2") (pinfunction "2_2") (pintype "passive"))
      (node (ref "R110") (pin "1") (pinfunction "1_1") (pintype "passive"))
    )
    (net (code "43") (name "Net-(D23-AC)") (class "Default")
      (node (ref "D23") (pin "3") (pinfunction "AC_3") (pintype "passive"))
      (node (ref "IC21") (pin "8") (pinfunction "OUT3_8") (pintype "bidirectional"))
      (node (ref "IC21") (pin "9") (pinfunction "-IN3_9") (pintype "bidirectional"))
      (node (ref "R107") (pin "2") (pinfunction "2_2") (pintype "passive"))
      (node (ref "R112") (pin "1") (pinfunction "1_1") (pintype "passive"))
    )
    (net (code "44") (name "Net-(D24-AC)") (class "Default")
      (node (ref "D24") (pin "3") (pinfunction "AC_3") (pintype "passive"))
      (node (ref "IC21") (pin "13") (pinfunction "-IN4_13") (pintype "bidirectional"))
      (node (ref "IC21") (pin "14") (pinfunction "OUT4_14") (pintype "bidirectional"))
      (node (ref "R108") (pin "2") (pinfunction "2_2") (pintype "passive"))
      (node (ref "R113") (pin "1") (pinfunction "1_1") (pintype "passive"))
    )
    (net (code "45") (name "Net-(D25-AC)") (class "Default")
      (node (ref "C103") (pin "1") (pinfunction "1_1") (pintype "passive"))
      (node (ref "C104") (pin "1") (pinfunction "1_1") (pintype "passive"))
      (node (ref "D25") (pin "3") (pinfunction "AC_3") (pintype "passive"))
      (node (ref "R125") (pin "2") (pinfunction "2_2") (pintype "passive"))
      (node (ref "R129") (pin "1") (pinfunction "1_1") (pintype "passive"))
    )
    (net (code "46") (name "Net-(D26-AC)") (class "Default")
      (node (ref "C103") (pin "2") (pinfunction "2_2") (pintype "passive"))
      (node (ref "C105") (pin "2") (pinfunction "2_2") (pintype "passive"))
      (node (ref "D26") (pin "3") (pinfunction "AC_3") (pintype "passive"))
      (node (ref "R126") (pin "2") (pinfunction "2_2") (pintype "passive"))
      (node (ref "R130") (pin "1") (pinfunction "1_1") (pintype "passive"))
    )
    (net (code "47") (name "Net-(D27-AC)") (class "Default")
      (node (ref "D27") (pin "3") (pinfunction "AC_3") (pintype "passive"))
      (node (ref "IC24") (pin "8") (pinfunction "OUT3_8") (pintype "bidirectional"))
      (node (ref "IC24") (pin "9") (pinfunction "-IN3_9") (pintype "bidirectional"))
      (node (ref "R127") (pin "2") (pinfunction "2_2") (pintype "passive"))
      (node (ref "R132") (pin "1") (pinfunction "1_1") (pintype "passive"))
    )
    (net (code "48") (name "Net-(D28-AC)") (class "Default")
      (node (ref "D28") (pin "3") (pinfunction "AC_3") (pintype "passive"))
      (node (ref "IC24") (pin "13") (pinfunction "-IN4_13") (pintype "bidirectional"))
      (node (ref "IC24") (pin "14") (pinfunction "OUT4_14") (pintype "bidirectional"))
      (node (ref "R128") (pin "2") (pinfunction "2_2") (pintype "passive"))
      (node (ref "R133") (pin "1") (pinfunction "1_1") (pintype "passive"))
    )
    (net (code "49") (name "Net-(D29-AC)") (class "Default")
      (node (ref "C117") (pin "1") (pinfunction "1_1") (pintype "passive"))
      (node (ref "C118") (pin "1") (pinfunction "1_1") (pintype "passive"))
      (node (ref "D29") (pin "3") (pinfunction "AC_3") (pintype "passive"))
      (node (ref "R145") (pin "2") (pinfunction "2_2") (pintype "passive"))
      (node (ref "R149") (pin "1") (pinfunction "1_1") (pintype "passive"))
    )
    (net (code "50") (name "Net-(D30-AC)") (class "Default")
      (node (ref "C117") (pin "2") (pinfunction "2_2") (pintype "passive"))
      (node (ref "C119") (pin "2") (pinfunction "2_2") (pintype "passive"))
      (node (ref "D30") (pin "3") (pinfunction "AC_3") (pintype "passive"))
      (node (ref "R146") (pin "2") (pinfunction "2_2") (pintype "passive"))
      (node (ref "R150") (pin "1") (pinfunction "1_1") (pintype "passive"))
    )
    (net (code "51") (name "Net-(D31-AC)") (class "Default")
      (node (ref "D31") (pin "3") (pinfunction "AC_3") (pintype "passive"))
      (node (ref "IC27") (pin "8") (pinfunction "OUT3_8") (pintype "bidirectional"))
      (node (ref "IC27") (pin "9") (pinfunction "-IN3_9") (pintype "bidirectional"))
      (node (ref "R147") (pin "2") (pinfunction "2_2") (pintype "passive"))
      (node (ref "R152") (pin "1") (pinfunction "1_1") (pintype "passive"))
    )
    (net (code "52") (name "Net-(D32-AC)") (class "Default")
      (node (ref "D32") (pin "3") (pinfunction "AC_3") (pintype "passive"))
      (node (ref "IC27") (pin "13") (pinfunction "-IN4_13") (pintype "bidirectional"))
      (node (ref "IC27") (pin "14") (pinfunction "OUT4_14") (pintype "bidirectional"))
      (node (ref "R148") (pin "2") (pinfunction "2_2") (pintype "passive"))
      (node (ref "R153") (pin "1") (pinfunction "1_1") (pintype "passive"))
    )
    (net (code "53") (name "Net-(G1-+VIN)") (class "Default")
      (node (ref "G1") (pin "1") (pinfunction "+VIN_1") (pintype "bidirectional"))
      (node (ref "INT") (pin "1") (pinfunction "1_1") (pintype "passive"))
    )
    (net (code "54") (name "Net-(G1-+VOUT)") (class "Default")
      (node (ref "C22") (pin "+") (pinfunction "+_+") (pintype "passive"))
      (node (ref "C24") (pin "1") (pinfunction "1_1") (pintype "passive"))
      (node (ref "G1") (pin "7") (pinfunction "+VOUT_7") (pintype "bidirectional"))
      (node (ref "IC5") (pin "2@1") (pinfunction "VI1_2@1") (pintype "input"))
      (node (ref "L1") (pin "2") (pinfunction "2_2") (pintype "passive"))
    )
    (net (code "55") (name "Net-(G1--VIN)") (class "Default")
      (node (ref "G1") (pin "2") (pinfunction "-VIN_2") (pintype "bidirectional"))
      (node (ref "INT") (pin "2") (pinfunction "2_2") (pintype "passive"))
    )
    (net (code "56") (name "Net-(G1--VOUT)") (class "Default")
      (node (ref "C23") (pin "-") (pinfunction "-_-") (pintype "passive"))
      (node (ref "C25") (pin "2") (pinfunction "2_2") (pintype "passive"))
      (node (ref "G1") (pin "5") (pinfunction "-VOUT_5") (pintype "bidirectional"))
      (node (ref "L2") (pin "2") (pinfunction "2_2") (pintype "passive"))
    )
    (net (code "57") (name "Net-(IC1-+IN)") (class "Default")
      (node (ref "IC1") (pin "4") (pinfunction "+IN_4") (pintype "bidirectional"))
      (node (ref "R6") (pin "2") (pinfunction "2_2") (pintype "passive"))
    )
    (net (code "58") (name "Net-(IC1-+RG)") (class "Default")
      (node (ref "IC1") (pin "3") (pinfunction "+RG_3") (pintype "bidirectional"))
      (node (ref "IC2") (pin "12") (pinfunction "+IN4_12") (pintype "bidirectional"))
      (node (ref "R7") (pin "1") (pinfunction "1_1") (pintype "passive"))
    )
    (net (code "59") (name "Net-(IC1--IN)") (class "Default")
      (node (ref "IC1") (pin "1") (pinfunction "-IN_1") (pintype "bidirectional"))
      (node (ref "R5") (pin "2") (pinfunction "2_2") (pintype "passive"))
    )
    (net (code "60") (name "Net-(IC1--RG)") (class "Default")
      (node (ref "IC1") (pin "2") (pinfunction "-RG_2") (pintype "bidirectional"))
      (node (ref "IC2") (pin "10") (pinfunction "+IN3_10") (pintype "bidirectional"))
      (node (ref "R7") (pin "2") (pinfunction "2_2") (pintype "passive"))
    )
    (net (code "61") (name "Net-(IC1-OUT)") (class "Default")
      (node (ref "C12") (pin "1") (pinfunction "1_1") (pintype "passive"))
      (node (ref "IC1") (pin "7") (pinfunction "OUT_7") (pintype "bidirectional"))
    )
    (net (code "62") (name "Net-(IC2-+IN1)") (class "Default")
      (node (ref "C14") (pin "1") (pinfunction "1_1") (pintype "passive"))
      (node (ref "IC2") (pin "3") (pinfunction "+IN1_3") (pintype "bidirectional"))
      (node (ref "R19") (pin "1") (pinfunction "1_1") (pintype "passive"))
    )
    (net (code "63") (name "Net-(IC2-+IN2)") (class "Default")
      (node (ref "C13") (pin "2") (pinfunction "2_2") (pintype "passive"))
      (node (ref "IC2") (pin "5") (pinfunction "+IN2_5") (pintype "bidirectional"))
      (node (ref "R13") (pin "1") (pinfunction "1_1") (pintype "passive"))
    )
    (net (code "64") (name "Net-(IC2--IN1)") (class "Default")
      (node (ref "IC2") (pin "2") (pinfunction "-IN1_2") (pintype "bidirectional"))
      (node (ref "R21") (pin "1") (pinfunction "1_1") (pintype "passive"))
      (node (ref "R23") (pin "1") (pinfunction "1_1") (pintype "passive"))
    )
    (net (code "65") (name "Net-(IC2--IN2)") (class "Default")
      (node (ref "IC2") (pin "6") (pinfunction "-IN2_6") (pintype "bidirectional"))
      (node (ref "R10") (pin "2") (pinfunction "2_2") (pintype "passive"))
      (node (ref "R11") (pin "2") (pinfunction "2_2") (pintype "passive"))
    )
    (net (code "66") (name "Net-(IC2-OUT1)") (class "Default")
      (node (ref "C56") (pin "2") (pinfunction "2_2") (pintype "passive"))
      (node (ref "IC2") (pin "1") (pinfunction "OUT1_1") (pintype "bidirectional"))
      (node (ref "R22") (pin "2") (pinfunction "2_2") (pintype "passive"))
      (node (ref "R23") (pin "2") (pinfunction "2_2") (pintype "passive"))
    )
    (net (code "67") (name "Net-(IC2-OUT2)") (class "Default")
      (node (ref "IC2") (pin "7") (pinfunction "OUT2_7") (pintype "bidirectional"))
      (node (ref "R11") (pin "1") (pinfunction "1_1") (pintype "passive"))
      (node (ref "R12") (pin "2") (pinfunction "2_2") (pintype "passive"))
      (node (ref "R20") (pin "2") (pinfunction "2_2") (pintype "passive"))
    )
    (net (code "68") (name "Net-(IC3-AIN0)") (class "Default")
      (node (ref "C19") (pin "2") (pinfunction "2_2") (pintype "passive"))
      (node (ref "IC3") (pin "6") (pinfunction "AIN0_6") (pintype "bidirectional"))
      (node (ref "R18") (pin "1") (pinfunction "1_1") (pintype "passive"))
    )
    (net (code "69") (name "Net-(IC3-AIN1)") (class "Default")
      (node (ref "C43") (pin "2") (pinfunction "2_2") (pintype "passive"))
      (node (ref "IC3") (pin "7") (pinfunction "AIN1_7") (pintype "bidirectional"))
      (node (ref "R44") (pin "1") (pinfunction "1_1") (pintype "passive"))
    )
    (net (code "70") (name "Net-(IC3-AIN2)") (class "Default")
      (node (ref "C60") (pin "2") (pinfunction "2_2") (pintype "passive"))
      (node (ref "IC3") (pin "8") (pinfunction "AIN2_8") (pintype "bidirectional"))
      (node (ref "R64") (pin "1") (pinfunction "1_1") (pintype "passive"))
    )
    (net (code "71") (name "Net-(IC3-AIN3)") (class "Default")
      (node (ref "C74") (pin "2") (pinfunction "2_2") (pintype "passive"))
      (node (ref "IC3") (pin "9") (pinfunction "AIN3_9") (pintype "bidirectional"))
      (node (ref "R84") (pin "1") (pinfunction "1_1") (pintype "passive"))
    )
    (net (code "72") (name "Net-(IC3-AIN4)") (class "Default")
      (node (ref "C88") (pin "2") (pinfunction "2_2") (pintype "passive"))
      (node (ref "IC3") (pin "10") (pinfunction "AIN4_10") (pintype "bidirectional"))
      (node (ref "R104") (pin "1") (pinfunction "1_1") (pintype "passive"))
    )
    (net (code "73") (name "Net-(IC3-AIN5)") (class "Default")
      (node (ref "C102") (pin "2") (pinfunction "2_2") (pintype "passive"))
      (node (ref "IC3") (pin "11") (pinfunction "AIN5_11") (pintype "bidirectional"))
      (node (ref "R124") (pin "1") (pinfunction "1_1") (pintype "passive"))
    )
    (net (code "74") (name "Net-(IC3-AIN6)") (class "Default")
      (node (ref "C116") (pin "2") (pinfunction "2_2") (pintype "passive"))
      (node (ref "IC3") (pin "12") (pinfunction "AIN6_12") (pintype "bidirectional"))
      (node (ref "R144") (pin "1") (pinfunction "1_1") (pintype "passive"))
    )
    (net (code "75") (name "Net-(IC3-AIN7)") (class "Default")
      (node (ref "C130") (pin "2") (pinfunction "2_2") (pintype "passive"))
      (node (ref "IC3") (pin "13") (pinfunction "AIN7_13") (pintype "bidirectional"))
      (node (ref "R164") (pin "1") (pinfunction "1_1") (pintype "passive"))
    )
    (net (code "76") (name "Net-(IC3-DIN)") (class "Default")
      (node (ref "IC3") (pin "23") (pinfunction "DIN_23") (pintype "bidirectional"))
      (node (ref "R16") (pin "1") (pinfunction "1_1") (pintype "passive"))
    )
    (net (code "77") (name "Net-(IC3-DOUT)") (class "Default")
      (node (ref "IC3") (pin "22") (pinfunction "DOUT_22") (pintype "bidirectional"))
      (node (ref "R17") (pin "1") (pinfunction "1_1") (pintype "passive"))
    )
    (net (code "78") (name "Net-(IC3-DRDY)") (class "Default")
      (node (ref "IC3") (pin "21") (pinfunction "DRDY_21") (pintype "bidirectional"))
      (node (ref "R14") (pin "1") (pinfunction "1_1") (pintype "passive"))
    )
    (net (code "79") (name "Net-(IC3-SCLK)") (class "Default")
      (node (ref "IC3") (pin "24") (pinfunction "SCLK_24") (pintype "bidirectional"))
      (node (ref "R15") (pin "1") (pinfunction "1_1") (pintype "passive"))
    )
    (net (code "80") (name "Net-(IC3-XTAL1{slash}CLKIN)") (class "Default")
      (node (ref "C9") (pin "1") (pinfunction "1_1") (pintype "passive"))
      (node (ref "IC3") (pin "19") (pinfunction "XTAL1/CLKIN_19") (pintype "bidirectional"))
      (node (ref "Q1") (pin "2") (pinfunction "2_2") (pintype "passive"))
    )
    (net (code "81") (name "Net-(IC3-XTAL2)") (class "Default")
      (node (ref "C10") (pin "1") (pinfunction "1_1") (pintype "passive"))
      (node (ref "IC3") (pin "18") (pinfunction "XTAL2_18") (pintype "bidirectional"))
      (node (ref "Q1") (pin "1") (pinfunction "1_1") (pintype "passive"))
    )
    (net (code "82") (name "Net-(IC4--IN)") (class "Default")
      (node (ref "IC4") (pin "4") (pinfunction "-IN_4") (pintype "bidirectional"))
      (node (ref "R22") (pin "1") (pinfunction "1_1") (pintype "passive"))
      (node (ref "R25") (pin "1") (pinfunction "1_1") (pintype "passive"))
    )
    (net (code "83") (name "Net-(IC4-OUT)") (class "Default")
      (node (ref "IC4") (pin "1") (pinfunction "OUT_1") (pintype "bidirectional"))
      (node (ref "R18") (pin "2") (pinfunction "2_2") (pintype "passive"))
      (node (ref "R25") (pin "2") (pinfunction "2_2") (pintype "passive"))
    )
    (net (code "84") (name "Net-(IC6-GND2)") (class "Default")
      (node (ref "C18") (pin "2") (pinfunction "2_2") (pintype "passive"))
      (node (ref "IC6") (pin "15") (pinfunction "GND2_15") (pintype "bidirectional"))
      (node (ref "IC6") (pin "9") (pinfunction "GND2__9") (pintype "bidirectional"))
      (node (ref "INT") (pin "8") (pinfunction "8_8") (pintype "passive"))
    )
    (net (code "85") (name "Net-(IC6-VDD2)") (class "Default")
      (node (ref "C18") (pin "1") (pinfunction "1_1") (pintype "passive"))
      (node (ref "IC6") (pin "10") (pinfunction "VE2_10") (pintype "bidirectional"))
      (node (ref "IC6") (pin "16") (pinfunction "VDD2_16") (pintype "bidirectional"))
      (node (ref "INT") (pin "3") (pinfunction "3_3") (pintype "passive"))
    )
    (net (code "86") (name "Net-(IC6-VIA)") (class "Default")
      (node (ref "IC6") (pin "3") (pinfunction "VIA_3") (pintype "bidirectional"))
      (node (ref "R14") (pin "2") (pinfunction "2_2") (pintype "passive"))
    )
    (net (code "87") (name "Net-(IC6-VIB)") (class "Default")
      (node (ref "IC6") (pin "4") (pinfunction "VIB_4") (pintype "bidirectional"))
      (node (ref "R17") (pin "2") (pinfunction "2_2") (pintype "passive"))
    )
    (net (code "88") (name "Net-(IC6-VIC)") (class "Default")
      (node (ref "IC6") (pin "12") (pinfunction "VIC_12") (pintype "bidirectional"))
      (node (ref "INT") (pin "6") (pinfunction "6_6") (pintype "passive"))
    )
    (net (code "89") (name "Net-(IC6-VID)") (class "Default")
      (node (ref "IC6") (pin "11") (pinfunction "VID_11") (pintype "bidirectional"))
      (node (ref "INT") (pin "7") (pinfunction "7_7") (pintype "passive"))
    )
    (net (code "90") (name "Net-(IC6-VOA)") (class "Default")
      (node (ref "IC6") (pin "14") (pinfunction "VOA_14") (pintype "bidirectional"))
      (node (ref "INT") (pin "4") (pinfunction "4_4") (pintype "passive"))
    )
    (net (code "91") (name "Net-(IC6-VOB)") (class "Default")
      (node (ref "IC6") (pin "13") (pinfunction "VOB_13") (pintype "bidirectional"))
      (node (ref "INT") (pin "5") (pinfunction "5_5") (pintype "passive"))
    )
    (net (code "92") (name "Net-(IC6-VOC)") (class "Default")
      (node (ref "IC6") (pin "5") (pinfunction "VOC_5") (pintype "bidirectional"))
      (node (ref "R15") (pin "2") (pinfunction "2_2") (pintype "passive"))
    )
    (net (code "93") (name "Net-(IC6-VOD)") (class "Default")
      (node (ref "IC6") (pin "6") (pinfunction "VOD_6") (pintype "bidirectional"))
      (node (ref "R16") (pin "2") (pinfunction "2_2") (pintype "passive"))
    )
    (net (code "94") (name "Net-(IC8-+IN)") (class "Default")
      (node (ref "IC8") (pin "4") (pinfunction "+IN_4") (pintype "bidirectional"))
      (node (ref "R30") (pin "2") (pinfunction "2_2") (pintype "passive"))
    )
    (net (code "95") (name "Net-(IC8-+RG)") (class "Default")
      (node (ref "IC8") (pin "3") (pinfunction "+RG_3") (pintype "bidirectional"))
      (node (ref "IC9") (pin "12") (pinfunction "+IN4_12") (pintype "bidirectional"))
      (node (ref "R31") (pin "1") (pinfunction "1_1") (pintype "passive"))
    )
    (net (code "96") (name "Net-(IC8--IN)") (class "Default")
      (node (ref "IC8") (pin "1") (pinfunction "-IN_1") (pintype "bidirectional"))
      (node (ref "R29") (pin "2") (pinfunction "2_2") (pintype "passive"))
    )
    (net (code "97") (name "Net-(IC8--RG)") (class "Default")
      (node (ref "IC8") (pin "2") (pinfunction "-RG_2") (pintype "bidirectional"))
      (node (ref "IC9") (pin "10") (pinfunction "+IN3_10") (pintype "bidirectional"))
      (node (ref "R31") (pin "2") (pinfunction "2_2") (pintype "passive"))
    )
    (net (code "98") (name "Net-(IC8-OUT)") (class "Default")
      (node (ref "C37") (pin "1") (pinfunction "1_1") (pintype "passive"))
      (node (ref "IC8") (pin "7") (pinfunction "OUT_7") (pintype "bidirectional"))
    )
    (net (code "99") (name "Net-(IC9-+IN1)") (class "Default")
      (node (ref "C41") (pin "1") (pinfunction "1_1") (pintype "passive"))
      (node (ref "IC9") (pin "3") (pinfunction "+IN1_3") (pintype "bidirectional"))
      (node (ref "R41") (pin "1") (pinfunction "1_1") (pintype "passive"))
    )
    (net (code "100") (name "Net-(IC9-+IN2)") (class "Default")
      (node (ref "C38") (pin "2") (pinfunction "2_2") (pintype "passive"))
      (node (ref "IC9") (pin "5") (pinfunction "+IN2_5") (pintype "bidirectional"))
      (node (ref "R37") (pin "1") (pinfunction "1_1") (pintype "passive"))
    )
    (net (code "101") (name "Net-(IC9--IN1)") (class "Default")
      (node (ref "IC9") (pin "2") (pinfunction "-IN1_2") (pintype "bidirectional"))
      (node (ref "R42") (pin "1") (pinfunction "1_1") (pintype "passive"))
      (node (ref "R43") (pin "1") (pinfunction "1_1") (pintype "passive"))
    )
    (net (code "102") (name "Net-(IC9--IN2)") (class "Default")
      (node (ref "IC9") (pin "6") (pinfunction "-IN2_6") (pintype "bidirectional"))
      (node (ref "R34") (pin "2") (pinfunction "2_2") (pintype "passive"))
      (node (ref "R35") (pin "2") (pinfunction "2_2") (pintype "passive"))
    )
    (net (code "103") (name "Net-(IC9-OUT1)") (class "Default")
      (node (ref "C42") (pin "2") (pinfunction "2_2") (pintype "passive"))
      (node (ref "IC9") (pin "1") (pinfunction "OUT1_1") (pintype "bidirectional"))
      (node (ref "R39") (pin "2") (pinfunction "2_2") (pintype "passive"))
      (node (ref "R43") (pin "2") (pinfunction "2_2") (pintype "passive"))
    )
    (net (code "104") (name "Net-(IC9-OUT2)") (class "Default")
      (node (ref "IC9") (pin "7") (pinfunction "OUT2_7") (pintype "bidirectional"))
      (node (ref "R35") (pin "1") (pinfunction "1_1") (pintype "passive"))
      (node (ref "R36") (pin "2") (pinfunction "2_2") (pintype "passive"))
      (node (ref "R38") (pin "2") (pinfunction "2_2") (pintype "passive"))
    )
    (net (code "105") (name "Net-(IC10--IN)") (class "Default")
      (node (ref "IC10") (pin "4") (pinfunction "-IN_4") (pintype "bidirectional"))
      (node (ref "R39") (pin "1") (pinfunction "1_1") (pintype "passive"))
      (node (ref "R40") (pin "1") (pinfunction "1_1") (pintype "passive"))
    )
    (net (code "106") (name "Net-(IC10-OUT)") (class "Default")
      (node (ref "IC10") (pin "1") (pinfunction "OUT_1") (pintype "bidirectional"))
      (node (ref "R40") (pin "2") (pinfunction "2_2") (pintype "passive"))
      (node (ref "R44") (pin "2") (pinfunction "2_2") (pintype "passive"))
    )
    (net (code "107") (name "Net-(IC11-+IN)") (class "Default")
      (node (ref "IC11") (pin "4") (pinfunction "+IN_4") (pintype "bidirectional"))
      (node (ref "R50") (pin "2") (pinfunction "2_2") (pintype "passive"))
    )
    (net (code "108") (name "Net-(IC11-+RG)") (class "Default")
      (node (ref "IC11") (pin "3") (pinfunction "+RG_3") (pintype "bidirectional"))
      (node (ref "IC12") (pin "12") (pinfunction "+IN4_12") (pintype "bidirectional"))
      (node (ref "R51") (pin "1") (pinfunction "1_1") (pintype "passive"))
    )
    (net (code "109") (name "Net-(IC11--IN)") (class "Default")
      (node (ref "IC11") (pin "1") (pinfunction "-IN_1") (pintype "bidirectional"))
      (node (ref "R49") (pin "2") (pinfunction "2_2") (pintype "passive"))
    )
    (net (code "110") (name "Net-(IC11--RG)") (class "Default")
      (node (ref "IC11") (pin "2") (pinfunction "-RG_2") (pintype "bidirectional"))
      (node (ref "IC12") (pin "10") (pinfunction "+IN3_10") (pintype "bidirectional"))
      (node (ref "R51") (pin "2") (pinfunction "2_2") (pintype "passive"))
    )
    (net (code "111") (name "Net-(IC11-OUT)") (class "Default")
      (node (ref "C53") (pin "1") (pinfunction "1_1") (pintype "passive"))
      (node (ref "IC11") (pin "7") (pinfunction "OUT_7") (pintype "bidirectional"))
    )
    (net (code "112") (name "Net-(IC12-+IN1)") (class "Default")
      (node (ref "C58") (pin "1") (pinfunction "1_1") (pintype "passive"))
      (node (ref "IC12") (pin "3") (pinfunction "+IN1_3") (pintype "bidirectional"))
      (node (ref "R61") (pin "1") (pinfunction "1_1") (pintype "passive"))
    )
    (net (code "113") (name "Net-(IC12-+IN2)") (class "Default")
      (node (ref "C54") (pin "2") (pinfunction "2_2") (pintype "passive"))
      (node (ref "IC12") (pin "5") (pinfunction "+IN2_5") (pintype "bidirectional"))
      (node (ref "R57") (pin "1") (pinfunction "1_1") (pintype "passive"))
    )
    (net (code "114") (name "Net-(IC12--IN1)") (class "Default")
      (node (ref "IC12") (pin "2") (pinfunction "-IN1_2") (pintype "bidirectional"))
      (node (ref "R62") (pin "1") (pinfunction "1_1") (pintype "passive"))
      (node (ref "R63") (pin "1") (pinfunction "1_1") (pintype "passive"))
    )
    (net (code "115") (name "Net-(IC12--IN2)") (class "Default")
      (node (ref "IC12") (pin "6") (pinfunction "-IN2_6") (pintype "bidirectional"))
      (node (ref "R54") (pin "2") (pinfunction "2_2") (pintype "passive"))
      (node (ref "R55") (pin "2") (pinfunction "2_2") (pintype "passive"))
    )
    (net (code "116") (name "Net-(IC12-OUT1)") (class "Default")
      (node (ref "C59") (pin "2") (pinfunction "2_2") (pintype "passive"))
      (node (ref "IC12") (pin "1") (pinfunction "OUT1_1") (pintype "bidirectional"))
      (node (ref "R59") (pin "2") (pinfunction "2_2") (pintype "passive"))
      (node (ref "R63") (pin "2") (pinfunction "2_2") (pintype "passive"))
    )
    (net (code "117") (name "Net-(IC12-OUT2)") (class "Default")
      (node (ref "IC12") (pin "7") (pinfunction "OUT2_7") (pintype "bidirectional"))
      (node (ref "R55") (pin "1") (pinfunction "1_1") (pintype "passive"))
      (node (ref "R56") (pin "2") (pinfunction "2_2") (pintype "passive"))
      (node (ref "R58") (pin "2") (pinfunction "2_2") (pintype "passive"))
    )
    (net (code "118") (name "Net-(IC13--IN)") (class "Default")
      (node (ref "IC13") (pin "4") (pinfunction "-IN_4") (pintype "bidirectional"))
      (node (ref "R59") (pin "1") (pinfunction "1_1") (pintype "passive"))
      (node (ref "R60") (pin "1") (pinfunction "1_1") (pintype "passive"))
    )
    (net (code "119") (name "Net-(IC13-OUT)") (class "Default")
      (node (ref "IC13") (pin "1") (pinfunction "OUT_1") (pintype "bidirectional"))
      (node (ref "R60") (pin "2") (pinfunction "2_2") (pintype "passive"))
      (node (ref "R64") (pin "2") (pinfunction "2_2") (pintype "passive"))
    )
    (net (code "120") (name "Net-(IC14-+IN)") (class "Default")
      (node (ref "IC14") (pin "4") (pinfunction "+IN_4") (pintype "bidirectional"))
      (node (ref "R70") (pin "2") (pinfunction "2_2") (pintype "passive"))
    )
    (net (code "121") (name "Net-(IC14-+RG)") (class "Default")
      (node (ref "IC14") (pin "3") (pinfunction "+RG_3") (pintype "bidirectional"))
      (node (ref "IC15") (pin "12") (pinfunction "+IN4_12") (pintype "bidirectional"))
      (node (ref "R71") (pin "1") (pinfunction "1_1") (pintype "passive"))
    )
    (net (code "122") (name "Net-(IC14--IN)") (class "Default")
      (node (ref "IC14") (pin "1") (pinfunction "-IN_1") (pintype "bidirectional"))
      (node (ref "R69") (pin "2") (pinfunction "2_2") (pintype "passive"))
    )
    (net (code "123") (name "Net-(IC14--RG)") (class "Default")
      (node (ref "IC14") (pin "2") (pinfunction "-RG_2") (pintype "bidirectional"))
      (node (ref "IC15") (pin "10") (pinfunction "+IN3_10") (pintype "bidirectional"))
      (node (ref "R71") (pin "2") (pinfunction "2_2") (pintype "passive"))
    )
    (net (code "124") (name "Net-(IC14-OUT)") (class "Default")
      (node (ref "C68") (pin "1") (pinfunction "1_1") (pintype "passive"))
      (node (ref "IC14") (pin "7") (pinfunction "OUT_7") (pintype "bidirectional"))
    )
    (net (code "125") (name "Net-(IC15-+IN1)") (class "Default")
      (node (ref "C72") (pin "1") (pinfunction "1_1") (pintype "passive"))
      (node (ref "IC15") (pin "3") (pinfunction "+IN1_3") (pintype "bidirectional"))
      (node (ref "R81") (pin "1") (pinfunction "1_1") (pintype "passive"))
    )
    (net (code "126") (name "Net-(IC15-+IN2)") (class "Default")
      (node (ref "C69") (pin "2") (pinfunction "2_2") (pintype "passive"))
      (node (ref "IC15") (pin "5") (pinfunction "+IN2_5") (pintype "bidirectional"))
      (node (ref "R77") (pin "1") (pinfunction "1_1") (pintype "passive"))
    )
    (net (code "127") (name "Net-(IC15--IN1)") (class "Default")
      (node (ref "IC15") (pin "2") (pinfunction "-IN1_2") (pintype "bidirectional"))
      (node (ref "R82") (pin "1") (pinfunction "1_1") (pintype "passive"))
      (node (ref "R83") (pin "1") (pinfunction "1_1") (pintype "passive"))
    )
    (net (code "128") (name "Net-(IC15--IN2)") (class "Default")
      (node (ref "IC15") (pin "6") (pinfunction "-IN2_6") (pintype "bidirectional"))
      (node (ref "R74") (pin "2") (pinfunction "2_2") (pintype "passive"))
      (node (ref "R75") (pin "2") (pinfunction "2_2") (pintype "passive"))
    )
    (net (code "129") (name "Net-(IC15-OUT1)") (class "Default")
      (node (ref "C73") (pin "2") (pinfunction "2_2") (pintype "passive"))
      (node (ref "IC15") (pin "1") (pinfunction "OUT1_1") (pintype "bidirectional"))
      (node (ref "R79") (pin "2") (pinfunction "2_2") (pintype "passive"))
      (node (ref "R83") (pin "2") (pinfunction "2_2") (pintype "passive"))
    )
    (net (code "130") (name "Net-(IC15-OUT2)") (class "Default")
      (node (ref "IC15") (pin "7") (pinfunction "OUT2_7") (pintype "bidirectional"))
      (node (ref "R75") (pin "1") (pinfunction "1_1") (pintype "passive"))
      (node (ref "R76") (pin "2") (pinfunction "2_2") (pintype "passive"))
      (node (ref "R78") (pin "2") (pinfunction "2_2") (pintype "passive"))
    )
    (net (code "131") (name "Net-(IC16--IN)") (class "Default")
      (node (ref "IC16") (pin "4") (pinfunction "-IN_4") (pintype "bidirectional"))
      (node (ref "R79") (pin "1") (pinfunction "1_1") (pintype "passive"))
      (node (ref "R80") (pin "1") (pinfunction "1_1") (pintype "passive"))
    )
    (net (code "132") (name "Net-(IC16-OUT)") (class "Default")
      (node (ref "IC16") (pin "1") (pinfunction "OUT_1") (pintype "bidirectional"))
      (node (ref "R80") (pin "2") (pinfunction "2_2") (pintype "passive"))
      (node (ref "R84") (pin "2") (pinfunction "2_2") (pintype "passive"))
    )
    (net (code "133") (name "Net-(IC17-+IN)") (class "Default")
      (node (ref "IC17") (pin "4") (pinfunction "+IN_4") (pintype "bidirectional"))
      (node (ref "R90") (pin "2") (pinfunction "2_2") (pintype "passive"))
    )
    (net (code "134") (name "Net-(IC17-+RG)") (class "Default")
      (node (ref "IC17") (pin "3") (pinfunction "+RG_3") (pintype "bidirectional"))
      (node (ref "IC18") (pin "12") (pinfunction "+IN4_12") (pintype "bidirectional"))
      (node (ref "R91") (pin "1") (pinfunction "1_1") (pintype "passive"))
    )
    (net (code "135") (name "Net-(IC17--IN)") (class "Default")
      (node (ref "IC17") (pin "1") (pinfunction "-IN_1") (pintype "bidirectional"))
      (node (ref "R89") (pin "2") (pinfunction "2_2") (pintype "passive"))
    )
    (net (code "136") (name "Net-(IC17--RG)") (class "Default")
      (node (ref "IC17") (pin "2") (pinfunction "-RG_2") (pintype "bidirectional"))
      (node (ref "IC18") (pin "10") (pinfunction "+IN3_10") (pintype "bidirectional"))
      (node (ref "R91") (pin "2") (pinfunction "2_2") (pintype "passive"))
    )
    (net (code "137") (name "Net-(IC17-OUT)") (class "Default")
      (node (ref "C82") (pin "1") (pinfunction "1_1") (pintype "passive"))
      (node (ref "IC17") (pin "7") (pinfunction "OUT_7") (pintype "bidirectional"))
    )
    (net (code "138") (name "Net-(IC18-+IN1)") (class "Default")
      (node (ref "C86") (pin "1") (pinfunction "1_1") (pintype "passive"))
      (node (ref "IC18") (pin "3") (pinfunction "+IN1_3") (pintype "bidirectional"))
      (node (ref "R101") (pin "1") (pinfunction "1_1") (pintype "passive"))
    )
    (net (code "139") (name "Net-(IC18-+IN2)") (class "Default")
      (node (ref "C83") (pin "2") (pinfunction "2_2") (pintype "passive"))
      (node (ref "IC18") (pin "5") (pinfunction "+IN2_5") (pintype "bidirectional"))
      (node (ref "R97") (pin "1") (pinfunction "1_1") (pintype "passive"))
    )
    (net (code "140") (name "Net-(IC18--IN1)") (class "Default")
      (node (ref "IC18") (pin "2") (pinfunction "-IN1_2") (pintype "bidirectional"))
      (node (ref "R102") (pin "1") (pinfunction "1_1") (pintype "passive"))
      (node (ref "R103") (pin "1") (pinfunction "1_1") (pintype "passive"))
    )
    (net (code "141") (name "Net-(IC18--IN2)") (class "Default")
      (node (ref "IC18") (pin "6") (pinfunction "-IN2_6") (pintype "bidirectional"))
      (node (ref "R94") (pin "2") (pinfunction "2_2") (pintype "passive"))
      (node (ref "R95") (pin "2") (pinfunction "2_2") (pintype "passive"))
    )
    (net (code "142") (name "Net-(IC18-OUT1)") (class "Default")
      (node (ref "C87") (pin "2") (pinfunction "2_2") (pintype "passive"))
      (node (ref "IC18") (pin "1") (pinfunction "OUT1_1") (pintype "bidirectional"))
      (node (ref "R103") (pin "2") (pinfunction "2_2") (pintype "passive"))
      (node (ref "R99") (pin "2") (pinfunction "2_2") (pintype "passive"))
    )
    (net (code "143") (name "Net-(IC18-OUT2)") (class "Default")
      (node (ref "IC18") (pin "7") (pinfunction "OUT2_7") (pintype "bidirectional"))
      (node (ref "R95") (pin "1") (pinfunction "1_1") (pintype "passive"))
      (node (ref "R96") (pin "2") (pinfunction "2_2") (pintype "passive"))
      (node (ref "R98") (pin "2") (pinfunction "2_2") (pintype "passive"))
    )
    (net (code "144") (name "Net-(IC19--IN)") (class "Default")
      (node (ref "IC19") (pin "4") (pinfunction "-IN_4") (pintype "bidirectional"))
      (node (ref "R100") (pin "1") (pinfunction "1_1") (pintype "passive"))
      (node (ref "R99") (pin "1") (pinfunction "1_1") (pintype "passive"))
    )
    (net (code "145") (name "Net-(IC19-OUT)") (class "Default")
      (node (ref "IC19") (pin "1") (pinfunction "OUT_1") (pintype "bidirectional"))
      (node (ref "R100") (pin "2") (pinfunction "2_2") (pintype "passive"))
      (node (ref "R104") (pin "2") (pinfunction "2_2") (pintype "passive"))
    )
    (net (code "146") (name "Net-(IC20-+IN)") (class "Default")
      (node (ref "IC20") (pin "4") (pinfunction "+IN_4") (pintype "bidirectional"))
      (node (ref "R110") (pin "2") (pinfunction "2_2") (pintype "passive"))
    )
    (net (code "147") (name "Net-(IC20-+RG)") (class "Default")
      (node (ref "IC20") (pin "3") (pinfunction "+RG_3") (pintype "bidirectional"))
      (node (ref "IC21") (pin "12") (pinfunction "+IN4_12") (pintype "bidirectional"))
      (node (ref "R111") (pin "1") (pinfunction "1_1") (pintype "passive"))
    )
    (net (code "148") (name "Net-(IC20--IN)") (class "Default")
      (node (ref "IC20") (pin "1") (pinfunction "-IN_1") (pintype "bidirectional"))
      (node (ref "R109") (pin "2") (pinfunction "2_2") (pintype "passive"))
    )
    (net (code "149") (name "Net-(IC20--RG)") (class "Default")
      (node (ref "IC20") (pin "2") (pinfunction "-RG_2") (pintype "bidirectional"))
      (node (ref "IC21") (pin "10") (pinfunction "+IN3_10") (pintype "bidirectional"))
      (node (ref "R111") (pin "2") (pinfunction "2_2") (pintype "passive"))
    )
    (net (code "150") (name "Net-(IC20-OUT)") (class "Default")
      (node (ref "C96") (pin "1") (pinfunction "1_1") (pintype "passive"))
      (node (ref "IC20") (pin "7") (pinfunction "OUT_7") (pintype "bidirectional"))
    )
    (net (code "151") (name "Net-(IC21-+IN1)") (class "Default")
      (node (ref "C100") (pin "1") (pinfunction "1_1") (pintype "passive"))
      (node (ref "IC21") (pin "3") (pinfunction "+IN1_3") (pintype "bidirectional"))
      (node (ref "R121") (pin "1") (pinfunction "1_1") (pintype "passive"))
    )
    (net (code "152") (name "Net-(IC21-+IN2)") (class "Default")
      (node (ref "C97") (pin "2") (pinfunction "2_2") (pintype "passive"))
      (node (ref "IC21") (pin "5") (pinfunction "+IN2_5") (pintype "bidirectional"))
      (node (ref "R117") (pin "1") (pinfunction "1_1") (pintype "passive"))
    )
    (net (code "153") (name "Net-(IC21--IN1)") (class "Default")
      (node (ref "IC21") (pin "2") (pinfunction "-IN1_2") (pintype "bidirectional"))
      (node (ref "R122") (pin "1") (pinfunction "1_1") (pintype "passive"))
      (node (ref "R123") (pin "1") (pinfunction "1_1") (pintype "passive"))
    )
    (net (code "154") (name "Net-(IC21--IN2)") (class "Default")
      (node (ref "IC21") (pin "6") (pinfunction "-IN2_6") (pintype "bidirectional"))
      (node (ref "R114") (pin "2") (pinfunction "2_2") (pintype "passive"))
      (node (ref "R115") (pin "2") (pinfunction "2_2") (pintype "passive"))
    )
    (net (code "155") (name "Net-(IC21-OUT1)") (class "Default")
      (node (ref "C101") (pin "2") (pinfunction "2_2") (pintype "passive"))
      (node (ref "IC21") (pin "1") (pinfunction "OUT1_1") (pintype "bidirectional"))
      (node (ref "R119") (pin "2") (pinfunction "2_2") (pintype "passive"))
      (node (ref "R123") (pin "2") (pinfunction "2_2") (pintype "passive"))
    )
    (net (code "156") (name "Net-(IC21-OUT2)") (class "Default")
      (node (ref "IC21") (pin "7") (pinfunction "OUT2_7") (pintype "bidirectional"))
      (node (ref "R115") (pin "1") (pinfunction "1_1") (pintype "passive"))
      (node (ref "R116") (pin "2") (pinfunction "2_2") (pintype "passive"))
      (node (ref "R118") (pin "2") (pinfunction "2_2") (pintype "passive"))
    )
    (net (code "157") (name "Net-(IC22--IN)") (class "Default")
      (node (ref "IC22") (pin "4") (pinfunction "-IN_4") (pintype "bidirectional"))
      (node (ref "R119") (pin "1") (pinfunction "1_1") (pintype "passive"))
      (node (ref "R120") (pin "1") (pinfunction "1_1") (pintype "passive"))
    )
    (net (code "158") (name "Net-(IC22-OUT)") (class "Default")
      (node (ref "IC22") (pin "1") (pinfunction "OUT_1") (pintype "bidirectional"))
      (node (ref "R120") (pin "2") (pinfunction "2_2") (pintype "passive"))
      (node (ref "R124") (pin "2") (pinfunction "2_2") (pintype "passive"))
    )
    (net (code "159") (name "Net-(IC23-+IN)") (class "Default")
      (node (ref "IC23") (pin "4") (pinfunction "+IN_4") (pintype "bidirectional"))
      (node (ref "R130") (pin "2") (pinfunction "2_2") (pintype "passive"))
    )
    (net (code "160") (name "Net-(IC23-+RG)") (class "Default")
      (node (ref "IC23") (pin "3") (pinfunction "+RG_3") (pintype "bidirectional"))
      (node (ref "IC24") (pin "12") (pinfunction "+IN4_12") (pintype "bidirectional"))
      (node (ref "R131") (pin "1") (pinfunction "1_1") (pintype "passive"))
    )
    (net (code "161") (name "Net-(IC23--IN)") (class "Default")
      (node (ref "IC23") (pin "1") (pinfunction "-IN_1") (pintype "bidirectional"))
      (node (ref "R129") (pin "2") (pinfunction "2_2") (pintype "passive"))
    )
    (net (code "162") (name "Net-(IC23--RG)") (class "Default")
      (node (ref "IC23") (pin "2") (pinfunction "-RG_2") (pintype "bidirectional"))
      (node (ref "IC24") (pin "10") (pinfunction "+IN3_10") (pintype "bidirectional"))
      (node (ref "R131") (pin "2") (pinfunction "2_2") (pintype "passive"))
    )
    (net (code "163") (name "Net-(IC23-OUT)") (class "Default")
      (node (ref "C110") (pin "1") (pinfunction "1_1") (pintype "passive"))
      (node (ref "IC23") (pin "7") (pinfunction "OUT_7") (pintype "bidirectional"))
    )
    (net (code "164") (name "Net-(IC24-+IN1)") (class "Default")
      (node (ref "C114") (pin "1") (pinfunction "1_1") (pintype "passive"))
      (node (ref "IC24") (pin "3") (pinfunction "+IN1_3") (pintype "bidirectional"))
      (node (ref "R141") (pin "1") (pinfunction "1_1") (pintype "passive"))
    )
    (net (code "165") (name "Net-(IC24-+IN2)") (class "Default")
      (node (ref "C111") (pin "2") (pinfunction "2_2") (pintype "passive"))
      (node (ref "IC24") (pin "5") (pinfunction "+IN2_5") (pintype "bidirectional"))
      (node (ref "R137") (pin "1") (pinfunction "1_1") (pintype "passive"))
    )
    (net (code "166") (name "Net-(IC24--IN1)") (class "Default")
      (node (ref "IC24") (pin "2") (pinfunction "-IN1_2") (pintype "bidirectional"))
      (node (ref "R142") (pin "1") (pinfunction "1_1") (pintype "passive"))
      (node (ref "R143") (pin "1") (pinfunction "1_1") (pintype "passive"))
    )
    (net (code "167") (name "Net-(IC24--IN2)") (class "Default")
      (node (ref "IC24") (pin "6") (pinfunction "-IN2_6") (pintype "bidirectional"))
      (node (ref "R134") (pin "2") (pinfunction "2_2") (pintype "passive"))
      (node (ref "R135") (pin "2") (pinfunction "2_2") (pintype "passive"))
    )
    (net (code "168") (name "Net-(IC24-OUT1)") (class "Default")
      (node (ref "C115") (pin "2") (pinfunction "2_2") (pintype "passive"))
      (node (ref "IC24") (pin "1") (pinfunction "OUT1_1") (pintype "bidirectional"))
      (node (ref "R139") (pin "2") (pinfunction "2_2") (pintype "passive"))
      (node (ref "R143") (pin "2") (pinfunction "2_2") (pintype "passive"))
    )
    (net (code "169") (name "Net-(IC24-OUT2)") (class "Default")
      (node (ref "IC24") (pin "7") (pinfunction "OUT2_7") (pintype "bidirectional"))
      (node (ref "R135") (pin "1") (pinfunction "1_1") (pintype "passive"))
      (node (ref "R136") (pin "2") (pinfunction "2_2") (pintype "passive"))
      (node (ref "R138") (pin "2") (pinfunction "2_2") (pintype "passive"))
    )
    (net (code "170") (name "Net-(IC25--IN)") (class "Default")
      (node (ref "IC25") (pin "4") (pinfunction "-IN_4") (pintype "bidirectional"))
      (node (ref "R139") (pin "1") (pinfunction "1_1") (pintype "passive"))
      (node (ref "R140") (pin "1") (pinfunction "1_1") (pintype "passive"))
    )
    (net (code "171") (name "Net-(IC25-OUT)") (class "Default")
      (node (ref "IC25") (pin "1") (pinfunction "OUT_1") (pintype "bidirectional"))
      (node (ref "R140") (pin "2") (pinfunction "2_2") (pintype "passive"))
      (node (ref "R144") (pin "2") (pinfunction "2_2") (pintype "passive"))
    )
    (net (code "172") (name "Net-(IC26-+IN)") (class "Default")
      (node (ref "IC26") (pin "4") (pinfunction "+IN_4") (pintype "bidirectional"))
      (node (ref "R150") (pin "2") (pinfunction "2_2") (pintype "passive"))
    )
    (net (code "173") (name "Net-(IC26-+RG)") (class "Default")
      (node (ref "IC26") (pin "3") (pinfunction "+RG_3") (pintype "bidirectional"))
      (node (ref "IC27") (pin "12") (pinfunction "+IN4_12") (pintype "bidirectional"))
      (node (ref "R151") (pin "1") (pinfunction "1_1") (pintype "passive"))
    )
    (net (code "174") (name "Net-(IC26--IN)") (class "Default")
      (node (ref "IC26") (pin "1") (pinfunction "-IN_1") (pintype "bidirectional"))
      (node (ref "R149") (pin "2") (pinfunction "2_2") (pintype "passive"))
    )
    (net (code "175") (name "Net-(IC26--RG)") (class "Default")
      (node (ref "IC26") (pin "2") (pinfunction "-RG_2") (pintype "bidirectional"))
      (node (ref "IC27") (pin "10") (pinfunction "+IN3_10") (pintype "bidirectional"))
      (node (ref "R151") (pin "2") (pinfunction "2_2") (pintype "passive"))
    )
    (net (code "176") (name "Net-(IC26-OUT)") (class "Default")
      (node (ref "C124") (pin "1") (pinfunction "1_1") (pintype "passive"))
      (node (ref "IC26") (pin "7") (pinfunction "OUT_7") (pintype "bidirectional"))
    )
    (net (code "177") (name "Net-(IC27-+IN1)") (class "Default")
      (node (ref "C128") (pin "1") (pinfunction "1_1") (pintype "passive"))
      (node (ref "IC27") (pin "3") (pinfunction "+IN1_3") (pintype "bidirectional"))
      (node (ref "R161") (pin "1") (pinfunction "1_1") (pintype "passive"))
    )
    (net (code "178") (name "Net-(IC27-+IN2)") (class "Default")
      (node (ref "C125") (pin "2") (pinfunction "2_2") (pintype "passive"))
      (node (ref "IC27") (pin "5") (pinfunction "+IN2_5") (pintype "bidirectional"))
      (node (ref "R157") (pin "1") (pinfunction "1_1") (pintype "passive"))
    )
    (net (code "179") (name "Net-(IC27--IN1)") (class "Default")
      (node (ref "IC27") (pin "2") (pinfunction "-IN1_2") (pintype "bidirectional"))
      (node (ref "R162") (pin "1") (pinfunction "1_1") (pintype "passive"))
      (node (ref "R163") (pin "1") (pinfunction "1_1") (pintype "passive"))
    )
    (net (code "180") (name "Net-(IC27--IN2)") (class "Default")
      (node (ref "IC27") (pin "6") (pinfunction "-IN2_6") (pintype "bidirectional"))
      (node (ref "R154") (pin "2") (pinfunction "2_2") (pintype "passive"))
      (node (ref "R155") (pin "2") (pinfunction "2_2") (pintype "passive"))
    )
    (net (code "181") (name "Net-(IC27-OUT1)") (class "Default")
      (node (ref "C129") (pin "2") (pinfunction "2_2") (pintype "passive"))
      (node (ref "IC27") (pin "1") (pinfunction "OUT1_1") (pintype "bidirectional"))
      (node (ref "R159") (pin "2") (pinfunction "2_2") (pintype "passive"))
      (node (ref "R163") (pin "2") (pinfunction "2_2") (pintype "passive"))
    )
    (net (code "182") (name "Net-(IC27-OUT2)") (class "Default")
      (node (ref "IC27") (pin "7") (pinfunction "OUT2_7") (pintype "bidirectional"))
      (node (ref "R155") (pin "1") (pinfunction "1_1") (pintype "passive"))
      (node (ref "R156") (pin "2") (pinfunction "2_2") (pintype "passive"))
      (node (ref "R158") (pin "2") (pinfunction "2_2") (pintype "passive"))
    )
    (net (code "183") (name "Net-(IC28--IN)") (class "Default")
      (node (ref "IC28") (pin "4") (pinfunction "-IN_4") (pintype "bidirectional"))
      (node (ref "R159") (pin "1") (pinfunction "1_1") (pintype "passive"))
      (node (ref "R160") (pin "1") (pinfunction "1_1") (pintype "passive"))
    )
    (net (code "184") (name "Net-(IC28-OUT)") (class "Default")
      (node (ref "IC28") (pin "1") (pinfunction "OUT_1") (pintype "bidirectional"))
      (node (ref "R160") (pin "2") (pinfunction "2_2") (pintype "passive"))
      (node (ref "R164") (pin "2") (pinfunction "2_2") (pintype "passive"))
    )
    (net (code "185") (name "Net-(IN1-Pad1)") (class "Default")
      (node (ref "IN1") (pin "1") (pinfunction "1_1") (pintype "passive"))
      (node (ref "R2") (pin "1") (pinfunction "1_1") (pintype "passive"))
    )
    (net (code "186") (name "Net-(IN1-Pad2)") (class "Default")
      (node (ref "IN1") (pin "2") (pinfunction "2_2") (pintype "passive"))
      (node (ref "R4") (pin "1") (pinfunction "1_1") (pintype "passive"))
    )
    (net (code "187") (name "Net-(IN1-Pad3)") (class "Default")
      (node (ref "IN1") (pin "3") (pinfunction "3_3") (pintype "passive"))
      (node (ref "R3") (pin "1") (pinfunction "1_1") (pintype "passive"))
    )
    (net (code "188") (name "Net-(IN1-Pad4)") (class "Default")
      (node (ref "IN1") (pin "4") (pinfunction "4_4") (pintype "passive"))
      (node (ref "R1") (pin "1") (pinfunction "1_1") (pintype "passive"))
    )
    (net (code "189") (name "Net-(IN2-Pad1)") (class "Default")
      (node (ref "IN2") (pin "1") (pinfunction "1_1") (pintype "passive"))
      (node (ref "R26") (pin "1") (pinfunction "1_1") (pintype "passive"))
    )
    (net (code "190") (name "Net-(IN2-Pad2)") (class "Default")
      (node (ref "IN2") (pin "2") (pinfunction "2_2") (pintype "passive"))
      (node (ref "R28") (pin "1") (pinfunction "1_1") (pintype "passive"))
    )
    (net (code "191") (name "Net-(IN2-Pad3)") (class "Default")
      (node (ref "IN2") (pin "3") (pinfunction "3_3") (pintype "passive"))
      (node (ref "R27") (pin "1") (pinfunction "1_1") (pintype "passive"))
    )
    (net (code "192") (name "Net-(IN2-Pad4)") (class "Default")
      (node (ref "IN2") (pin "4") (pinfunction "4_4") (pintype "passive"))
      (node (ref "R24") (pin "1") (pinfunction "1_1") (pintype "passive"))
    )
    (net (code "193") (name "Net-(IN3-Pad1)") (class "Default")
      (node (ref "IN3") (pin "1") (pinfunction "1_1") (pintype "passive"))
      (node (ref "R46") (pin "1") (pinfunction "1_1") (pintype "passive"))
    )
    (net (code "194") (name "Net-(IN3-Pad2)") (class "Default")
      (node (ref "IN3") (pin "2") (pinfunction "2_2") (pintype "passive"))
      (node (ref "R48") (pin "1") (pinfunction "1_1") (pintype "passive"))
    )
    (net (code "195") (name "Net-(IN3-Pad3)") (class "Default")
      (node (ref "IN3") (pin "3") (pinfunction "3_3") (pintype "passive"))
      (node (ref "R47") (pin "1") (pinfunction "1_1") (pintype "passive"))
    )
    (net (code "196") (name "Net-(IN3-Pad4)") (class "Default")
      (node (ref "IN3") (pin "4") (pinfunction "4_4") (pintype "passive"))
      (node (ref "R45") (pin "1") (pinfunction "1_1") (pintype "passive"))
    )
    (net (code "197") (name "Net-(IN4-Pad1)") (class "Default")
      (node (ref "IN4") (pin "1") (pinfunction "1_1") (pintype "passive"))
      (node (ref "R66") (pin "1") (pinfunction "1_1") (pintype "passive"))
    )
    (net (code "198") (name "Net-(IN4-Pad2)") (class "Default")
      (node (ref "IN4") (pin "2") (pinfunction "2_2") (pintype "passive"))
      (node (ref "R68") (pin "1") (pinfunction "1_1") (pintype "passive"))
    )
    (net (code "199") (name "Net-(IN4-Pad3)") (class "Default")
      (node (ref "IN4") (pin "3") (pinfunction "3_3") (pintype "passive"))
      (node (ref "R67") (pin "1") (pinfunction "1_1") (pintype "passive"))
    )
    (net (code "200") (name "Net-(IN4-Pad4)") (class "Default")
      (node (ref "IN4") (pin "4") (pinfunction "4_4") (pintype "passive"))
      (node (ref "R65") (pin "1") (pinfunction "1_1") (pintype "passive"))
    )
    (net (code "201") (name "Net-(IN5-Pad1)") (class "Default")
      (node (ref "IN5") (pin "1") (pinfunction "1_1") (pintype "passive"))
      (node (ref "R86") (pin "1") (pinfunction "1_1") (pintype "passive"))
    )
    (net (code "202") (name "Net-(IN5-Pad2)") (class "Default")
      (node (ref "IN5") (pin "2") (pinfunction "2_2") (pintype "passive"))
      (node (ref "R88") (pin "1") (pinfunction "1_1") (pintype "passive"))
    )
    (net (code "203") (name "Net-(IN5-Pad3)") (class "Default")
      (node (ref "IN5") (pin "3") (pinfunction "3_3") (pintype "passive"))
      (node (ref "R87") (pin "1") (pinfunction "1_1") (pintype "passive"))
    )
    (net (code "204") (name "Net-(IN5-Pad4)") (class "Default")
      (node (ref "IN5") (pin "4") (pinfunction "4_4") (pintype "passive"))
      (node (ref "R85") (pin "1") (pinfunction "1_1") (pintype "passive"))
    )
    (net (code "205") (name "Net-(IN6-Pad1)") (class "Default")
      (node (ref "IN6") (pin "1") (pinfunction "1_1") (pintype "passive"))
      (node (ref "R106") (pin "1") (pinfunction "1_1") (pintype "passive"))
    )
    (net (code "206") (name "Net-(IN6-Pad2)") (class "Default")
      (node (ref "IN6") (pin "2") (pinfunction "2_2") (pintype "passive"))
      (node (ref "R108") (pin "1") (pinfunction "1_1") (pintype "passive"))
    )
    (net (code "207") (name "Net-(IN6-Pad3)") (class "Default")
      (node (ref "IN6") (pin "3") (pinfunction "3_3") (pintype "passive"))
      (node (ref "R107") (pin "1") (pinfunction "1_1") (pintype "passive"))
    )
    (net (code "208") (name "Net-(IN6-Pad4)") (class "Default")
      (node (ref "IN6") (pin "4") (pinfunction "4_4") (pintype "passive"))
      (node (ref "R105") (pin "1") (pinfunction "1_1") (pintype "passive"))
    )
    (net (code "209") (name "Net-(IN7-Pad1)") (class "Default")
      (node (ref "IN7") (pin "1") (pinfunction "1_1") (pintype "passive"))
      (node (ref "R126") (pin "1") (pinfunction "1_1") (pintype "passive"))
    )
    (net (code "210") (name "Net-(IN7-Pad2)") (class "Default")
      (node (ref "IN7") (pin "2") (pinfunction "2_2") (pintype "passive"))
      (node (ref "R128") (pin "1") (pinfunction "1_1") (pintype "passive"))
    )
    (net (code "211") (name "Net-(IN7-Pad3)") (class "Default")
      (node (ref "IN7") (pin "3") (pinfunction "3_3") (pintype "passive"))
      (node (ref "R127") (pin "1") (pinfunction "1_1") (pintype "passive"))
    )
    (net (code "212") (name "Net-(IN7-Pad4)") (class "Default")
      (node (ref "IN7") (pin "4") (pinfunction "4_4") (pintype "passive"))
      (node (ref "R125") (pin "1") (pinfunction "1_1") (pintype "passive"))
    )
    (net (code "213") (name "Net-(IN8-Pad1)") (class "Default")
      (node (ref "IN8") (pin "1") (pinfunction "1_1") (pintype "passive"))
      (node (ref "R146") (pin "1") (pinfunction "1_1") (pintype "passive"))
    )
    (net (code "214") (name "Net-(IN8-Pad2)") (class "Default")
      (node (ref "IN8") (pin "2") (pinfunction "2_2") (pintype "passive"))
      (node (ref "R148") (pin "1") (pinfunction "1_1") (pintype "passive"))
    )
    (net (code "215") (name "Net-(IN8-Pad3)") (class "Default")
      (node (ref "IN8") (pin "3") (pinfunction "3_3") (pintype "passive"))
      (node (ref "R147") (pin "1") (pinfunction "1_1") (pintype "passive"))
    )
    (net (code "216") (name "Net-(IN8-Pad4)") (class "Default")
      (node (ref "IN8") (pin "4") (pinfunction "4_4") (pintype "passive"))
      (node (ref "R145") (pin "1") (pinfunction "1_1") (pintype "passive"))
    )
    (net (code "217") (name "VREF") (class "Default")
      (node (ref "C113") (pin "2") (pinfunction "2_2") (pintype "passive"))
      (node (ref "C127") (pin "2") (pinfunction "2_2") (pintype "passive"))
      (node (ref "C16") (pin "1") (pinfunction "1_1") (pintype "passive"))
      (node (ref "C20") (pin "+") (pinfunction "+_+") (pintype "passive"))
      (node (ref "C40") (pin "2") (pinfunction "2_2") (pintype "passive"))
      (node (ref "C52") (pin "2") (pinfunction "2_2") (pintype "passive"))
      (node (ref "C57") (pin "2") (pinfunction "2_2") (pintype "passive"))
      (node (ref "C71") (pin "2") (pinfunction "2_2") (pintype "passive"))
      (node (ref "C85") (pin "2") (pinfunction "2_2") (pintype "passive"))
      (node (ref "C99") (pin "2") (pinfunction "2_2") (pintype "passive"))
      (node (ref "IC10") (pin "3") (pinfunction "+IN_3") (pintype "bidirectional"))
      (node (ref "IC13") (pin "3") (pinfunction "+IN_3") (pintype "bidirectional"))
      (node (ref "IC16") (pin "3") (pinfunction "+IN_3") (pintype "bidirectional"))
      (node (ref "IC19") (pin "3") (pinfunction "+IN_3") (pintype "bidirectional"))
      (node (ref "IC22") (pin "3") (pinfunction "+IN_3") (pintype "bidirectional"))
      (node (ref "IC25") (pin "3") (pinfunction "+IN_3") (pintype "bidirectional"))
      (node (ref "IC28") (pin "3") (pinfunction "+IN_3") (pintype "bidirectional"))
      (node (ref "IC3") (pin "4") (pinfunction "VREFP_4") (pintype "bidirectional"))
      (node (ref "IC3") (pin "5") (pinfunction "AINCOM_5") (pintype "bidirectional"))
      (node (ref "IC4") (pin "3") (pinfunction "+IN_3") (pintype "bidirectional"))
      (node (ref "IC7") (pin "2") (pinfunction "VOUT_2") (pintype "bidirectional"))
    )
    (net (code "218") (name "unconnected-(IC3-D0{slash}CLKOUT-Pad25)") (class "Default")
      (node (ref "IC3") (pin "25") (pinfunction "D0/CLKOUT_25") (pintype "bidirectional"))
    )
    (net (code "219") (name "unconnected-(IC3-D1-Pad26)") (class "Default")
      (node (ref "IC3") (pin "26") (pinfunction "D1_26") (pintype "bidirectional"))
    )
    (net (code "220") (name "unconnected-(IC3-D2-Pad27)") (class "Default")
      (node (ref "IC3") (pin "27") (pinfunction "D2_27") (pintype "bidirectional"))
    )
    (net (code "221") (name "unconnected-(IC3-D3-Pad28)") (class "Default")
      (node (ref "IC3") (pin "28") (pinfunction "D3_28") (pintype "bidirectional"))
    )
    (net (code "222") (name "unconnected-(IC5-VI-Pad2)") (class "Default")
      (node (ref "IC5") (pin "2") (pinfunction "VI_2") (pintype "input"))
    )
  )
)
